# Sheet1.net
KiCad netlist of a schematic drawn in Altium Designer
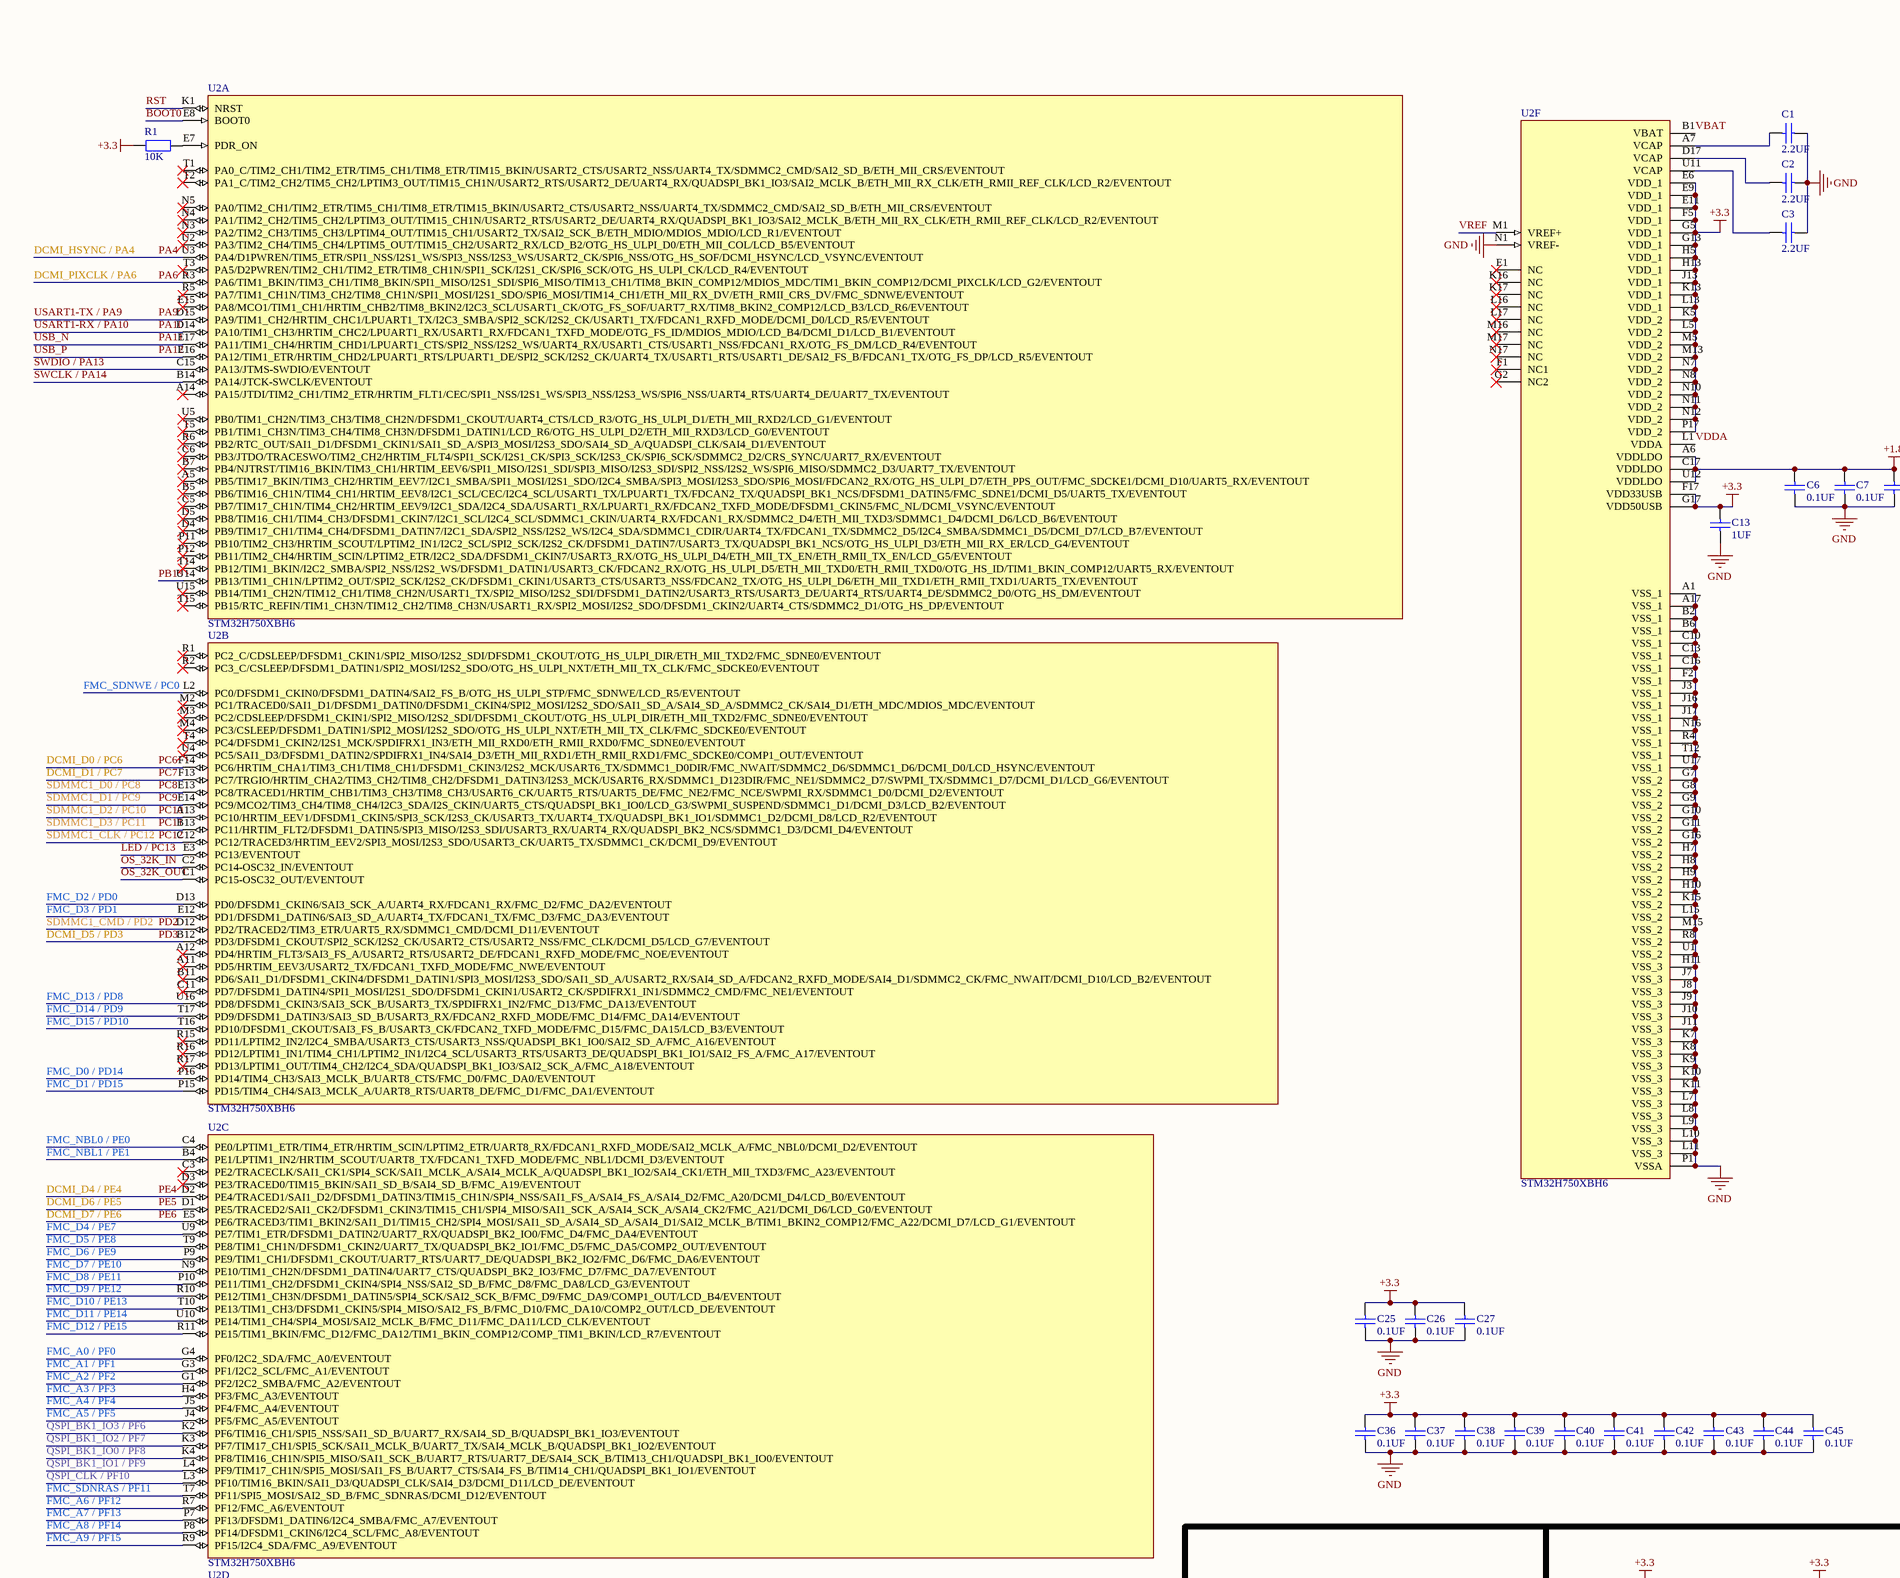
[diagram p0: Sheet1.SchDoc, top left]
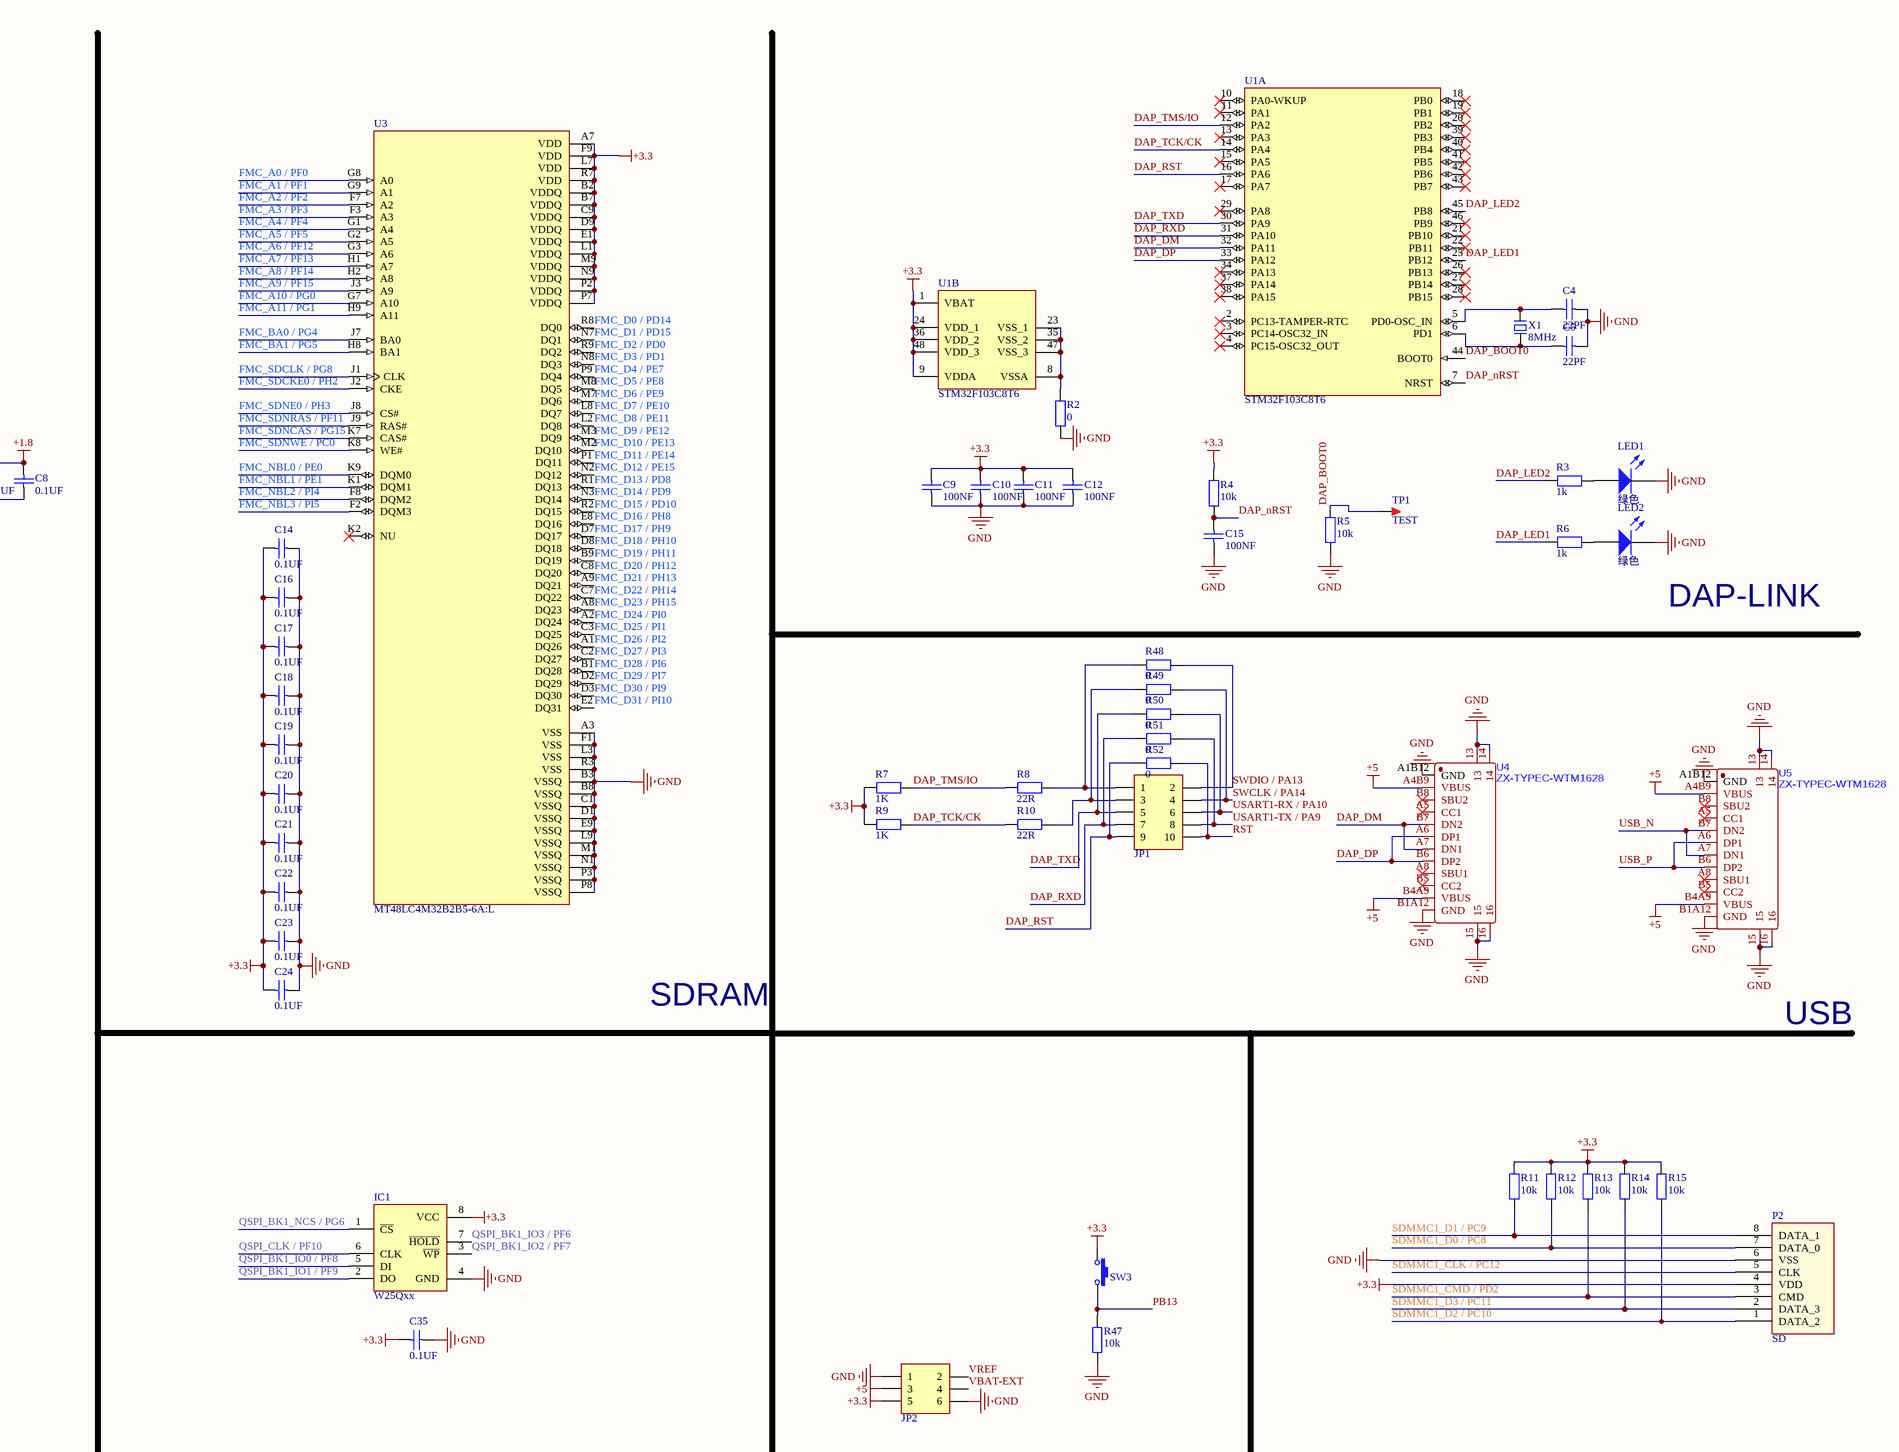
[diagram p1: Sheet1.SchDoc, top right]
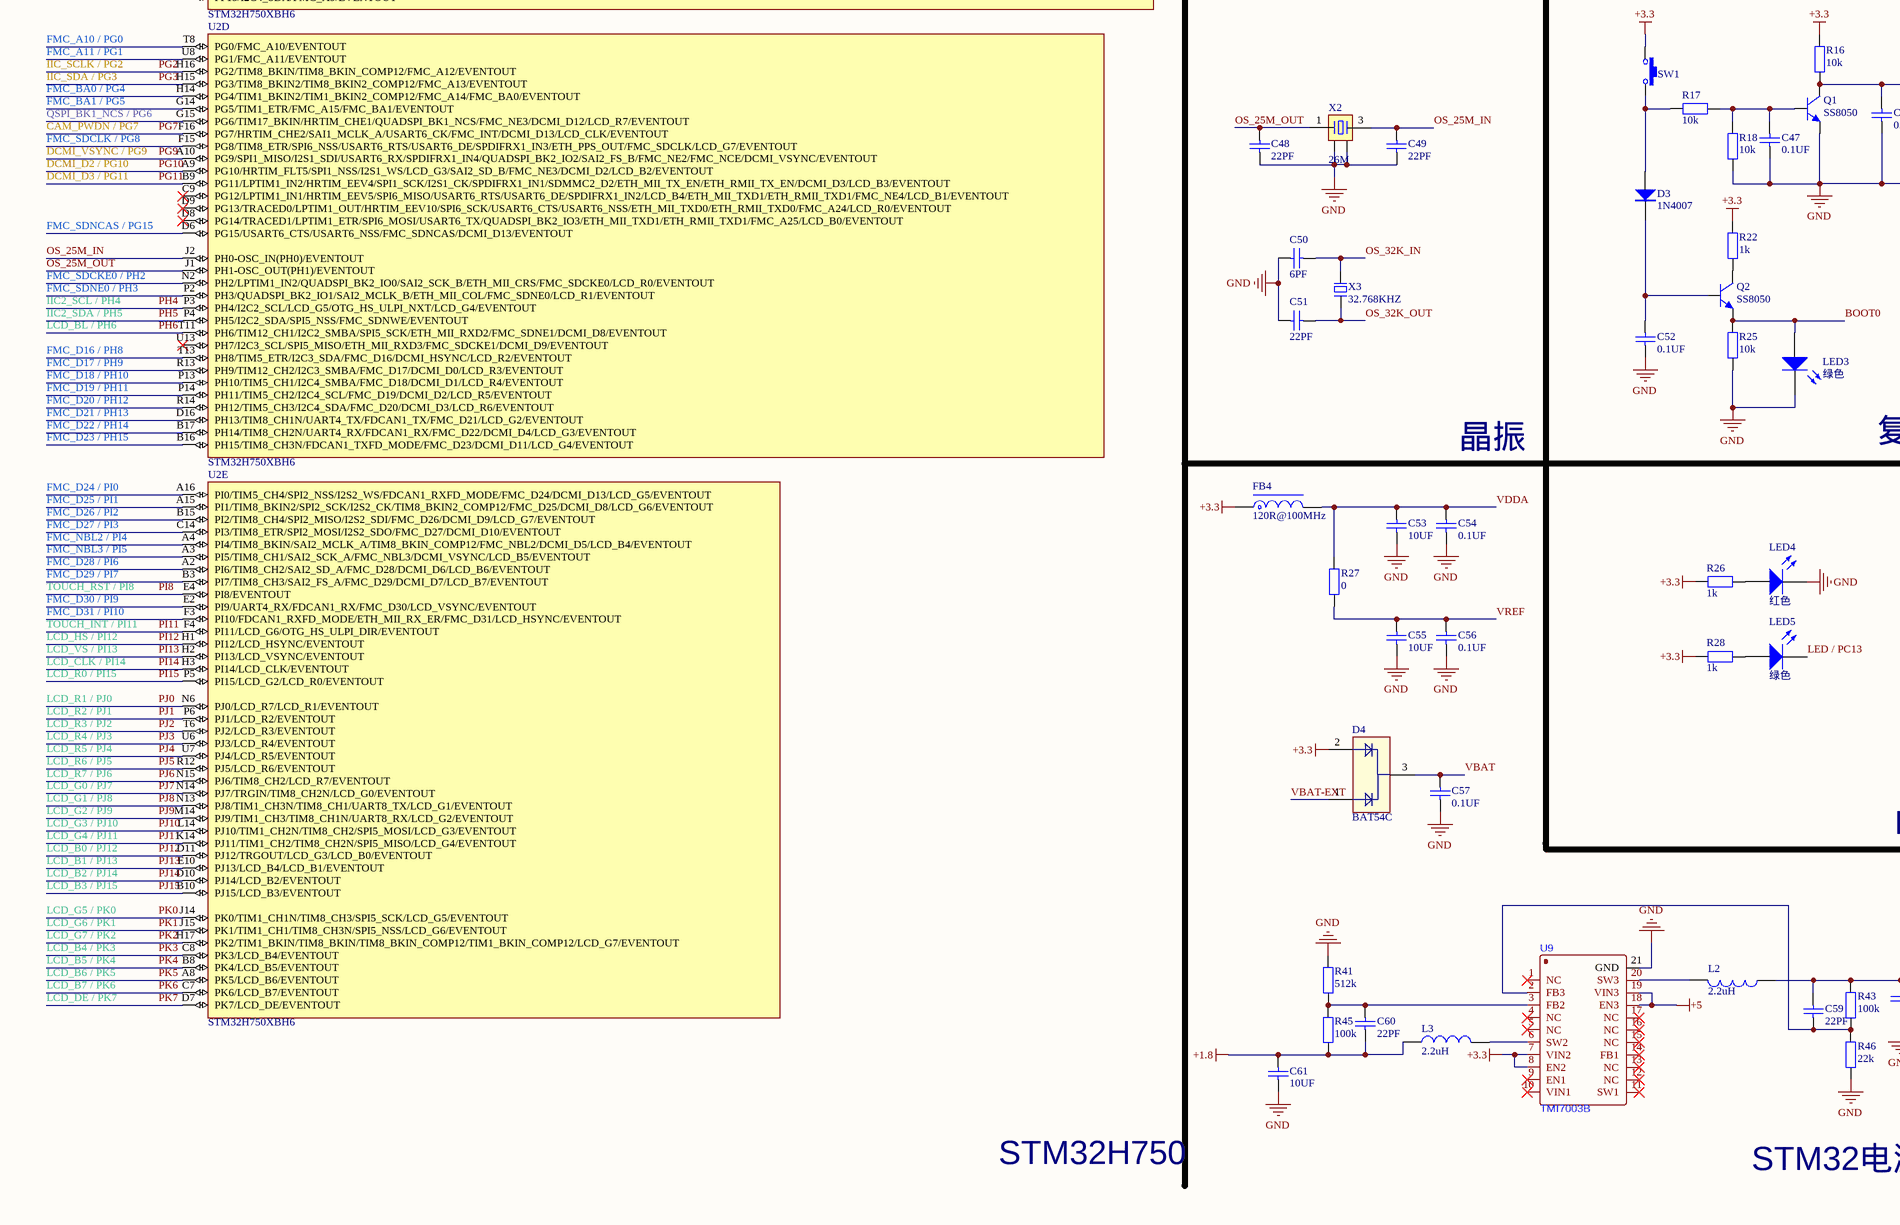
[diagram p2: Sheet1.SchDoc, bottom left]
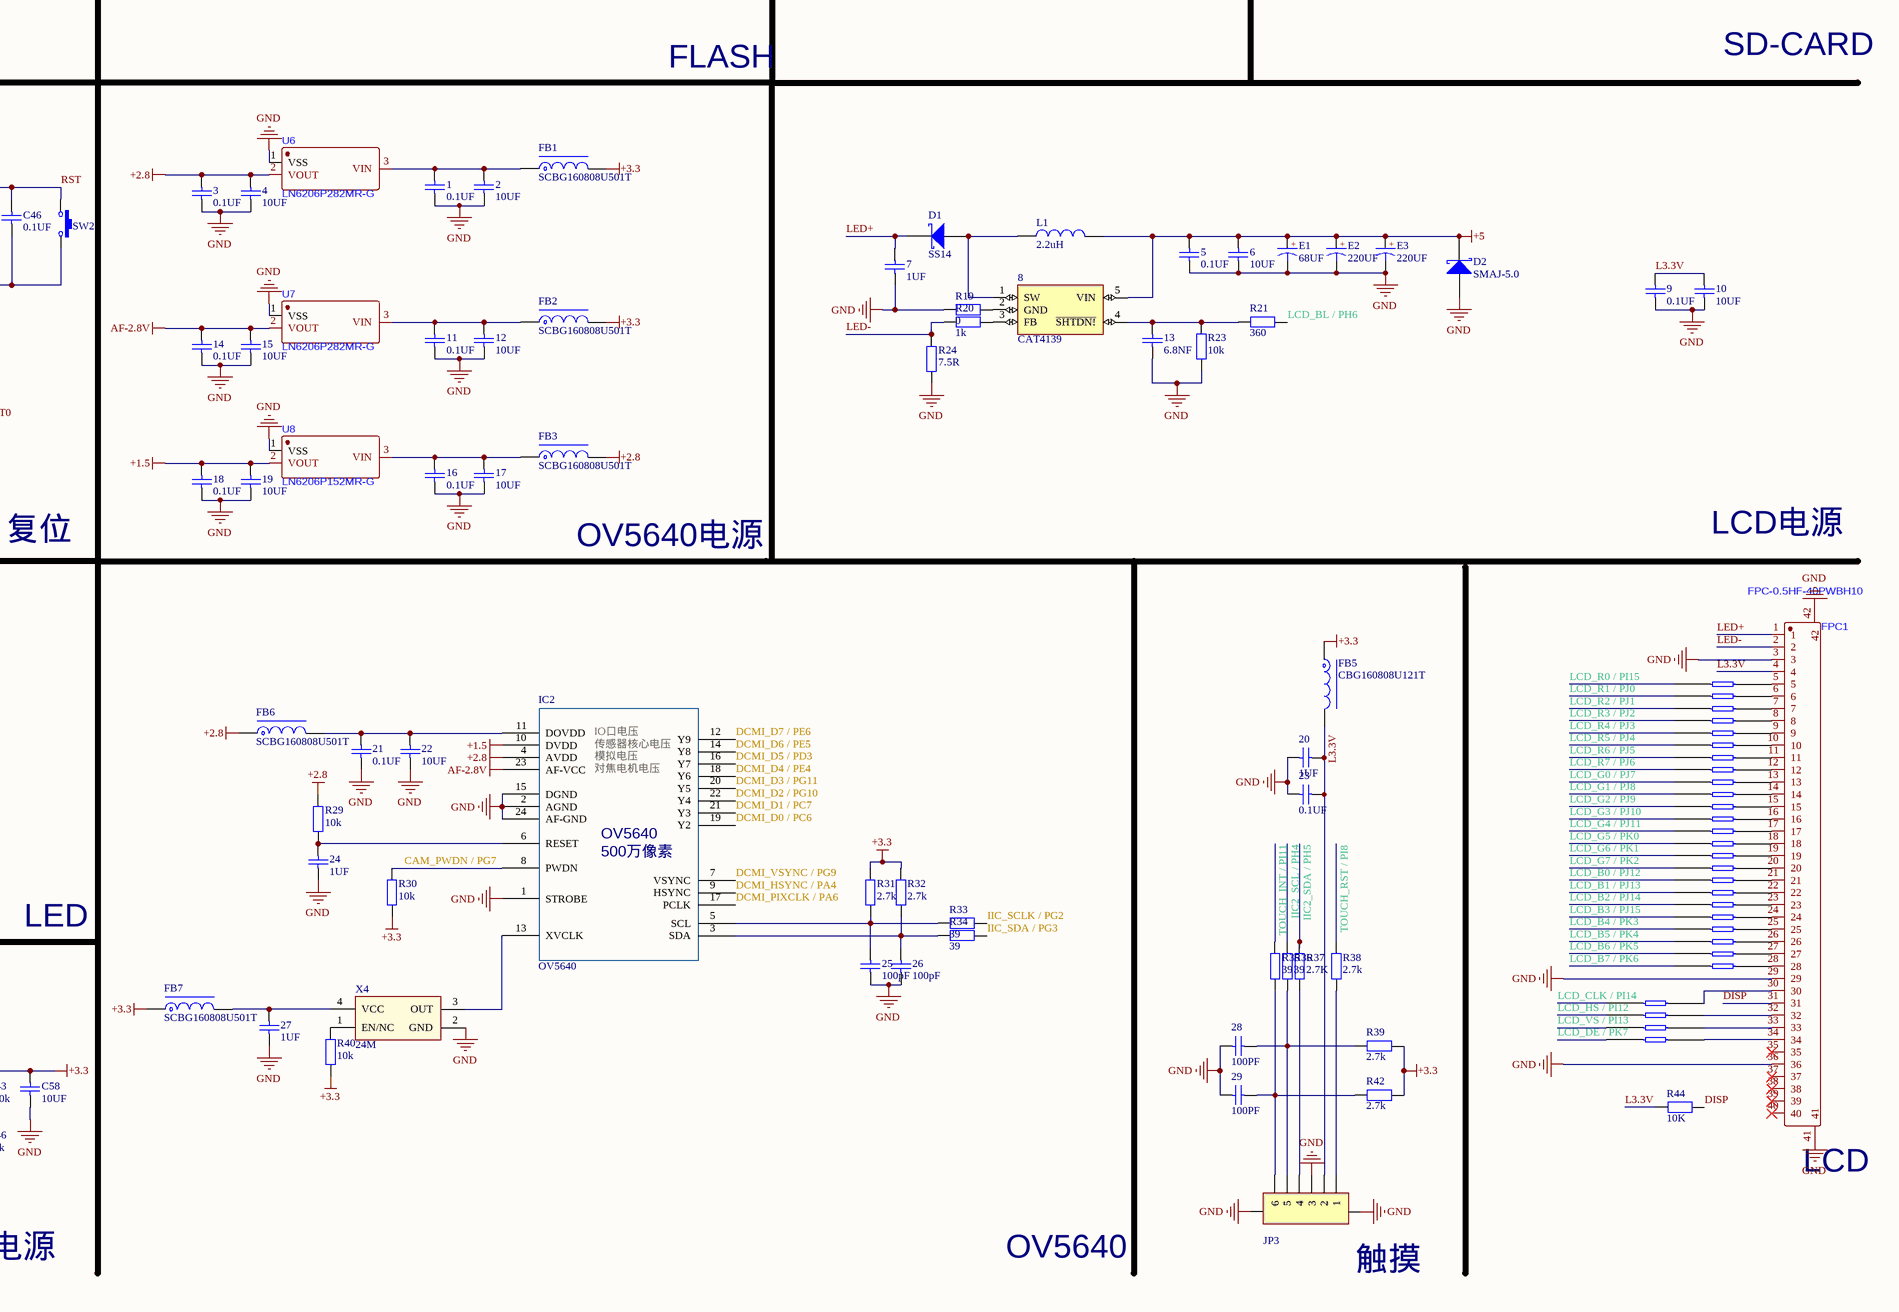
[diagram p3: Sheet1.SchDoc, bottom right]

(export (version "E")
  (design (tool "Eeschema 10.0.6"))
  (components
    (comp (ref "1")
      (value "0.1UF")
      (footprint "PCB1:C0603_L")
      (description "贴片电容/MLCC电容")
      (libsource (lib "屏幕一体板v1") (part "C"))
    )
    (comp (ref "2")
      (value "10UF")
      (footprint "PCB1:C0603_L")
      (description "贴片电容/MLCC电容")
      (libsource (lib "屏幕一体板v1") (part "C"))
    )
    (comp (ref "3")
      (value "0.1UF")
      (footprint "PCB1:C0603_L")
      (description "贴片电容/MLCC电容")
      (libsource (lib "屏幕一体板v1") (part "C"))
    )
    (comp (ref "4")
      (value "10UF")
      (footprint "PCB1:C0603_L")
      (description "贴片电容/MLCC电容")
      (libsource (lib "屏幕一体板v1") (part "C"))
    )
    (comp (ref "5")
      (value "0.1UF")
      (footprint "PCB1:C0603_L")
      (description "贴片电容/MLCC电容")
      (libsource (lib "屏幕一体板v1") (part "C"))
    )
    (comp (ref "6")
      (value "10UF")
      (footprint "PCB1:C0603_L")
      (description "贴片电容/MLCC电容")
      (libsource (lib "屏幕一体板v1") (part "C"))
    )
    (comp (ref "7")
      (value "1UF")
      (footprint "PCB1:C0603_L")
      (description "贴片电容/MLCC电容")
      (libsource (lib "屏幕一体板v1") (part "C"))
    )
    (comp (ref "8")
      (value "CAT4139")
      (footprint "PCB1:SOT-23(OT)5_LEAD")
      (libsource (lib "屏幕一体板v1") (part "CAT4139"))
    )
    (comp (ref "9")
      (value "0.1UF")
      (footprint "PCB1:C0603_L")
      (description "贴片电容/MLCC电容")
      (libsource (lib "屏幕一体板v1") (part "C"))
    )
    (comp (ref "10")
      (value "10UF")
      (footprint "PCB1:C0603_L")
      (description "贴片电容/MLCC电容")
      (libsource (lib "屏幕一体板v1") (part "C"))
    )
    (comp (ref "11")
      (value "0.1UF")
      (footprint "PCB1:C0603_L")
      (description "贴片电容/MLCC电容")
      (libsource (lib "屏幕一体板v1") (part "C"))
    )
    (comp (ref "12")
      (value "10UF")
      (footprint "PCB1:C0603_L")
      (description "贴片电容/MLCC电容")
      (libsource (lib "屏幕一体板v1") (part "C"))
    )
    (comp (ref "13")
      (value "6.8NF")
      (footprint "PCB1:C0603_L")
      (description "贴片电容/MLCC电容")
      (libsource (lib "屏幕一体板v1") (part "C"))
    )
    (comp (ref "14")
      (value "0.1UF")
      (footprint "PCB1:C0603_L")
      (description "贴片电容/MLCC电容")
      (libsource (lib "屏幕一体板v1") (part "C"))
    )
    (comp (ref "15")
      (value "10UF")
      (footprint "PCB1:C0603_L")
      (description "贴片电容/MLCC电容")
      (libsource (lib "屏幕一体板v1") (part "C"))
    )
    (comp (ref "16")
      (value "0.1UF")
      (footprint "PCB1:C0603_L")
      (description "贴片电容/MLCC电容")
      (libsource (lib "屏幕一体板v1") (part "C"))
    )
    (comp (ref "17")
      (value "10UF")
      (footprint "PCB1:C0603_L")
      (description "贴片电容/MLCC电容")
      (libsource (lib "屏幕一体板v1") (part "C"))
    )
    (comp (ref "18")
      (value "0.1UF")
      (footprint "PCB1:C0603_L")
      (description "贴片电容/MLCC电容")
      (libsource (lib "屏幕一体板v1") (part "C"))
    )
    (comp (ref "19")
      (value "10UF")
      (footprint "PCB1:C0603_L")
      (description "贴片电容/MLCC电容")
      (libsource (lib "屏幕一体板v1") (part "C"))
    )
    (comp (ref "20")
      (value "1UF")
      (footprint "PCB1:C0603_L")
      (description "贴片电容/MLCC电容")
      (libsource (lib "屏幕一体板v1") (part "C"))
    )
    (comp (ref "21")
      (value "0.1UF")
      (footprint "PCB1:C0603_L")
      (description "贴片电容/MLCC电容")
      (libsource (lib "屏幕一体板v1") (part "C"))
    )
    (comp (ref "22")
      (value "10UF")
      (footprint "PCB1:C0603_L")
      (description "贴片电容/MLCC电容")
      (libsource (lib "屏幕一体板v1") (part "C"))
    )
    (comp (ref "23")
      (value "0.1UF")
      (footprint "PCB1:C0603_L")
      (description "贴片电容/MLCC电容")
      (libsource (lib "屏幕一体板v1") (part "C"))
    )
    (comp (ref "24")
      (value "1UF")
      (footprint "PCB1:C0603_L")
      (description "贴片电容/MLCC电容")
      (libsource (lib "屏幕一体板v1") (part "C"))
    )
    (comp (ref "25")
      (value "100pF")
      (footprint "PCB1:C0603_L")
      (description "贴片电容/MLCC电容")
      (libsource (lib "屏幕一体板v1") (part "C"))
    )
    (comp (ref "26")
      (value "100pF")
      (footprint "PCB1:C0603_L")
      (description "贴片电容/MLCC电容")
      (libsource (lib "屏幕一体板v1") (part "C"))
    )
    (comp (ref "27")
      (value "1UF")
      (footprint "PCB1:C0603_L")
      (description "贴片电容/MLCC电容")
      (libsource (lib "屏幕一体板v1") (part "C"))
    )
    (comp (ref "28")
      (value "100PF")
      (footprint "PCB1:C0603_L")
      (description "贴片电容/MLCC电容")
      (libsource (lib "屏幕一体板v1") (part "C"))
    )
    (comp (ref "29")
      (value "100PF")
      (footprint "PCB1:C0603_L")
      (description "贴片电容/MLCC电容")
      (libsource (lib "屏幕一体板v1") (part "C"))
    )
    (comp (ref "C1")
      (value "2.2UF")
      (footprint "PCB1:C0603_L")
      (description "贴片电容/MLCC电容")
      (libsource (lib "屏幕一体板v1") (part "C"))
    )
    (comp (ref "C2")
      (value "2.2UF")
      (footprint "PCB1:C0603_L")
      (description "贴片电容/MLCC电容")
      (libsource (lib "屏幕一体板v1") (part "C"))
    )
    (comp (ref "C3")
      (value "2.2UF")
      (footprint "PCB1:C0603_L")
      (description "贴片电容/MLCC电容")
      (libsource (lib "屏幕一体板v1") (part "C"))
    )
    (comp (ref "C4")
      (value "22PF")
      (footprint "PCB1:C0603_L")
      (description "贴片电容/MLCC电容")
      (libsource (lib "屏幕一体板v1") (part "C"))
    )
    (comp (ref "C5")
      (value "22PF")
      (footprint "PCB1:C0603_L")
      (description "贴片电容/MLCC电容")
      (libsource (lib "屏幕一体板v1") (part "C"))
    )
    (comp (ref "C6")
      (value "0.1UF")
      (footprint "PCB1:C0603_L")
      (description "贴片电容/MLCC电容")
      (libsource (lib "屏幕一体板v1") (part "C"))
    )
    (comp (ref "C7")
      (value "0.1UF")
      (footprint "PCB1:C0603_L")
      (description "贴片电容/MLCC电容")
      (libsource (lib "屏幕一体板v1") (part "C"))
    )
    (comp (ref "C8")
      (value "0.1UF")
      (footprint "PCB1:C0603_L")
      (description "贴片电容/MLCC电容")
      (libsource (lib "屏幕一体板v1") (part "C"))
    )
    (comp (ref "C9")
      (value "100NF")
      (footprint "PCB1:C0603_L")
      (description "贴片电容/MLCC电容")
      (libsource (lib "屏幕一体板v1") (part "C"))
    )
    (comp (ref "C10")
      (value "100NF")
      (footprint "PCB1:C0603_L")
      (description "贴片电容/MLCC电容")
      (libsource (lib "屏幕一体板v1") (part "C"))
    )
    (comp (ref "C11")
      (value "100NF")
      (footprint "PCB1:C0603_L")
      (description "贴片电容/MLCC电容")
      (libsource (lib "屏幕一体板v1") (part "C"))
    )
    (comp (ref "C12")
      (value "100NF")
      (footprint "PCB1:C0603_L")
      (description "贴片电容/MLCC电容")
      (libsource (lib "屏幕一体板v1") (part "C"))
    )
    (comp (ref "C13")
      (value "1UF")
      (footprint "PCB1:C0603_L")
      (description "贴片电容/MLCC电容")
      (libsource (lib "屏幕一体板v1") (part "C"))
    )
    (comp (ref "C14")
      (value "0.1UF")
      (footprint "PCB1:C0201_M")
      (description "贴片电容/MLCC电容")
      (libsource (lib "屏幕一体板v1") (part "C"))
    )
    (comp (ref "C15")
      (value "100NF")
      (footprint "PCB1:C0603_L")
      (description "贴片电容/MLCC电容")
      (libsource (lib "屏幕一体板v1") (part "C"))
    )
    (comp (ref "C16")
      (value "0.1UF")
      (footprint "PCB1:C0201_M")
      (description "贴片电容/MLCC电容")
      (libsource (lib "屏幕一体板v1") (part "C"))
    )
    (comp (ref "C17")
      (value "0.1UF")
      (footprint "PCB1:C0201_M")
      (description "贴片电容/MLCC电容")
      (libsource (lib "屏幕一体板v1") (part "C"))
    )
    (comp (ref "C18")
      (value "0.1UF")
      (footprint "PCB1:C0201_M")
      (description "贴片电容/MLCC电容")
      (libsource (lib "屏幕一体板v1") (part "C"))
    )
    (comp (ref "C19")
      (value "0.1UF")
      (footprint "PCB1:C0201_M")
      (description "贴片电容/MLCC电容")
      (libsource (lib "屏幕一体板v1") (part "C"))
    )
    (comp (ref "C20")
      (value "0.1UF")
      (footprint "PCB1:C0201_M")
      (description "贴片电容/MLCC电容")
      (libsource (lib "屏幕一体板v1") (part "C"))
    )
    (comp (ref "C21")
      (value "0.1UF")
      (footprint "PCB1:C0201_M")
      (description "贴片电容/MLCC电容")
      (libsource (lib "屏幕一体板v1") (part "C"))
    )
    (comp (ref "C22")
      (value "0.1UF")
      (footprint "PCB1:C0201_M")
      (description "贴片电容/MLCC电容")
      (libsource (lib "屏幕一体板v1") (part "C"))
    )
    (comp (ref "C23")
      (value "0.1UF")
      (footprint "PCB1:C0201_M")
      (description "贴片电容/MLCC电容")
      (libsource (lib "屏幕一体板v1") (part "C"))
    )
    (comp (ref "C24")
      (value "0.1UF")
      (footprint "PCB1:C0201_M")
      (description "贴片电容/MLCC电容")
      (libsource (lib "屏幕一体板v1") (part "C"))
    )
    (comp (ref "C25")
      (value "0.1UF")
      (footprint "PCB1:C0201_M")
      (description "贴片电容/MLCC电容")
      (libsource (lib "屏幕一体板v1") (part "C"))
    )
    (comp (ref "C26")
      (value "0.1UF")
      (footprint "PCB1:C0201_M")
      (description "贴片电容/MLCC电容")
      (libsource (lib "屏幕一体板v1") (part "C"))
    )
    (comp (ref "C27")
      (value "0.1UF")
      (footprint "PCB1:C0201_M")
      (description "贴片电容/MLCC电容")
      (libsource (lib "屏幕一体板v1") (part "C"))
    )
    (comp (ref "C35")
      (value "0.1UF")
      (footprint "PCB1:C0603_L")
      (description "贴片电容/MLCC电容")
      (libsource (lib "屏幕一体板v1") (part "C"))
    )
    (comp (ref "C36")
      (value "0.1UF")
      (footprint "PCB1:C0201_M")
      (description "贴片电容/MLCC电容")
      (libsource (lib "屏幕一体板v1") (part "C"))
    )
    (comp (ref "C37")
      (value "0.1UF")
      (footprint "PCB1:C0201_M")
      (description "贴片电容/MLCC电容")
      (libsource (lib "屏幕一体板v1") (part "C"))
    )
    (comp (ref "C38")
      (value "0.1UF")
      (footprint "PCB1:C0201_M")
      (description "贴片电容/MLCC电容")
      (libsource (lib "屏幕一体板v1") (part "C"))
    )
    (comp (ref "C39")
      (value "0.1UF")
      (footprint "PCB1:C0201_M")
      (description "贴片电容/MLCC电容")
      (libsource (lib "屏幕一体板v1") (part "C"))
    )
    (comp (ref "C40")
      (value "0.1UF")
      (footprint "PCB1:C0201_M")
      (description "贴片电容/MLCC电容")
      (libsource (lib "屏幕一体板v1") (part "C"))
    )
    (comp (ref "C41")
      (value "0.1UF")
      (footprint "PCB1:C0201_M")
      (description "贴片电容/MLCC电容")
      (libsource (lib "屏幕一体板v1") (part "C"))
    )
    (comp (ref "C42")
      (value "0.1UF")
      (footprint "PCB1:C0201_M")
      (description "贴片电容/MLCC电容")
      (libsource (lib "屏幕一体板v1") (part "C"))
    )
    (comp (ref "C43")
      (value "0.1UF")
      (footprint "PCB1:C0201_M")
      (description "贴片电容/MLCC电容")
      (libsource (lib "屏幕一体板v1") (part "C"))
    )
    (comp (ref "C44")
      (value "0.1UF")
      (footprint "PCB1:C0201_M")
      (description "贴片电容/MLCC电容")
      (libsource (lib "屏幕一体板v1") (part "C"))
    )
    (comp (ref "C45")
      (value "0.1UF")
      (footprint "PCB1:C0201_M")
      (description "贴片电容/MLCC电容")
      (libsource (lib "屏幕一体板v1") (part "C"))
    )
    (comp (ref "C46")
      (value "0.1UF")
      (footprint "PCB1:C0603_L")
      (description "贴片电容/MLCC电容")
      (libsource (lib "屏幕一体板v1") (part "C"))
    )
    (comp (ref "C47")
      (value "0.1UF")
      (footprint "PCB1:C0603_L")
      (description "贴片电容/MLCC电容")
      (libsource (lib "屏幕一体板v1") (part "C"))
    )
    (comp (ref "C48")
      (value "22PF")
      (footprint "PCB1:C0603_L")
      (description "贴片电容/MLCC电容")
      (libsource (lib "屏幕一体板v1") (part "C"))
    )
    (comp (ref "C49")
      (value "22PF")
      (footprint "PCB1:C0603_L")
      (description "贴片电容/MLCC电容")
      (libsource (lib "屏幕一体板v1") (part "C"))
    )
    (comp (ref "C50")
      (value "6PF")
      (footprint "PCB1:C0603_L")
      (description "贴片电容/MLCC电容")
      (libsource (lib "屏幕一体板v1") (part "C"))
    )
    (comp (ref "C51")
      (value "22PF")
      (footprint "PCB1:C0603_L")
      (description "贴片电容/MLCC电容")
      (libsource (lib "屏幕一体板v1") (part "C"))
    )
    (comp (ref "C52")
      (value "0.1UF")
      (footprint "PCB1:C0603_L")
      (description "贴片电容/MLCC电容")
      (libsource (lib "屏幕一体板v1") (part "C"))
    )
    (comp (ref "C53")
      (value "10UF")
      (footprint "PCB1:C0603_L")
      (description "贴片电容/MLCC电容")
      (libsource (lib "屏幕一体板v1") (part "C"))
    )
    (comp (ref "C54")
      (value "0.1UF")
      (footprint "PCB1:C0603_L")
      (description "贴片电容/MLCC电容")
      (libsource (lib "屏幕一体板v1") (part "C"))
    )
    (comp (ref "C55")
      (value "10UF")
      (footprint "PCB1:C0603_L")
      (description "贴片电容/MLCC电容")
      (libsource (lib "屏幕一体板v1") (part "C"))
    )
    (comp (ref "C56")
      (value "0.1UF")
      (footprint "PCB1:C0603_L")
      (description "贴片电容/MLCC电容")
      (libsource (lib "屏幕一体板v1") (part "C"))
    )
    (comp (ref "C57")
      (value "0.1UF")
      (footprint "PCB1:C0603_L")
      (description "贴片电容/MLCC电容")
      (libsource (lib "屏幕一体板v1") (part "C"))
    )
    (comp (ref "C58")
      (value "10UF")
      (footprint "PCB1:C0603_L")
      (description "贴片电容/MLCC电容")
      (libsource (lib "屏幕一体板v1") (part "C"))
    )
    (comp (ref "C59")
      (value "22PF")
      (footprint "PCB1:C0603_L")
      (description "贴片电容/MLCC电容")
      (libsource (lib "屏幕一体板v1") (part "C"))
    )
    (comp (ref "C60")
      (value "22PF")
      (footprint "PCB1:C0603_L")
      (description "贴片电容/MLCC电容")
      (libsource (lib "屏幕一体板v1") (part "C"))
    )
    (comp (ref "C61")
      (value "10UF")
      (footprint "PCB1:C0603_L")
      (description "贴片电容/MLCC电容")
      (libsource (lib "屏幕一体板v1") (part "C"))
    )
    (comp (ref "D1")
      (value "SS14")
      (footprint "PCB1:SMA")
      (description "肖特基二极管")
      (libsource (lib "屏幕一体板v1") (part "SS14"))
    )
    (comp (ref "D2")
      (value "SMAJ-5.0")
      (footprint "PCB1:SMB")
      (description "肖特基二极管")
      (libsource (lib "屏幕一体板v1") (part "SS24"))
    )
    (comp (ref "D3")
      (value "1N4007")
      (footprint "PCB1:SMA")
      (description "整流二极管")
      (libsource (lib "屏幕一体板v1") (part "1N4007"))
    )
    (comp (ref "D4")
      (value "BAT54C")
      (footprint "PCB1:SOT23-3N")
      (description "两路肖特基二极管")
      (libsource (lib "屏幕一体板v1") (part "BAT54C"))
    )
    (comp (ref "E1")
      (value "68UF")
      (footprint "PCB1:CE A(3*5.4)")
      (description "贴片电解电容")
      (libsource (lib "屏幕一体板v1") (part "CE_SMD"))
    )
    (comp (ref "E2")
      (value "220UF")
      (footprint "PCB1:CE A(3*5.4)")
      (description "贴片电解电容")
      (libsource (lib "屏幕一体板v1") (part "CE_SMD"))
    )
    (comp (ref "E3")
      (value "220UF")
      (footprint "PCB1:CE A(3*5.4)")
      (description "贴片电解电容")
      (libsource (lib "屏幕一体板v1") (part "CE_SMD"))
    )
    (comp (ref "FB1")
      (value "SCBG160808U501T")
      (footprint "PCB1:FB0201")
      (description "贴片磁珠")
      (libsource (lib "屏幕一体板v1") (part "FB"))
    )
    (comp (ref "FB2")
      (value "SCBG160808U501T")
      (footprint "PCB1:FB0201")
      (description "贴片磁珠")
      (libsource (lib "屏幕一体板v1") (part "FB"))
    )
    (comp (ref "FB3")
      (value "SCBG160808U501T")
      (footprint "PCB1:FB0201")
      (description "贴片磁珠")
      (libsource (lib "屏幕一体板v1") (part "FB"))
    )
    (comp (ref "FB4")
      (value "120R@100MHz")
      (footprint "PCB1:FB0201")
      (description "贴片磁珠")
      (libsource (lib "屏幕一体板v1") (part "FB"))
    )
    (comp (ref "FB5")
      (value "CBG160808U121T")
      (footprint "PCB1:FB0805")
      (description "贴片磁珠")
      (libsource (lib "") (part "FB_1"))
    )
    (comp (ref "FB6")
      (value "SCBG160808U501T")
      (footprint "PCB1:FB0201")
      (description "贴片磁珠")
      (libsource (lib "屏幕一体板v1") (part "FB"))
    )
    (comp (ref "FB7")
      (value "SCBG160808U501T")
      (footprint "PCB1:FB0201")
      (description "贴片磁珠")
      (libsource (lib "屏幕一体板v1") (part "FB"))
    )
    (comp (ref "FPC1")
      (value "FPC-0.5HF-40PWBH10")
      (footprint "PCB1:FPC-SMD_40P-P0.50_FPC-0.5HF-40PWBH10")
      (libsource (lib "屏幕一体板v1") (part "FPC-0.5HF-40PWBH10"))
    )
    (comp (ref "IC1")
      (value "W25Qxx")
      (footprint "PCB1:SOP8W_N")
      (description "SPI Flash")
      (libsource (lib "屏幕一体板v1") (part "W25Q"))
    )
    (comp (ref "IC2") (value "OV5640") (footprint "PCB1:OV2640") (libsource (lib "屏幕一体板v1") (part "OV5640")))
    (comp (ref "JP1")
      (value "Header 5X2")
      (footprint "PCB1:HDR2.54-M-LS-2x5P")
      (description "5*2P接插件")
      (libsource (lib "屏幕一体板v1") (part "Header 5X2"))
    )
    (comp (ref "JP2")
      (value "Header3X2")
      (footprint "PCB1:HDR2.54-M-LS-2x3P")
      (description "3*2P接插件")
      (libsource (lib "屏幕一体板v1") (part "Header 3X2"))
    )
    (comp (ref "JP3")
      (value "CON-6P")
      (footprint "PCB1:FPC0.5-WT-6P")
      (description "6P连接器")
      (libsource (lib "屏幕一体板v1") (part "Header 6"))
    )
    (comp (ref "L1")
      (value "2.2uH")
      (footprint "PCB1:L0805")
      (description "贴片小功率电感")
      (libsource (lib "屏幕一体板v1") (part "L"))
    )
    (comp (ref "L2")
      (value "2.2uH")
      (footprint "PCB1:L0805")
      (description "贴片小功率电感")
      (libsource (lib "屏幕一体板v1") (part "L"))
    )
    (comp (ref "L3")
      (value "2.2uH")
      (footprint "PCB1:L0805")
      (description "贴片小功率电感")
      (libsource (lib "屏幕一体板v1") (part "L"))
    )
    (comp (ref "LED1")
      (value "绿色")
      (footprint "PCB1:LED0805_G")
      (description "贴片LED")
      (libsource (lib "屏幕一体板v1") (part "LED"))
    )
    (comp (ref "LED2")
      (value "绿色")
      (footprint "PCB1:LED0805_G")
      (description "贴片LED")
      (libsource (lib "屏幕一体板v1") (part "LED"))
    )
    (comp (ref "LED3")
      (value "绿色")
      (footprint "PCB1:LED0805_G")
      (description "贴片LED")
      (libsource (lib "屏幕一体板v1") (part "LED"))
    )
    (comp (ref "LED4")
      (value "红色")
      (footprint "PCB1:LED0603_R")
      (description "贴片LED")
      (libsource (lib "屏幕一体板v1") (part "LED"))
    )
    (comp (ref "LED5")
      (value "绿色")
      (footprint "PCB1:LED0805_G")
      (description "贴片LED")
      (libsource (lib "屏幕一体板v1") (part "LED"))
    )
    (comp (ref "P2")
      (value "SD")
      (footprint "PCB1:MICRO SD")
      (description "自弹式TF卡座")
      (libsource (lib "屏幕一体板v1") (part "Micro SD_SD"))
    )
    (comp (ref "Q1")
      (value "SS8050")
      (footprint "PCB1:SOT23-3N")
      (description "高频放大-NPN型")
      (libsource (lib "屏幕一体板v1") (part "8050-SMD"))
    )
    (comp (ref "Q2")
      (value "SS8050")
      (footprint "PCB1:SOT23-3N")
      (description "高频放大-NPN型")
      (libsource (lib "屏幕一体板v1") (part "8050-SMD"))
    )
    (comp (ref "R1")
      (value "10K")
      (footprint "PCB1:R0603_L")
      (description "贴片电阻")
      (libsource (lib "屏幕一体板v1") (part "R"))
    )
    (comp (ref "R2")
      (value "0")
      (footprint "PCB1:R0603_L")
      (description "贴片电阻")
      (libsource (lib "屏幕一体板v1") (part "R"))
    )
    (comp (ref "R3")
      (value "1k")
      (footprint "PCB1:R0603_L")
      (description "贴片电阻")
      (libsource (lib "屏幕一体板v1") (part "R"))
    )
    (comp (ref "R4")
      (value "10k")
      (footprint "PCB1:R0603_L")
      (description "贴片电阻")
      (libsource (lib "屏幕一体板v1") (part "R"))
    )
    (comp (ref "R5")
      (value "10k")
      (footprint "PCB1:R0603_L")
      (description "贴片电阻")
      (libsource (lib "屏幕一体板v1") (part "R"))
    )
    (comp (ref "R6")
      (value "1k")
      (footprint "PCB1:R0603_L")
      (description "贴片电阻")
      (libsource (lib "屏幕一体板v1") (part "R"))
    )
    (comp (ref "R7")
      (value "1K")
      (footprint "PCB1:R0805_L")
      (description "贴片电阻")
      (libsource (lib "屏幕一体板v1") (part "R"))
    )
    (comp (ref "R8")
      (value "22R")
      (footprint "PCB1:R0805_L")
      (description "贴片电阻")
      (libsource (lib "屏幕一体板v1") (part "R"))
    )
    (comp (ref "R9")
      (value "1K")
      (footprint "PCB1:R0805_L")
      (description "贴片电阻")
      (libsource (lib "屏幕一体板v1") (part "R"))
    )
    (comp (ref "R10")
      (value "22R")
      (footprint "PCB1:R0805_L")
      (description "贴片电阻")
      (libsource (lib "屏幕一体板v1") (part "R"))
    )
    (comp (ref "R11")
      (value "10k")
      (footprint "PCB1:R0603_L")
      (description "贴片电阻")
      (libsource (lib "屏幕一体板v1") (part "R"))
    )
    (comp (ref "R12")
      (value "10k")
      (footprint "PCB1:R0603_L")
      (description "贴片电阻")
      (libsource (lib "屏幕一体板v1") (part "R"))
    )
    (comp (ref "R13")
      (value "10k")
      (footprint "PCB1:R0603_L")
      (description "贴片电阻")
      (libsource (lib "屏幕一体板v1") (part "R"))
    )
    (comp (ref "R14")
      (value "10k")
      (footprint "PCB1:R0603_L")
      (description "贴片电阻")
      (libsource (lib "屏幕一体板v1") (part "R"))
    )
    (comp (ref "R15")
      (value "10k")
      (footprint "PCB1:R0603_L")
      (description "贴片电阻")
      (libsource (lib "屏幕一体板v1") (part "R"))
    )
    (comp (ref "R16")
      (value "10k")
      (footprint "PCB1:R0603_L")
      (description "贴片电阻")
      (libsource (lib "屏幕一体板v1") (part "R"))
    )
    (comp (ref "R17")
      (value "10k")
      (footprint "PCB1:R0603_L")
      (description "贴片电阻")
      (libsource (lib "屏幕一体板v1") (part "R"))
    )
    (comp (ref "R18")
      (value "10k")
      (footprint "PCB1:R0603_L")
      (description "贴片电阻")
      (libsource (lib "屏幕一体板v1") (part "R"))
    )
    (comp (ref "R19")
      (value "0")
      (footprint "PCB1:R0603_L")
      (description "贴片电阻")
      (libsource (lib "屏幕一体板v1") (part "R"))
    )
    (comp (ref "R20")
      (value "1k")
      (footprint "PCB1:R0603_L")
      (description "贴片电阻")
      (libsource (lib "屏幕一体板v1") (part "R"))
    )
    (comp (ref "R21")
      (value "360")
      (footprint "PCB1:R0603_L")
      (description "贴片电阻")
      (libsource (lib "屏幕一体板v1") (part "R"))
    )
    (comp (ref "R22")
      (value "1k")
      (footprint "PCB1:R0603_L")
      (description "贴片电阻")
      (libsource (lib "屏幕一体板v1") (part "R"))
    )
    (comp (ref "R23")
      (value "10k")
      (footprint "PCB1:R0603_L")
      (description "贴片电阻")
      (libsource (lib "屏幕一体板v1") (part "R"))
    )
    (comp (ref "R24")
      (value "7.5R")
      (footprint "PCB1:R0603_L")
      (description "贴片电阻")
      (libsource (lib "屏幕一体板v1") (part "R"))
    )
    (comp (ref "R25")
      (value "10k")
      (footprint "PCB1:R0603_L")
      (description "贴片电阻")
      (libsource (lib "屏幕一体板v1") (part "R"))
    )
    (comp (ref "R26")
      (value "1k")
      (footprint "PCB1:R0603_L")
      (description "贴片电阻")
      (libsource (lib "屏幕一体板v1") (part "R"))
    )
    (comp (ref "R27")
      (value "0")
      (footprint "PCB1:R0603_L")
      (description "贴片电阻")
      (libsource (lib "屏幕一体板v1") (part "R"))
    )
    (comp (ref "R28")
      (value "1k")
      (footprint "PCB1:R0603_L")
      (description "贴片电阻")
      (libsource (lib "屏幕一体板v1") (part "R"))
    )
    (comp (ref "R29")
      (value "10k")
      (footprint "PCB1:R0603_L")
      (description "贴片电阻")
      (libsource (lib "屏幕一体板v1") (part "R"))
    )
    (comp (ref "R30")
      (value "10k")
      (footprint "PCB1:R0603_L")
      (description "贴片电阻")
      (libsource (lib "屏幕一体板v1") (part "R"))
    )
    (comp (ref "R31")
      (value "2.7k")
      (footprint "PCB1:R0603_L")
      (description "贴片电阻")
      (libsource (lib "屏幕一体板v1") (part "R"))
    )
    (comp (ref "R32")
      (value "2.7k")
      (footprint "PCB1:R0603_L")
      (description "贴片电阻")
      (libsource (lib "屏幕一体板v1") (part "R"))
    )
    (comp (ref "R33")
      (value "39")
      (footprint "PCB1:R0603_L")
      (description "贴片电阻")
      (libsource (lib "屏幕一体板v1") (part "R"))
    )
    (comp (ref "R34")
      (value "39")
      (footprint "PCB1:R0603_L")
      (description "贴片电阻")
      (libsource (lib "屏幕一体板v1") (part "R"))
    )
    (comp (ref "R35")
      (value "39")
      (footprint "PCB1:R0603_L")
      (description "贴片电阻")
      (libsource (lib "屏幕一体板v1") (part "R"))
    )
    (comp (ref "R36")
      (value "39")
      (footprint "PCB1:R0603_L")
      (description "贴片电阻")
      (libsource (lib "屏幕一体板v1") (part "R"))
    )
    (comp (ref "R37")
      (value "2.7K")
      (footprint "PCB1:R0603_L")
      (description "贴片电阻")
      (libsource (lib "屏幕一体板v1") (part "R"))
    )
    (comp (ref "R38")
      (value "2.7k")
      (footprint "PCB1:R0603_L")
      (description "贴片电阻")
      (libsource (lib "屏幕一体板v1") (part "R"))
    )
    (comp (ref "R39")
      (value "2.7k")
      (footprint "PCB1:R0603_L")
      (description "贴片电阻")
      (libsource (lib "屏幕一体板v1") (part "R"))
    )
    (comp (ref "R40")
      (value "10k")
      (footprint "PCB1:R0603_L")
      (description "贴片电阻")
      (libsource (lib "屏幕一体板v1") (part "R"))
    )
    (comp (ref "R41")
      (value "512k")
      (footprint "PCB1:R0603_L")
      (description "贴片电阻")
      (libsource (lib "屏幕一体板v1") (part "R"))
    )
    (comp (ref "R42")
      (value "2.7k")
      (footprint "PCB1:R0603_L")
      (description "贴片电阻")
      (libsource (lib "屏幕一体板v1") (part "R"))
    )
    (comp (ref "R43")
      (value "100k")
      (footprint "PCB1:R0603_L")
      (description "贴片电阻")
      (libsource (lib "屏幕一体板v1") (part "R"))
    )
    (comp (ref "R44")
      (value "10K")
      (footprint "PCB1:R0603_L")
      (description "贴片电阻")
      (libsource (lib "屏幕一体板v1") (part "R"))
    )
    (comp (ref "R45")
      (value "100k")
      (footprint "PCB1:R0603_L")
      (description "贴片电阻")
      (libsource (lib "屏幕一体板v1") (part "R"))
    )
    (comp (ref "R46")
      (value "22k")
      (footprint "PCB1:R0603_L")
      (description "贴片电阻")
      (libsource (lib "屏幕一体板v1") (part "R"))
    )
    (comp (ref "R47")
      (value "10k")
      (footprint "PCB1:R0603_L")
      (description "贴片电阻")
      (libsource (lib "屏幕一体板v1") (part "R"))
    )
    (comp (ref "R48")
      (value "0")
      (footprint "PCB1:R0603_L")
      (description "贴片电阻")
      (libsource (lib "屏幕一体板v1") (part "R"))
    )
    (comp (ref "R49")
      (value "0")
      (footprint "PCB1:R0603_L")
      (description "贴片电阻")
      (libsource (lib "屏幕一体板v1") (part "R"))
    )
    (comp (ref "R50")
      (value "0")
      (footprint "PCB1:R0603_L")
      (description "贴片电阻")
      (libsource (lib "屏幕一体板v1") (part "R"))
    )
    (comp (ref "R51")
      (value "0")
      (footprint "PCB1:R0603_L")
      (description "贴片电阻")
      (libsource (lib "屏幕一体板v1") (part "R"))
    )
    (comp (ref "R52")
      (value "0")
      (footprint "PCB1:R0603_L")
      (description "贴片电阻")
      (libsource (lib "屏幕一体板v1") (part "R"))
    )
    (comp (ref "RP1") (value "120R排阻") (footprint "PCB1:0603_4P") (libsource (lib "屏幕一体板v1") (part "RES_4P")))
    (comp (ref "RP2") (value "120R排阻") (footprint "PCB1:0603_4P") (libsource (lib "屏幕一体板v1") (part "RES_4P")))
    (comp (ref "RP3") (value "120R排阻") (footprint "PCB1:0603_4P") (libsource (lib "屏幕一体板v1") (part "RES_4P")))
    (comp (ref "RP4") (value "120R排阻") (footprint "PCB1:0603_4P") (libsource (lib "屏幕一体板v1") (part "RES_4P")))
    (comp (ref "RP5") (value "120R排阻") (footprint "PCB1:0603_4P") (libsource (lib "屏幕一体板v1") (part "RES_4P")))
    (comp (ref "RP6") (value "120R排阻") (footprint "PCB1:0603_4P") (libsource (lib "屏幕一体板v1") (part "RES_4P")))
    (comp (ref "RP7") (value "120R排阻") (footprint "PCB1:0603_4P") (libsource (lib "屏幕一体板v1") (part "RES_4P")))
    (comp (ref "SW1")
      (value "3x6x5")
      (footprint "PCB1:SW SMD-3*6*2.5")
      (description "3x6轻触开关")
      (libsource (lib "屏幕一体板v1") (part "SW 3x6"))
    )
    (comp (ref "SW2")
      (value "3x6x5")
      (footprint "PCB1:SW SMD-3*6*2.5")
      (description "3x6轻触开关")
      (libsource (lib "屏幕一体板v1") (part "SW 3x6"))
    )
    (comp (ref "SW3")
      (value "3x6x5")
      (footprint "PCB1:SW SMD-3*6*2.5")
      (description "3x6轻触开关")
      (libsource (lib "屏幕一体板v1") (part "SW 3x6"))
    )
    (comp (ref "TP1")
      (value "TEST")
      (footprint "PCB1:TEST 1.6")
      (description "测试点")
      (libsource (lib "屏幕一体板v1") (part "TEST"))
    )
    (comp (ref "U1")
      (value "STM32F103C8T6")
      (footprint "PCB1:LQFP48_N")
      (libsource (lib "屏幕一体板v1") (part "STM32F103C8T6"))
    )
    (comp (ref "U2")
      (value "STM32H750XBH6")
      (footprint "PCB1:IC_STM32H750XBH6")
      (libsource (lib "屏幕一体板v1") (part "STM32H750XBH6"))
    )
    (comp (ref "U3")
      (value "MT48LC4M32B2B5-6A:L")
      (footprint "PCB1:BGA90C80P9X15_800X1300X100N")
      (description "SDRAM Memory IC 128Mb _4M x 32_ Parallel 167MHz 5.4ns 90-VFBGA _8x13_")
      (libsource (lib "屏幕一体板v1") (part "MT48LC4M32B2B5-6A{colon}L"))
    )
    (comp (ref "U4")
      (value "ZX-TYPEC-WTM1628")
      (footprint "PCB1:USB-C-SMD_ZX-TYPEC-WTM1628")
      (libsource (lib "屏幕一体板v1") (part "ZX-TYPEC-WTM1628"))
    )
    (comp (ref "U5")
      (value "ZX-TYPEC-WTM1628")
      (footprint "PCB1:USB-C-SMD_ZX-TYPEC-WTM1628")
      (libsource (lib "屏幕一体板v1") (part "ZX-TYPEC-WTM1628"))
    )
    (comp (ref "U6")
      (value "LN6206P282MR-G")
      (footprint "PCB1:SOT-23-3_L2.9-W1.3-P1.90-LS2.4-BR")
      (libsource (lib "屏幕一体板v1") (part "LN6206P282MR-G"))
    )
    (comp (ref "U7")
      (value "LN6206P282MR-G")
      (footprint "PCB1:SOT-23-3_L2.9-W1.3-P1.90-LS2.4-BR")
      (libsource (lib "屏幕一体板v1") (part "LN6206P282MR-G"))
    )
    (comp (ref "U8")
      (value "LN6206P152MR-G")
      (footprint "PCB1:SOT-23-3_L2.9-W1.3-P1.90-LS2.4-BR")
      (libsource (lib "屏幕一体板v1") (part "LN6206P282MR-G"))
    )
    (comp (ref "U9")
      (value "TMI7003B")
      (footprint "PCB1:QFN-20_L3.0-W3.0-P0.40-BL-EP1.7")
      (libsource (lib "屏幕一体板v1") (part "TMI7003B"))
    )
    (comp (ref "X1")
      (value "8MHz")
      (footprint "PCB1:XTAL-3215-2P")
      (description "2脚无源晶振(谐振器）")
      (libsource (lib "屏幕一体板v1") (part "XTAL-2P"))
    )
    (comp (ref "X2")
      (value "26M")
      (footprint "PCB1:XTAL-3225-4P")
      (description "4脚无源晶振(谐振器）")
      (libsource (lib "屏幕一体板v1") (part "XTAL-4P"))
    )
    (comp (ref "X3")
      (value "32.768KHZ")
      (footprint "PCB1:XTAL-3215-2P")
      (description "2脚无源晶振(谐振器）")
      (libsource (lib "屏幕一体板v1") (part "XTAL-2P"))
    )
    (comp (ref "X4")
      (value "24M")
      (footprint "PCB1:OSC-3225-4P")
      (description "4脚有源晶振(振荡器)")
      (libsource (lib "屏幕一体板v1") (part "XTAL-ACT-4P"))
    )
  )
  (nets
    (net (code "1") (name "+1.5") (class "Default")
      (node (ref "18") (pin "2") (pinfunction "2_2") (pintype "passive"))
      (node (ref "19") (pin "2") (pinfunction "2_2") (pintype "passive"))
      (node (ref "IC2") (pin "10") (pinfunction "DVDD_10") (pintype "passive"))
      (node (ref "U8") (pin "2") (pinfunction "VOUT_2") (pintype "passive"))
    )
    (net (code "2") (name "+1.8") (class "Default")
      (node (ref "C6") (pin "1") (pinfunction "1_1") (pintype "passive"))
      (node (ref "C60") (pin "2") (pinfunction "2_2") (pintype "passive"))
      (node (ref "C61") (pin "1") (pinfunction "1_1") (pintype "passive"))
      (node (ref "C7") (pin "1") (pinfunction "1_1") (pintype "passive"))
      (node (ref "C8") (pin "1") (pinfunction "1_1") (pintype "passive"))
      (node (ref "L3") (pin "1") (pinfunction "1_1") (pintype "passive"))
      (node (ref "R45") (pin "1") (pinfunction "1_1") (pintype "passive"))
      (node (ref "U2") (pin "A6") (pinfunction "VDDLDO_A6") (pintype "power_in"))
      (node (ref "U2") (pin "C17") (pinfunction "VDDLDO_C17") (pintype "power_in"))
      (node (ref "U2") (pin "U12") (pinfunction "VDDLDO_U12") (pintype "power_in"))
    )
    (net (code "3") (name "+2.8") (class "Default")
      (node (ref "3") (pin "2") (pinfunction "2_2") (pintype "passive"))
      (node (ref "4") (pin "2") (pinfunction "2_2") (pintype "passive"))
      (node (ref "FB3") (pin "2") (pinfunction "2_2") (pintype "passive"))
      (node (ref "FB6") (pin "1") (pinfunction "1_1") (pintype "passive"))
      (node (ref "IC2") (pin "4") (pinfunction "AVDD_4") (pintype "passive"))
      (node (ref "R29") (pin "1") (pinfunction "1_1") (pintype "passive"))
      (node (ref "U6") (pin "2") (pinfunction "VOUT_2") (pintype "passive"))
    )
    (net (code "4") (name "+3.3") (class "Default")
      (node (ref "C10") (pin "2") (pinfunction "2_2") (pintype "passive"))
      (node (ref "C11") (pin "2") (pinfunction "2_2") (pintype "passive"))
      (node (ref "C12") (pin "2") (pinfunction "2_2") (pintype "passive"))
      (node (ref "C13") (pin "2") (pinfunction "2_2") (pintype "passive"))
      (node (ref "C14") (pin "2") (pinfunction "2_2") (pintype "passive"))
      (node (ref "C16") (pin "2") (pinfunction "2_2") (pintype "passive"))
      (node (ref "C17") (pin "2") (pinfunction "2_2") (pintype "passive"))
      (node (ref "C18") (pin "2") (pinfunction "2_2") (pintype "passive"))
      (node (ref "C19") (pin "2") (pinfunction "2_2") (pintype "passive"))
      (node (ref "C20") (pin "2") (pinfunction "2_2") (pintype "passive"))
      (node (ref "C21") (pin "2") (pinfunction "2_2") (pintype "passive"))
      (node (ref "C22") (pin "2") (pinfunction "2_2") (pintype "passive"))
      (node (ref "C23") (pin "2") (pinfunction "2_2") (pintype "passive"))
      (node (ref "C24") (pin "2") (pinfunction "2_2") (pintype "passive"))
      (node (ref "C25") (pin "2") (pinfunction "2_2") (pintype "passive"))
      (node (ref "C26") (pin "2") (pinfunction "2_2") (pintype "passive"))
      (node (ref "C27") (pin "2") (pinfunction "2_2") (pintype "passive"))
      (node (ref "C35") (pin "2") (pinfunction "2_2") (pintype "passive"))
      (node (ref "C36") (pin "2") (pinfunction "2_2") (pintype "passive"))
      (node (ref "C37") (pin "2") (pinfunction "2_2") (pintype "passive"))
      (node (ref "C38") (pin "2") (pinfunction "2_2") (pintype "passive"))
      (node (ref "C39") (pin "2") (pinfunction "2_2") (pintype "passive"))
      (node (ref "C40") (pin "2") (pinfunction "2_2") (pintype "passive"))
      (node (ref "C41") (pin "2") (pinfunction "2_2") (pintype "passive"))
      (node (ref "C42") (pin "2") (pinfunction "2_2") (pintype "passive"))
      (node (ref "C43") (pin "2") (pinfunction "2_2") (pintype "passive"))
      (node (ref "C44") (pin "2") (pinfunction "2_2") (pintype "passive"))
      (node (ref "C45") (pin "2") (pinfunction "2_2") (pintype "passive"))
      (node (ref "C58") (pin "2") (pinfunction "2_2") (pintype "passive"))
      (node (ref "C59") (pin "2") (pinfunction "2_2") (pintype "passive"))
      (node (ref "C9") (pin "2") (pinfunction "2_2") (pintype "passive"))
      (node (ref "D4") (pin "2") (pinfunction "2_2") (pintype "passive"))
      (node (ref "FB1") (pin "2") (pinfunction "2_2") (pintype "passive"))
      (node (ref "FB2") (pin "2") (pinfunction "2_2") (pintype "passive"))
      (node (ref "FB4") (pin "1") (pinfunction "1_1") (pintype "passive"))
      (node (ref "FB5") (pin "1") (pinfunction "1_1") (pintype "passive"))
      (node (ref "FB7") (pin "1") (pinfunction "1_1") (pintype "passive"))
      (node (ref "IC1") (pin "8") (pinfunction "VCC_8") (pintype "passive"))
      (node (ref "JP2") (pin "5") (pinfunction "5_5") (pintype "passive"))
      (node (ref "L2") (pin "1") (pinfunction "1_1") (pintype "passive"))
      (node (ref "P2") (pin "4") (pinfunction "VDD_4") (pintype "passive"))
      (node (ref "R1") (pin "1") (pinfunction "1_1") (pintype "passive"))
      (node (ref "R11") (pin "1") (pinfunction "1_1") (pintype "passive"))
      (node (ref "R12") (pin "1") (pinfunction "1_1") (pintype "passive"))
      (node (ref "R13") (pin "1") (pinfunction "1_1") (pintype "passive"))
      (node (ref "R14") (pin "1") (pinfunction "1_1") (pintype "passive"))
      (node (ref "R15") (pin "1") (pinfunction "1_1") (pintype "passive"))
      (node (ref "R16") (pin "2") (pinfunction "2_2") (pintype "passive"))
      (node (ref "R22") (pin "2") (pinfunction "2_2") (pintype "passive"))
      (node (ref "R26") (pin "1") (pinfunction "1_1") (pintype "passive"))
      (node (ref "R28") (pin "1") (pinfunction "1_1") (pintype "passive"))
      (node (ref "R30") (pin "2") (pinfunction "2_2") (pintype "passive"))
      (node (ref "R31") (pin "2") (pinfunction "2_2") (pintype "passive"))
      (node (ref "R32") (pin "2") (pinfunction "2_2") (pintype "passive"))
      (node (ref "R39") (pin "2") (pinfunction "2_2") (pintype "passive"))
      (node (ref "R4") (pin "2") (pinfunction "2_2") (pintype "passive"))
      (node (ref "R40") (pin "2") (pinfunction "2_2") (pintype "passive"))
      (node (ref "R42") (pin "2") (pinfunction "2_2") (pintype "passive"))
      (node (ref "R43") (pin "1") (pinfunction "1_1") (pintype "passive"))
      (node (ref "R7") (pin "1") (pinfunction "1_1") (pintype "passive"))
      (node (ref "R9") (pin "1") (pinfunction "1_1") (pintype "passive"))
      (node (ref "SW1") (pin "1") (pinfunction "1_1") (pintype "passive"))
      (node (ref "SW3") (pin "1") (pinfunction "1_1") (pintype "passive"))
      (node (ref "U1") (pin "1") (pinfunction "VBAT_1") (pintype "power_in"))
      (node (ref "U1") (pin "24") (pinfunction "VDD_1_24") (pintype "power_in"))
      (node (ref "U1") (pin "36") (pinfunction "VDD_2_36") (pintype "power_in"))
      (node (ref "U1") (pin "48") (pinfunction "VDD_3_48") (pintype "power_in"))
      (node (ref "U1") (pin "9") (pinfunction "VDDA_9") (pintype "power_in"))
      (node (ref "U2") (pin "E11") (pinfunction "VDD_1_E11") (pintype "power_in"))
      (node (ref "U2") (pin "E6") (pinfunction "VDD_1_E6") (pintype "power_in"))
      (node (ref "U2") (pin "E9") (pinfunction "VDD_1_E9") (pintype "power_in"))
      (node (ref "U2") (pin "F17") (pinfunction "VDD33USB_F17") (pintype "power_in"))
      (node (ref "U2") (pin "F5") (pinfunction "VDD_1_F5") (pintype "power_in"))
      (node (ref "U2") (pin "G13") (pinfunction "VDD_1_G13") (pintype "power_in"))
      (node (ref "U2") (pin "G17") (pinfunction "VDD50USB_G17") (pintype "power_in"))
      (node (ref "U2") (pin "G5") (pinfunction "VDD_1_G5") (pintype "power_in"))
      (node (ref "U2") (pin "H13") (pinfunction "VDD_1_H13") (pintype "power_in"))
      (node (ref "U2") (pin "H5") (pinfunction "VDD_1_H5") (pintype "power_in"))
      (node (ref "U2") (pin "J13") (pinfunction "VDD_1_J13") (pintype "power_in"))
      (node (ref "U2") (pin "K13") (pinfunction "VDD_1_K13") (pintype "power_in"))
      (node (ref "U2") (pin "K5") (pinfunction "VDD_2_K5") (pintype "power_in"))
      (node (ref "U2") (pin "L13") (pinfunction "VDD_1_L13") (pintype "power_in"))
      (node (ref "U2") (pin "L5") (pinfunction "VDD_2_L5") (pintype "power_in"))
      (node (ref "U2") (pin "M13") (pinfunction "VDD_2_M13") (pintype "power_in"))
      (node (ref "U2") (pin "M5") (pinfunction "VDD_2_M5") (pintype "power_in"))
      (node (ref "U2") (pin "N10") (pinfunction "VDD_2_N10") (pintype "power_in"))
      (node (ref "U2") (pin "N11") (pinfunction "VDD_2_N11") (pintype "power_in"))
      (node (ref "U2") (pin "N12") (pinfunction "VDD_2_N12") (pintype "power_in"))
      (node (ref "U2") (pin "N7") (pinfunction "VDD_2_N7") (pintype "power_in"))
      (node (ref "U2") (pin "N8") (pinfunction "VDD_2_N8") (pintype "power_in"))
      (node (ref "U2") (pin "P17") (pinfunction "VDD_2_P17") (pintype "power_in"))
      (node (ref "U3") (pin "A7") (pinfunction "VDD_A7") (pintype "power_in"))
      (node (ref "U3") (pin "B2") (pinfunction "VDDQ_B2") (pintype "power_in"))
      (node (ref "U3") (pin "B7") (pinfunction "VDDQ_B7") (pintype "power_in"))
      (node (ref "U3") (pin "C9") (pinfunction "VDDQ_C9") (pintype "power_in"))
      (node (ref "U3") (pin "D9") (pinfunction "VDDQ_D9") (pintype "power_in"))
      (node (ref "U3") (pin "E1") (pinfunction "VDDQ_E1") (pintype "power_in"))
      (node (ref "U3") (pin "F9") (pinfunction "VDD_F9") (pintype "power_in"))
      (node (ref "U3") (pin "L1") (pinfunction "VDDQ_L1") (pintype "power_in"))
      (node (ref "U3") (pin "L7") (pinfunction "VDD_L7") (pintype "power_in"))
      (node (ref "U3") (pin "M9") (pinfunction "VDDQ_M9") (pintype "power_in"))
      (node (ref "U3") (pin "N9") (pinfunction "VDDQ_N9") (pintype "power_in"))
      (node (ref "U3") (pin "P2") (pinfunction "VDDQ_P2") (pintype "power_in"))
      (node (ref "U3") (pin "P7") (pinfunction "VDDQ_P7") (pintype "power_in"))
      (node (ref "U3") (pin "R7") (pinfunction "VDD_R7") (pintype "power_in"))
      (node (ref "U9") (pin "7") (pinfunction "VIN2_7") (pintype "passive"))
      (node (ref "U9") (pin "8") (pinfunction "EN2_8") (pintype "passive"))
    )
    (net (code "5") (name "+5") (class "Default")
      (node (ref "5") (pin "2") (pinfunction "2_2") (pintype "passive"))
      (node (ref "6") (pin "2") (pinfunction "2_2") (pintype "passive"))
      (node (ref "8") (pin "5") (pinfunction "VIN_5") (pintype "bidirectional"))
      (node (ref "D2") (pin "2") (pinfunction "K_2") (pintype "passive"))
      (node (ref "E1") (pin "1") (pinfunction "1_1") (pintype "passive"))
      (node (ref "E2") (pin "1") (pinfunction "1_1") (pintype "passive"))
      (node (ref "E3") (pin "1") (pinfunction "1_1") (pintype "passive"))
      (node (ref "JP2") (pin "3") (pinfunction "3_3") (pintype "passive"))
      (node (ref "L1") (pin "2") (pinfunction "2_2") (pintype "passive"))
      (node (ref "U4") (pin "A4B9") (pinfunction "VBUS_A4B9") (pintype "passive"))
      (node (ref "U4") (pin "B4A9") (pinfunction "VBUS_B4A9") (pintype "passive"))
      (node (ref "U5") (pin "A4B9") (pinfunction "VBUS_A4B9") (pintype "passive"))
      (node (ref "U5") (pin "B4A9") (pinfunction "VBUS_B4A9") (pintype "passive"))
      (node (ref "U9") (pin "18") (pinfunction "EN3_18") (pintype "passive"))
      (node (ref "U9") (pin "19") (pinfunction "VIN3_19") (pintype "passive"))
    )
    (net (code "6") (name "/BOOT0") (class "Default")
      (node (ref "LED3") (pin "1") (pinfunction "A_1") (pintype "passive"))
      (node (ref "Q2") (pin "2") (pinfunction "E_2") (pintype "passive"))
      (node (ref "R25") (pin "2") (pinfunction "2_2") (pintype "passive"))
      (node (ref "U2") (pin "E8") (pinfunction "BOOT0_E8") (pintype "input"))
    )
    (net (code "7") (name "/CAM_PWDN {slash} PG7") (class "Default")
      (node (ref "IC2") (pin "8") (pinfunction "PWDN_8") (pintype "passive"))
      (node (ref "R30") (pin "1") (pinfunction "1_1") (pintype "passive"))
      (node (ref "U2") (pin "F16") (pinfunction "PG7/HRTIM_CHE2/SAI1_MCLK_A/USART6_CK/FMC_INT/DCMI_D13/LCD_CLK/EVENTOUT_F16") (pintype "bidirectional"))
    )
    (net (code "8") (name "/DAP_BOOT0") (class "Default")
      (node (ref "R5") (pin "2") (pinfunction "2_2") (pintype "passive"))
      (node (ref "TP1") (pin "1") (pinfunction "1_1") (pintype "passive"))
      (node (ref "U1") (pin "44") (pinfunction "BOOT0_44") (pintype "input"))
    )
    (net (code "9") (name "/DAP_DM") (class "Default")
      (node (ref "U1") (pin "32") (pinfunction "PA11_32") (pintype "bidirectional"))
      (node (ref "U4") (pin "A7") (pinfunction "DN1_A7") (pintype "passive"))
      (node (ref "U4") (pin "B7") (pinfunction "DN2_B7") (pintype "passive"))
    )
    (net (code "10") (name "/DAP_DP") (class "Default")
      (node (ref "U1") (pin "33") (pinfunction "PA12_33") (pintype "bidirectional"))
      (node (ref "U4") (pin "A6") (pinfunction "DP1_A6") (pintype "passive"))
      (node (ref "U4") (pin "B6") (pinfunction "DP2_B6") (pintype "passive"))
    )
    (net (code "11") (name "/DAP_LED1") (class "Default")
      (node (ref "R6") (pin "1") (pinfunction "1_1") (pintype "passive"))
      (node (ref "U1") (pin "25") (pinfunction "PB12_25") (pintype "bidirectional"))
    )
    (net (code "12") (name "/DAP_LED2") (class "Default")
      (node (ref "R3") (pin "1") (pinfunction "1_1") (pintype "passive"))
      (node (ref "U1") (pin "45") (pinfunction "PB8_45") (pintype "bidirectional"))
    )
    (net (code "13") (name "/DAP_RST") (class "Default")
      (node (ref "JP1") (pin "9") (pinfunction "9_9") (pintype "passive"))
      (node (ref "R52") (pin "1") (pinfunction "1_1") (pintype "passive"))
      (node (ref "U1") (pin "16") (pinfunction "PA6_16") (pintype "bidirectional"))
    )
    (net (code "14") (name "/DAP_RXD") (class "Default")
      (node (ref "JP1") (pin "7") (pinfunction "7_7") (pintype "passive"))
      (node (ref "R51") (pin "1") (pinfunction "1_1") (pintype "passive"))
      (node (ref "U1") (pin "31") (pinfunction "PA10_31") (pintype "bidirectional"))
    )
    (net (code "15") (name "/DAP_TCK{slash}CK") (class "Default")
      (node (ref "R10") (pin "1") (pinfunction "1_1") (pintype "passive"))
      (node (ref "R9") (pin "2") (pinfunction "2_2") (pintype "passive"))
      (node (ref "U1") (pin "14") (pinfunction "PA4_14") (pintype "bidirectional"))
    )
    (net (code "16") (name "/DAP_TMS{slash}IO") (class "Default")
      (node (ref "R7") (pin "2") (pinfunction "2_2") (pintype "passive"))
      (node (ref "R8") (pin "1") (pinfunction "1_1") (pintype "passive"))
      (node (ref "U1") (pin "12") (pinfunction "PA2_12") (pintype "bidirectional"))
    )
    (net (code "17") (name "/DAP_TXD") (class "Default")
      (node (ref "JP1") (pin "5") (pinfunction "5_5") (pintype "passive"))
      (node (ref "R50") (pin "1") (pinfunction "1_1") (pintype "passive"))
      (node (ref "U1") (pin "30") (pinfunction "PA9_30") (pintype "bidirectional"))
    )
    (net (code "18") (name "/DAP_nRST") (class "Default")
      (node (ref "C15") (pin "2") (pinfunction "2_2") (pintype "passive"))
      (node (ref "R4") (pin "1") (pinfunction "1_1") (pintype "passive"))
      (node (ref "U1") (pin "7") (pinfunction "NRST_7") (pintype "bidirectional"))
    )
    (net (code "19") (name "/DCMI_D0 {slash} PC6") (class "Default")
      (node (ref "IC2") (pin "19") (pinfunction "Y2_19") (pintype "passive"))
      (node (ref "U2") (pin "F14") (pinfunction "PC6/HRTIM_CHA1/TIM3_CH1/TIM8_CH1/DFSDM1_CKIN3/I2S2_MCK/USART6_TX/SDMMC1_D0DIR/FMC_NWAIT/SDMMC2_D6/SDMMC1_D6/DCMI_D0/LCD_HSYNC/EVENTOUT_F14") (pintype "bidirectional"))
    )
    (net (code "20") (name "/DCMI_D1 {slash} PC7") (class "Default")
      (node (ref "IC2") (pin "21") (pinfunction "Y3_21") (pintype "passive"))
      (node (ref "U2") (pin "F13") (pinfunction "PC7/TRGIO/HRTIM_CHA2/TIM3_CH2/TIM8_CH2/DFSDM1_DATIN3/I2S3_MCK/USART6_RX/SDMMC1_D123DIR/FMC_NE1/SDMMC2_D7/SWPMI_TX/SDMMC1_D7/DCMI_D1/LCD_G6/EVENTOUT_F13") (pintype "bidirectional"))
    )
    (net (code "21") (name "/DCMI_D2 {slash} PG10") (class "Default")
      (node (ref "IC2") (pin "22") (pinfunction "Y4_22") (pintype "passive"))
      (node (ref "U2") (pin "A9") (pinfunction "PG10/HRTIM_FLT5/SPI1_NSS/I2S1_WS/LCD_G3/SAI2_SD_B/FMC_NE3/DCMI_D2/LCD_B2/EVENTOUT_A9") (pintype "bidirectional"))
    )
    (net (code "22") (name "/DCMI_D3 {slash} PG11") (class "Default")
      (node (ref "IC2") (pin "20") (pinfunction "Y5_20") (pintype "passive"))
      (node (ref "U2") (pin "B9") (pinfunction "PG11/LPTIM1_IN2/HRTIM_EEV4/SPI1_SCK/I2S1_CK/SPDIFRX1_IN1/SDMMC2_D2/ETH_MII_TX_EN/ETH_RMII_TX_EN/DCMI_D3/LCD_B3/EVENTOUT_B9") (pintype "bidirectional"))
    )
    (net (code "23") (name "/DCMI_D4 {slash} PE4") (class "Default")
      (node (ref "IC2") (pin "18") (pinfunction "Y6_18") (pintype "passive"))
      (node (ref "U2") (pin "D2") (pinfunction "PE4/TRACED1/SAI1_D2/DFSDM1_DATIN3/TIM15_CH1N/SPI4_NSS/SAI1_FS_A/SAI4_FS_A/SAI4_D2/FMC_A20/DCMI_D4/LCD_B0/EVENTOUT_D2") (pintype "bidirectional"))
    )
    (net (code "24") (name "/DCMI_D5 {slash} PD3") (class "Default")
      (node (ref "IC2") (pin "16") (pinfunction "Y7_16") (pintype "passive"))
      (node (ref "U2") (pin "B12") (pinfunction "PD3/DFSDM1_CKOUT/SPI2_SCK/I2S2_CK/USART2_CTS/USART2_NSS/FMC_CLK/DCMI_D5/LCD_G7/EVENTOUT_B12") (pintype "bidirectional"))
    )
    (net (code "25") (name "/DCMI_D6 {slash} PE5") (class "Default")
      (node (ref "IC2") (pin "14") (pinfunction "Y8_14") (pintype "passive"))
      (node (ref "U2") (pin "D1") (pinfunction "PE5/TRACED2/SAI1_CK2/DFSDM1_CKIN3/TIM15_CH1/SPI4_MISO/SAI1_SCK_A/SAI4_SCK_A/SAI4_CK2/FMC_A21/DCMI_D6/LCD_G0/EVENTOUT_D1") (pintype "bidirectional"))
    )
    (net (code "26") (name "/DCMI_D7 {slash} PE6") (class "Default")
      (node (ref "IC2") (pin "12") (pinfunction "Y9_12") (pintype "passive"))
      (node (ref "U2") (pin "E5") (pinfunction "PE6/TRACED3/TIM1_BKIN2/SAI1_D1/TIM15_CH2/SPI4_MOSI/SAI1_SD_A/SAI4_SD_A/SAI4_D1/SAI2_MCLK_B/TIM1_BKIN2_COMP12/FMC_A22/DCMI_D7/LCD_G1/EVENTOUT_E5") (pintype "bidirectional"))
    )
    (net (code "27") (name "/DCMI_HSYNC {slash} PA4") (class "Default")
      (node (ref "IC2") (pin "9") (pinfunction "HSYNC_9") (pintype "passive"))
      (node (ref "U2") (pin "U3") (pinfunction "PA4/D1PWREN/TIM5_ETR/SPI1_NSS/I2S1_WS/SPI3_NSS/I2S3_WS/USART2_CK/SPI6_NSS/OTG_HS_SOF/DCMI_HSYNC/LCD_VSYNC/EVENTOUT_U3") (pintype "bidirectional"))
    )
    (net (code "28") (name "/DCMI_PIXCLK {slash} PA6") (class "Default")
      (node (ref "IC2") (pin "17") (pinfunction "PCLK_17") (pintype "passive"))
      (node (ref "U2") (pin "R3") (pinfunction "PA6/TIM1_BKIN/TIM3_CH1/TIM8_BKIN/SPI1_MISO/I2S1_SDI/SPI6_MISO/TIM13_CH1/TIM8_BKIN_COMP12/MDIOS_MDC/TIM1_BKIN_COMP12/DCMI_PIXCLK/LCD_G2/EVENTOUT_R3") (pintype "bidirectional"))
    )
    (net (code "29") (name "/DCMI_VSYNC {slash} PG9") (class "Default")
      (node (ref "IC2") (pin "7") (pinfunction "VSYNC_7") (pintype "passive"))
      (node (ref "U2") (pin "A10") (pinfunction "PG9/SPI1_MISO/I2S1_SDI/USART6_RX/SPDIFRX1_IN4/QUADSPI_BK2_IO2/SAI2_FS_B/FMC_NE2/FMC_NCE/DCMI_VSYNC/EVENTOUT_A10") (pintype "bidirectional"))
    )
    (net (code "30") (name "/DISP") (class "Default")
      (node (ref "FPC1") (pin "31") (pinfunction "31_31") (pintype "passive"))
      (node (ref "R44") (pin "2") (pinfunction "2_2") (pintype "passive"))
    )
    (net (code "31") (name "/FMC_A0 {slash} PF0") (class "Default")
      (node (ref "U2") (pin "G4") (pinfunction "PF0/I2C2_SDA/FMC_A0/EVENTOUT_G4") (pintype "bidirectional"))
      (node (ref "U3") (pin "G8") (pinfunction "A0_G8") (pintype "input"))
    )
    (net (code "32") (name "/FMC_A1 {slash} PF1") (class "Default")
      (node (ref "U2") (pin "G3") (pinfunction "PF1/I2C2_SCL/FMC_A1/EVENTOUT_G3") (pintype "bidirectional"))
      (node (ref "U3") (pin "G9") (pinfunction "A1_G9") (pintype "input"))
    )
    (net (code "33") (name "/FMC_A2 {slash} PF2") (class "Default")
      (node (ref "U2") (pin "G1") (pinfunction "PF2/I2C2_SMBA/FMC_A2/EVENTOUT_G1") (pintype "bidirectional"))
      (node (ref "U3") (pin "F7") (pinfunction "A2_F7") (pintype "input"))
    )
    (net (code "34") (name "/FMC_A3 {slash} PF3") (class "Default")
      (node (ref "U2") (pin "H4") (pinfunction "PF3/FMC_A3/EVENTOUT_H4") (pintype "bidirectional"))
      (node (ref "U3") (pin "F3") (pinfunction "A3_F3") (pintype "input"))
    )
    (net (code "35") (name "/FMC_A4 {slash} PF4") (class "Default")
      (node (ref "U2") (pin "J5") (pinfunction "PF4/FMC_A4/EVENTOUT_J5") (pintype "bidirectional"))
      (node (ref "U3") (pin "G1") (pinfunction "A4_G1") (pintype "input"))
    )
    (net (code "36") (name "/FMC_A5 {slash} PF5") (class "Default")
      (node (ref "U2") (pin "J4") (pinfunction "PF5/FMC_A5/EVENTOUT_J4") (pintype "bidirectional"))
      (node (ref "U3") (pin "G2") (pinfunction "A5_G2") (pintype "input"))
    )
    (net (code "37") (name "/FMC_A6 {slash} PF12") (class "Default")
      (node (ref "U2") (pin "R7") (pinfunction "PF12/FMC_A6/EVENTOUT_R7") (pintype "bidirectional"))
      (node (ref "U3") (pin "G3") (pinfunction "A6_G3") (pintype "input"))
    )
    (net (code "38") (name "/FMC_A7 {slash} PF13") (class "Default")
      (node (ref "U2") (pin "P7") (pinfunction "PF13/DFSDM1_DATIN6/I2C4_SMBA/FMC_A7/EVENTOUT_P7") (pintype "bidirectional"))
      (node (ref "U3") (pin "H1") (pinfunction "A7_H1") (pintype "input"))
    )
    (net (code "39") (name "/FMC_A8 {slash} PF14") (class "Default")
      (node (ref "U2") (pin "P8") (pinfunction "PF14/DFSDM1_CKIN6/I2C4_SCL/FMC_A8/EVENTOUT_P8") (pintype "bidirectional"))
      (node (ref "U3") (pin "H2") (pinfunction "A8_H2") (pintype "input"))
    )
    (net (code "40") (name "/FMC_A9 {slash} PF15") (class "Default")
      (node (ref "U2") (pin "R9") (pinfunction "PF15/I2C4_SDA/FMC_A9/EVENTOUT_R9") (pintype "bidirectional"))
      (node (ref "U3") (pin "J3") (pinfunction "A9_J3") (pintype "input"))
    )
    (net (code "41") (name "/FMC_A10 {slash} PG0") (class "Default")
      (node (ref "U2") (pin "T8") (pinfunction "PG0/FMC_A10/EVENTOUT_T8") (pintype "bidirectional"))
      (node (ref "U3") (pin "G7") (pinfunction "A10_G7") (pintype "input"))
    )
    (net (code "42") (name "/FMC_A11 {slash} PG1") (class "Default")
      (node (ref "U2") (pin "U8") (pinfunction "PG1/FMC_A11/EVENTOUT_U8") (pintype "bidirectional"))
      (node (ref "U3") (pin "H9") (pinfunction "A11_H9") (pintype "input"))
    )
    (net (code "43") (name "/FMC_BA0 {slash} PG4") (class "Default")
      (node (ref "U2") (pin "H14") (pinfunction "PG4/TIM1_BKIN2/TIM1_BKIN2_COMP12/FMC_A14/FMC_BA0/EVENTOUT_H14") (pintype "bidirectional"))
      (node (ref "U3") (pin "J7") (pinfunction "BA0_J7") (pintype "input"))
    )
    (net (code "44") (name "/FMC_BA1 {slash} PG5") (class "Default")
      (node (ref "U2") (pin "G14") (pinfunction "PG5/TIM1_ETR/FMC_A15/FMC_BA1/EVENTOUT_G14") (pintype "bidirectional"))
      (node (ref "U3") (pin "H8") (pinfunction "BA1_H8") (pintype "input"))
    )
    (net (code "45") (name "/FMC_D0 {slash} PD14") (class "Default")
      (node (ref "U2") (pin "P16") (pinfunction "PD14/TIM4_CH3/SAI3_MCLK_B/UART8_CTS/FMC_D0/FMC_DA0/EVENTOUT_P16") (pintype "bidirectional"))
      (node (ref "U3") (pin "R8") (pinfunction "DQ0_R8") (pintype "bidirectional"))
    )
    (net (code "46") (name "/FMC_D1 {slash} PD15") (class "Default")
      (node (ref "U2") (pin "P15") (pinfunction "PD15/TIM4_CH4/SAI3_MCLK_A/UART8_RTS/UART8_DE/FMC_D1/FMC_DA1/EVENTOUT_P15") (pintype "bidirectional"))
      (node (ref "U3") (pin "N7") (pinfunction "DQ1_N7") (pintype "bidirectional"))
    )
    (net (code "47") (name "/FMC_D2 {slash} PD0") (class "Default")
      (node (ref "U2") (pin "D13") (pinfunction "PD0/DFSDM1_CKIN6/SAI3_SCK_A/UART4_RX/FDCAN1_RX/FMC_D2/FMC_DA2/EVENTOUT_D13") (pintype "bidirectional"))
      (node (ref "U3") (pin "R9") (pinfunction "DQ2_R9") (pintype "bidirectional"))
    )
    (net (code "48") (name "/FMC_D3 {slash} PD1") (class "Default")
      (node (ref "U2") (pin "E12") (pinfunction "PD1/DFSDM1_DATIN6/SAI3_SD_A/UART4_TX/FDCAN1_TX/FMC_D3/FMC_DA3/EVENTOUT_E12") (pintype "bidirectional"))
      (node (ref "U3") (pin "N8") (pinfunction "DQ3_N8") (pintype "bidirectional"))
    )
    (net (code "49") (name "/FMC_D4 {slash} PE7") (class "Default")
      (node (ref "U2") (pin "U9") (pinfunction "PE7/TIM1_ETR/DFSDM1_DATIN2/UART7_RX/QUADSPI_BK2_IO0/FMC_D4/FMC_DA4/EVENTOUT_U9") (pintype "bidirectional"))
      (node (ref "U3") (pin "P9") (pinfunction "DQ4_P9") (pintype "bidirectional"))
    )
    (net (code "50") (name "/FMC_D5 {slash} PE8") (class "Default")
      (node (ref "U2") (pin "T9") (pinfunction "PE8/TIM1_CH1N/DFSDM1_CKIN2/UART7_TX/QUADSPI_BK2_IO1/FMC_D5/FMC_DA5/COMP2_OUT/EVENTOUT_T9") (pintype "bidirectional"))
      (node (ref "U3") (pin "M8") (pinfunction "DQ5_M8") (pintype "bidirectional"))
    )
    (net (code "51") (name "/FMC_D6 {slash} PE9") (class "Default")
      (node (ref "U2") (pin "P9") (pinfunction "PE9/TIM1_CH1/DFSDM1_CKOUT/UART7_RTS/UART7_DE/QUADSPI_BK2_IO2/FMC_D6/FMC_DA6/EVENTOUT_P9") (pintype "bidirectional"))
      (node (ref "U3") (pin "M7") (pinfunction "DQ6_M7") (pintype "bidirectional"))
    )
    (net (code "52") (name "/FMC_D7 {slash} PE10") (class "Default")
      (node (ref "U2") (pin "N9") (pinfunction "PE10/TIM1_CH2N/DFSDM1_DATIN4/UART7_CTS/QUADSPI_BK2_IO3/FMC_D7/FMC_DA7/EVENTOUT_N9") (pintype "bidirectional"))
      (node (ref "U3") (pin "L8") (pinfunction "DQ7_L8") (pintype "bidirectional"))
    )
    (net (code "53") (name "/FMC_D8 {slash} PE11") (class "Default")
      (node (ref "U2") (pin "P10") (pinfunction "PE11/TIM1_CH2/DFSDM1_CKIN4/SPI4_NSS/SAI2_SD_B/FMC_D8/FMC_DA8/LCD_G3/EVENTOUT_P10") (pintype "bidirectional"))
      (node (ref "U3") (pin "L2") (pinfunction "DQ8_L2") (pintype "bidirectional"))
    )
    (net (code "54") (name "/FMC_D9 {slash} PE12") (class "Default")
      (node (ref "U2") (pin "R10") (pinfunction "PE12/TIM1_CH3N/DFSDM1_DATIN5/SPI4_SCK/SAI2_SCK_B/FMC_D9/FMC_DA9/COMP1_OUT/LCD_B4/EVENTOUT_R10") (pintype "bidirectional"))
      (node (ref "U3") (pin "M3") (pinfunction "DQ9_M3") (pintype "bidirectional"))
    )
    (net (code "55") (name "/FMC_D10 {slash} PE13") (class "Default")
      (node (ref "U2") (pin "T10") (pinfunction "PE13/TIM1_CH3/DFSDM1_CKIN5/SPI4_MISO/SAI2_FS_B/FMC_D10/FMC_DA10/COMP2_OUT/LCD_DE/EVENTOUT_T10") (pintype "bidirectional"))
      (node (ref "U3") (pin "M2") (pinfunction "DQ10_M2") (pintype "bidirectional"))
    )
    (net (code "56") (name "/FMC_D11 {slash} PE14") (class "Default")
      (node (ref "U2") (pin "U10") (pinfunction "PE14/TIM1_CH4/SPI4_MOSI/SAI2_MCLK_B/FMC_D11/FMC_DA11/LCD_CLK/EVENTOUT_U10") (pintype "bidirectional"))
      (node (ref "U3") (pin "P1") (pinfunction "DQ11_P1") (pintype "bidirectional"))
    )
    (net (code "57") (name "/FMC_D12 {slash} PE15") (class "Default")
      (node (ref "U2") (pin "R11") (pinfunction "PE15/TIM1_BKIN/FMC_D12/FMC_DA12/TIM1_BKIN_COMP12/COMP_TIM1_BKIN/LCD_R7/EVENTOUT_R11") (pintype "bidirectional"))
      (node (ref "U3") (pin "N2") (pinfunction "DQ12_N2") (pintype "bidirectional"))
    )
    (net (code "58") (name "/FMC_D13 {slash} PD8") (class "Default")
      (node (ref "U2") (pin "U16") (pinfunction "PD8/DFSDM1_CKIN3/SAI3_SCK_B/USART3_TX/SPDIFRX1_IN2/FMC_D13/FMC_DA13/EVENTOUT_U16") (pintype "bidirectional"))
      (node (ref "U3") (pin "R1") (pinfunction "DQ13_R1") (pintype "bidirectional"))
    )
    (net (code "59") (name "/FMC_D14 {slash} PD9") (class "Default")
      (node (ref "U2") (pin "T17") (pinfunction "PD9/DFSDM1_DATIN3/SAI3_SD_B/USART3_RX/FDCAN2_RXFD_MODE/FMC_D14/FMC_DA14/EVENTOUT_T17") (pintype "bidirectional"))
      (node (ref "U3") (pin "N3") (pinfunction "DQ14_N3") (pintype "bidirectional"))
    )
    (net (code "60") (name "/FMC_D15 {slash} PD10") (class "Default")
      (node (ref "U2") (pin "T16") (pinfunction "PD10/DFSDM1_CKOUT/SAI3_FS_B/USART3_CK/FDCAN2_TXFD_MODE/FMC_D15/FMC_DA15/LCD_B3/EVENTOUT_T16") (pintype "bidirectional"))
      (node (ref "U3") (pin "R2") (pinfunction "DQ15_R2") (pintype "bidirectional"))
    )
    (net (code "61") (name "/FMC_D16 {slash} PH8") (class "Default")
      (node (ref "U2") (pin "T13") (pinfunction "PH8/TIM5_ETR/I2C3_SDA/FMC_D16/DCMI_HSYNC/LCD_R2/EVENTOUT_T13") (pintype "bidirectional"))
      (node (ref "U3") (pin "E8") (pinfunction "DQ16_E8") (pintype "bidirectional"))
    )
    (net (code "62") (name "/FMC_D17 {slash} PH9") (class "Default")
      (node (ref "U2") (pin "R13") (pinfunction "PH9/TIM12_CH2/I2C3_SMBA/FMC_D17/DCMI_D0/LCD_R3/EVENTOUT_R13") (pintype "bidirectional"))
      (node (ref "U3") (pin "D7") (pinfunction "DQ17_D7") (pintype "bidirectional"))
    )
    (net (code "63") (name "/FMC_D18 {slash} PH10") (class "Default")
      (node (ref "U2") (pin "P13") (pinfunction "PH10/TIM5_CH1/I2C4_SMBA/FMC_D18/DCMI_D1/LCD_R4/EVENTOUT_P13") (pintype "bidirectional"))
      (node (ref "U3") (pin "D8") (pinfunction "DQ18_D8") (pintype "bidirectional"))
    )
    (net (code "64") (name "/FMC_D19 {slash} PH11") (class "Default")
      (node (ref "U2") (pin "P14") (pinfunction "PH11/TIM5_CH2/I2C4_SCL/FMC_D19/DCMI_D2/LCD_R5/EVENTOUT_P14") (pintype "bidirectional"))
      (node (ref "U3") (pin "B9") (pinfunction "DQ19_B9") (pintype "bidirectional"))
    )
    (net (code "65") (name "/FMC_D20 {slash} PH12") (class "Default")
      (node (ref "U2") (pin "R14") (pinfunction "PH12/TIM5_CH3/I2C4_SDA/FMC_D20/DCMI_D3/LCD_R6/EVENTOUT_R14") (pintype "bidirectional"))
      (node (ref "U3") (pin "C8") (pinfunction "DQ20_C8") (pintype "bidirectional"))
    )
    (net (code "66") (name "/FMC_D21 {slash} PH13") (class "Default")
      (node (ref "U2") (pin "D16") (pinfunction "PH13/TIM8_CH1N/UART4_TX/FDCAN1_TX/FMC_D21/LCD_G2/EVENTOUT_D16") (pintype "bidirectional"))
      (node (ref "U3") (pin "A9") (pinfunction "DQ21_A9") (pintype "bidirectional"))
    )
    (net (code "67") (name "/FMC_D22 {slash} PH14") (class "Default")
      (node (ref "U2") (pin "B17") (pinfunction "PH14/TIM8_CH2N/UART4_RX/FDCAN1_RX/FMC_D22/DCMI_D4/LCD_G3/EVENTOUT_B17") (pintype "bidirectional"))
      (node (ref "U3") (pin "C7") (pinfunction "DQ22_C7") (pintype "bidirectional"))
    )
    (net (code "68") (name "/FMC_D23 {slash} PH15") (class "Default")
      (node (ref "U2") (pin "B16") (pinfunction "PH15/TIM8_CH3N/FDCAN1_TXFD_MODE/FMC_D23/DCMI_D11/LCD_G4/EVENTOUT_B16") (pintype "bidirectional"))
      (node (ref "U3") (pin "A8") (pinfunction "DQ23_A8") (pintype "bidirectional"))
    )
    (net (code "69") (name "/FMC_D24 {slash} PI0") (class "Default")
      (node (ref "U2") (pin "A16") (pinfunction "PI0/TIM5_CH4/SPI2_NSS/I2S2_WS/FDCAN1_RXFD_MODE/FMC_D24/DCMI_D13/LCD_G5/EVENTOUT_A16") (pintype "bidirectional"))
      (node (ref "U3") (pin "A2") (pinfunction "DQ24_A2") (pintype "bidirectional"))
    )
    (net (code "70") (name "/FMC_D25 {slash} PI1") (class "Default")
      (node (ref "U2") (pin "A15") (pinfunction "PI1/TIM8_BKIN2/SPI2_SCK/I2S2_CK/TIM8_BKIN2_COMP12/FMC_D25/DCMI_D8/LCD_G6/EVENTOUT_A15") (pintype "bidirectional"))
      (node (ref "U3") (pin "C3") (pinfunction "DQ25_C3") (pintype "bidirectional"))
    )
    (net (code "71") (name "/FMC_D26 {slash} PI2") (class "Default")
      (node (ref "U2") (pin "B15") (pinfunction "PI2/TIM8_CH4/SPI2_MISO/I2S2_SDI/FMC_D26/DCMI_D9/LCD_G7/EVENTOUT_B15") (pintype "bidirectional"))
      (node (ref "U3") (pin "A1") (pinfunction "DQ26_A1") (pintype "bidirectional"))
    )
    (net (code "72") (name "/FMC_D27 {slash} PI3") (class "Default")
      (node (ref "U2") (pin "C14") (pinfunction "PI3/TIM8_ETR/SPI2_MOSI/I2S2_SDO/FMC_D27/DCMI_D10/EVENTOUT_C14") (pintype "bidirectional"))
      (node (ref "U3") (pin "C2") (pinfunction "DQ27_C2") (pintype "bidirectional"))
    )
    (net (code "73") (name "/FMC_D28 {slash} PI6") (class "Default")
      (node (ref "U2") (pin "A2") (pinfunction "PI6/TIM8_CH2/SAI2_SD_A/FMC_D28/DCMI_D6/LCD_B6/EVENTOUT_A2") (pintype "bidirectional"))
      (node (ref "U3") (pin "B1") (pinfunction "DQ28_B1") (pintype "bidirectional"))
    )
    (net (code "74") (name "/FMC_D29 {slash} PI7") (class "Default")
      (node (ref "U2") (pin "B3") (pinfunction "PI7/TIM8_CH3/SAI2_FS_A/FMC_D29/DCMI_D7/LCD_B7/EVENTOUT_B3") (pintype "bidirectional"))
      (node (ref "U3") (pin "D2") (pinfunction "DQ29_D2") (pintype "bidirectional"))
    )
    (net (code "75") (name "/FMC_D30 {slash} PI9") (class "Default")
      (node (ref "U2") (pin "E2") (pinfunction "PI9/UART4_RX/FDCAN1_RX/FMC_D30/LCD_VSYNC/EVENTOUT_E2") (pintype "bidirectional"))
      (node (ref "U3") (pin "D3") (pinfunction "DQ30_D3") (pintype "bidirectional"))
    )
    (net (code "76") (name "/FMC_D31 {slash} PI10") (class "Default")
      (node (ref "U2") (pin "F3") (pinfunction "PI10/FDCAN1_RXFD_MODE/ETH_MII_RX_ER/FMC_D31/LCD_HSYNC/EVENTOUT_F3") (pintype "bidirectional"))
      (node (ref "U3") (pin "E2") (pinfunction "DQ31_E2") (pintype "bidirectional"))
    )
    (net (code "77") (name "/FMC_NBL0 {slash} PE0") (class "Default")
      (node (ref "U2") (pin "C4") (pinfunction "PE0/LPTIM1_ETR/TIM4_ETR/HRTIM_SCIN/LPTIM2_ETR/UART8_RX/FDCAN1_RXFD_MODE/SAI2_MCLK_A/FMC_NBL0/DCMI_D2/EVENTOUT_C4") (pintype "bidirectional"))
      (node (ref "U3") (pin "K9") (pinfunction "DQM0_K9") (pintype "bidirectional"))
    )
    (net (code "78") (name "/FMC_NBL1 {slash} PE1") (class "Default")
      (node (ref "U2") (pin "B4") (pinfunction "PE1/LPTIM1_IN2/HRTIM_SCOUT/UART8_TX/FDCAN1_TXFD_MODE/FMC_NBL1/DCMI_D3/EVENTOUT_B4") (pintype "bidirectional"))
      (node (ref "U3") (pin "K1") (pinfunction "DQM1_K1") (pintype "bidirectional"))
    )
    (net (code "79") (name "/FMC_NBL2 {slash} PI4") (class "Default")
      (node (ref "U2") (pin "A4") (pinfunction "PI4/TIM8_BKIN/SAI2_MCLK_A/TIM8_BKIN_COMP12/FMC_NBL2/DCMI_D5/LCD_B4/EVENTOUT_A4") (pintype "bidirectional"))
      (node (ref "U3") (pin "F8") (pinfunction "DQM2_F8") (pintype "bidirectional"))
    )
    (net (code "80") (name "/FMC_NBL3 {slash} PI5") (class "Default")
      (node (ref "U2") (pin "A3") (pinfunction "PI5/TIM8_CH1/SAI2_SCK_A/FMC_NBL3/DCMI_VSYNC/LCD_B5/EVENTOUT_A3") (pintype "bidirectional"))
      (node (ref "U3") (pin "F2") (pinfunction "DQM3_F2") (pintype "bidirectional"))
    )
    (net (code "81") (name "/FMC_SDCKE0 {slash} PH2") (class "Default")
      (node (ref "U2") (pin "N2") (pinfunction "PH2/LPTIM1_IN2/QUADSPI_BK2_IO0/SAI2_SCK_B/ETH_MII_CRS/FMC_SDCKE0/LCD_R0/EVENTOUT_N2") (pintype "bidirectional"))
      (node (ref "U3") (pin "J2") (pinfunction "CKE_J2") (pintype "input"))
    )
    (net (code "82") (name "/FMC_SDCLK {slash} PG8") (class "Default")
      (node (ref "U2") (pin "F15") (pinfunction "PG8/TIM8_ETR/SPI6_NSS/USART6_RTS/USART6_DE/SPDIFRX1_IN3/ETH_PPS_OUT/FMC_SDCLK/LCD_G7/EVENTOUT_F15") (pintype "bidirectional"))
      (node (ref "U3") (pin "J1") (pinfunction "CLK_J1") (pintype "input"))
    )
    (net (code "83") (name "/FMC_SDNCAS {slash} PG15") (class "Default")
      (node (ref "U2") (pin "D6") (pinfunction "PG15/USART6_CTS/USART6_NSS/FMC_SDNCAS/DCMI_D13/EVENTOUT_D6") (pintype "bidirectional"))
      (node (ref "U3") (pin "K7") (pinfunction "CAS#_K7") (pintype "input"))
    )
    (net (code "84") (name "/FMC_SDNE0 {slash} PH3") (class "Default")
      (node (ref "U2") (pin "P2") (pinfunction "PH3/QUADSPI_BK2_IO1/SAI2_MCLK_B/ETH_MII_COL/FMC_SDNE0/LCD_R1/EVENTOUT_P2") (pintype "bidirectional"))
      (node (ref "U3") (pin "J8") (pinfunction "CS#_J8") (pintype "input"))
    )
    (net (code "85") (name "/FMC_SDNRAS {slash} PF11") (class "Default")
      (node (ref "U2") (pin "T7") (pinfunction "PF11/SPI5_MOSI/SAI2_SD_B/FMC_SDNRAS/DCMI_D12/EVENTOUT_T7") (pintype "bidirectional"))
      (node (ref "U3") (pin "J9") (pinfunction "RAS#_J9") (pintype "input"))
    )
    (net (code "86") (name "/FMC_SDNWE {slash} PC0") (class "Default")
      (node (ref "U2") (pin "L2") (pinfunction "PC0/DFSDM1_CKIN0/DFSDM1_DATIN4/SAI2_FS_B/OTG_HS_ULPI_STP/FMC_SDNWE/LCD_R5/EVENTOUT_L2") (pintype "bidirectional"))
      (node (ref "U3") (pin "K8") (pinfunction "WE#_K8") (pintype "input"))
    )
    (net (code "87") (name "/IIC2_SCL {slash} PH4") (class "Default")
      (node (ref "R36") (pin "1") (pinfunction "1_1") (pintype "passive"))
      (node (ref "U2") (pin "P3") (pinfunction "PH4/I2C2_SCL/LCD_G5/OTG_HS_ULPI_NXT/LCD_G4/EVENTOUT_P3") (pintype "bidirectional"))
    )
    (net (code "88") (name "/IIC2_SDA {slash} PH5") (class "Default")
      (node (ref "R37") (pin "1") (pinfunction "1_1") (pintype "passive"))
      (node (ref "U2") (pin "P4") (pinfunction "PH5/I2C2_SDA/SPI5_NSS/FMC_SDNWE/EVENTOUT_P4") (pintype "bidirectional"))
    )
    (net (code "89") (name "/IIC_SCLK {slash} PG2") (class "Default")
      (node (ref "R33") (pin "2") (pinfunction "2_2") (pintype "passive"))
      (node (ref "U2") (pin "H16") (pinfunction "PG2/TIM8_BKIN/TIM8_BKIN_COMP12/FMC_A12/EVENTOUT_H16") (pintype "bidirectional"))
    )
    (net (code "90") (name "/IIC_SDA {slash} PG3") (class "Default")
      (node (ref "R34") (pin "2") (pinfunction "2_2") (pintype "passive"))
      (node (ref "U2") (pin "H15") (pinfunction "PG3/TIM8_BKIN2/TIM8_BKIN2_COMP12/FMC_A13/EVENTOUT_H15") (pintype "bidirectional"))
    )
    (net (code "91") (name "/L3.3V") (class "Default")
      (node (ref "10") (pin "2") (pinfunction "2_2") (pintype "passive"))
      (node (ref "20") (pin "2") (pinfunction "2_2") (pintype "passive"))
      (node (ref "23") (pin "2") (pinfunction "2_2") (pintype "passive"))
      (node (ref "9") (pin "2") (pinfunction "2_2") (pintype "passive"))
      (node (ref "FB5") (pin "2") (pinfunction "2_2") (pintype "passive"))
      (node (ref "FPC1") (pin "4") (pinfunction "4_4") (pintype "passive"))
      (node (ref "JP3") (pin "2") (pinfunction "2_2") (pintype "passive"))
      (node (ref "R44") (pin "1") (pinfunction "1_1") (pintype "passive"))
    )
    (net (code "92") (name "/LCD_B0 {slash} PJ12") (class "Default")
      (node (ref "RP5") (pin "1") (pintype "passive"))
      (node (ref "U2") (pin "D11") (pinfunction "PJ12/TRGOUT/LCD_G3/LCD_B0/EVENTOUT_D11") (pintype "bidirectional"))
    )
    (net (code "93") (name "/LCD_B1 {slash} PJ13") (class "Default")
      (node (ref "RP5") (pin "2") (pintype "passive"))
      (node (ref "U2") (pin "E10") (pinfunction "PJ13/LCD_B4/LCD_B1/EVENTOUT_E10") (pintype "bidirectional"))
    )
    (net (code "94") (name "/LCD_B2 {slash} PJ14") (class "Default")
      (node (ref "RP5") (pin "3") (pintype "passive"))
      (node (ref "U2") (pin "D10") (pinfunction "PJ14/LCD_B2/EVENTOUT_D10") (pintype "bidirectional"))
    )
    (net (code "95") (name "/LCD_B3 {slash} PJ15") (class "Default")
      (node (ref "RP5") (pin "4") (pintype "passive"))
      (node (ref "U2") (pin "B10") (pinfunction "PJ15/LCD_B3/EVENTOUT_B10") (pintype "bidirectional"))
    )
    (net (code "96") (name "/LCD_B4 {slash} PK3") (class "Default")
      (node (ref "RP6") (pin "1") (pintype "passive"))
      (node (ref "U2") (pin "C8") (pinfunction "PK3/LCD_B4/EVENTOUT_C8") (pintype "bidirectional"))
    )
    (net (code "97") (name "/LCD_B5 {slash} PK4") (class "Default")
      (node (ref "RP6") (pin "2") (pintype "passive"))
      (node (ref "U2") (pin "B8") (pinfunction "PK4/LCD_B5/EVENTOUT_B8") (pintype "bidirectional"))
    )
    (net (code "98") (name "/LCD_B6 {slash} PK5") (class "Default")
      (node (ref "RP6") (pin "3") (pintype "passive"))
      (node (ref "U2") (pin "A8") (pinfunction "PK5/LCD_B6/EVENTOUT_A8") (pintype "bidirectional"))
    )
    (net (code "99") (name "/LCD_B7 {slash} PK6") (class "Default")
      (node (ref "RP6") (pin "4") (pintype "passive"))
      (node (ref "U2") (pin "C7") (pinfunction "PK6/LCD_B7/EVENTOUT_C7") (pintype "bidirectional"))
    )
    (net (code "100") (name "/LCD_BL {slash} PH6") (class "Default")
      (node (ref "R21") (pin "2") (pinfunction "2_2") (pintype "passive"))
      (node (ref "U2") (pin "T11") (pinfunction "PH6/TIM12_CH1/I2C2_SMBA/SPI5_SCK/ETH_MII_RXD2/FMC_SDNE1/DCMI_D8/EVENTOUT_T11") (pintype "bidirectional"))
    )
    (net (code "101") (name "/LCD_CLK {slash} PI14") (class "Default")
      (node (ref "RP7") (pin "1") (pintype "passive"))
      (node (ref "U2") (pin "H3") (pinfunction "PI14/LCD_CLK/EVENTOUT_H3") (pintype "bidirectional"))
    )
    (net (code "102") (name "/LCD_DE {slash} PK7") (class "Default")
      (node (ref "RP7") (pin "4") (pintype "passive"))
      (node (ref "U2") (pin "D7") (pinfunction "PK7/LCD_DE/EVENTOUT_D7") (pintype "bidirectional"))
    )
    (net (code "103") (name "/LCD_G0 {slash} PJ7") (class "Default")
      (node (ref "RP3") (pin "1") (pintype "passive"))
      (node (ref "U2") (pin "N14") (pinfunction "PJ7/TRGIN/TIM8_CH2N/LCD_G0/EVENTOUT_N14") (pintype "bidirectional"))
    )
    (net (code "104") (name "/LCD_G1 {slash} PJ8") (class "Default")
      (node (ref "RP3") (pin "2") (pintype "passive"))
      (node (ref "U2") (pin "N13") (pinfunction "PJ8/TIM1_CH3N/TIM8_CH1/UART8_TX/LCD_G1/EVENTOUT_N13") (pintype "bidirectional"))
    )
    (net (code "105") (name "/LCD_G2 {slash} PJ9") (class "Default")
      (node (ref "RP3") (pin "3") (pintype "passive"))
      (node (ref "U2") (pin "M14") (pinfunction "PJ9/TIM1_CH3/TIM8_CH1N/UART8_RX/LCD_G2/EVENTOUT_M14") (pintype "bidirectional"))
    )
    (net (code "106") (name "/LCD_G3 {slash} PJ10") (class "Default")
      (node (ref "RP3") (pin "4") (pintype "passive"))
      (node (ref "U2") (pin "L14") (pinfunction "PJ10/TIM1_CH2N/TIM8_CH2/SPI5_MOSI/LCD_G3/EVENTOUT_L14") (pintype "bidirectional"))
    )
    (net (code "107") (name "/LCD_G4 {slash} PJ11") (class "Default")
      (node (ref "RP4") (pin "1") (pintype "passive"))
      (node (ref "U2") (pin "K14") (pinfunction "PJ11/TIM1_CH2/TIM8_CH2N/SPI5_MISO/LCD_G4/EVENTOUT_K14") (pintype "bidirectional"))
    )
    (net (code "108") (name "/LCD_G5 {slash} PK0") (class "Default")
      (node (ref "RP4") (pin "2") (pintype "passive"))
      (node (ref "U2") (pin "J14") (pinfunction "PK0/TIM1_CH1N/TIM8_CH3/SPI5_SCK/LCD_G5/EVENTOUT_J14") (pintype "bidirectional"))
    )
    (net (code "109") (name "/LCD_G6 {slash} PK1") (class "Default")
      (node (ref "RP4") (pin "3") (pintype "passive"))
      (node (ref "U2") (pin "J15") (pinfunction "PK1/TIM1_CH1/TIM8_CH3N/SPI5_NSS/LCD_G6/EVENTOUT_J15") (pintype "bidirectional"))
    )
    (net (code "110") (name "/LCD_G7 {slash} PK2") (class "Default")
      (node (ref "RP4") (pin "4") (pintype "passive"))
      (node (ref "U2") (pin "H17") (pinfunction "PK2/TIM1_BKIN/TIM8_BKIN/TIM8_BKIN_COMP12/TIM1_BKIN_COMP12/LCD_G7/EVENTOUT_H17") (pintype "bidirectional"))
    )
    (net (code "111") (name "/LCD_HS {slash} PI12") (class "Default")
      (node (ref "RP7") (pin "2") (pintype "passive"))
      (node (ref "U2") (pin "H1") (pinfunction "PI12/LCD_HSYNC/EVENTOUT_H1") (pintype "bidirectional"))
    )
    (net (code "112") (name "/LCD_R0 {slash} PI15") (class "Default")
      (node (ref "RP1") (pin "1") (pintype "passive"))
      (node (ref "U2") (pin "P5") (pinfunction "PI15/LCD_G2/LCD_R0/EVENTOUT_P5") (pintype "bidirectional"))
    )
    (net (code "113") (name "/LCD_R1 {slash} PJ0") (class "Default")
      (node (ref "RP1") (pin "2") (pintype "passive"))
      (node (ref "U2") (pin "N6") (pinfunction "PJ0/LCD_R7/LCD_R1/EVENTOUT_N6") (pintype "bidirectional"))
    )
    (net (code "114") (name "/LCD_R2 {slash} PJ1") (class "Default")
      (node (ref "RP1") (pin "3") (pintype "passive"))
      (node (ref "U2") (pin "P6") (pinfunction "PJ1/LCD_R2/EVENTOUT_P6") (pintype "bidirectional"))
    )
    (net (code "115") (name "/LCD_R3 {slash} PJ2") (class "Default")
      (node (ref "RP1") (pin "4") (pintype "passive"))
      (node (ref "U2") (pin "T6") (pinfunction "PJ2/LCD_R3/EVENTOUT_T6") (pintype "bidirectional"))
    )
    (net (code "116") (name "/LCD_R4 {slash} PJ3") (class "Default")
      (node (ref "RP2") (pin "1") (pintype "passive"))
      (node (ref "U2") (pin "U6") (pinfunction "PJ3/LCD_R4/EVENTOUT_U6") (pintype "bidirectional"))
    )
    (net (code "117") (name "/LCD_R5 {slash} PJ4") (class "Default")
      (node (ref "RP2") (pin "2") (pintype "passive"))
      (node (ref "U2") (pin "U7") (pinfunction "PJ4/LCD_R5/EVENTOUT_U7") (pintype "bidirectional"))
    )
    (net (code "118") (name "/LCD_R6 {slash} PJ5") (class "Default")
      (node (ref "RP2") (pin "3") (pintype "passive"))
      (node (ref "U2") (pin "R12") (pinfunction "PJ5/LCD_R6/EVENTOUT_R12") (pintype "bidirectional"))
    )
    (net (code "119") (name "/LCD_R7 {slash} PJ6") (class "Default")
      (node (ref "RP2") (pin "4") (pintype "passive"))
      (node (ref "U2") (pin "N15") (pinfunction "PJ6/TIM8_CH2/LCD_R7/EVENTOUT_N15") (pintype "bidirectional"))
    )
    (net (code "120") (name "/LCD_VS {slash} PI13") (class "Default")
      (node (ref "RP7") (pin "3") (pintype "passive"))
      (node (ref "U2") (pin "H2") (pinfunction "PI13/LCD_VSYNC/EVENTOUT_H2") (pintype "bidirectional"))
    )
    (net (code "121") (name "/LED {slash} PC13") (class "Default")
      (node (ref "LED5") (pin "2") (pinfunction "K_2") (pintype "passive"))
      (node (ref "U2") (pin "E3") (pinfunction "PC13/EVENTOUT_E3") (pintype "bidirectional"))
    )
    (net (code "122") (name "/LED+") (class "Default")
      (node (ref "7") (pin "2") (pinfunction "2_2") (pintype "passive"))
      (node (ref "D1") (pin "2") (pinfunction "K_2") (pintype "passive"))
      (node (ref "FPC1") (pin "1") (pinfunction "1_1") (pintype "passive"))
    )
    (net (code "123") (name "/LED-") (class "Default")
      (node (ref "FPC1") (pin "2") (pinfunction "2_2") (pintype "passive"))
      (node (ref "R20") (pin "1") (pinfunction "1_1") (pintype "passive"))
      (node (ref "R24") (pin "1") (pinfunction "1_1") (pintype "passive"))
    )
    (net (code "124") (name "/OS_25M_IN") (class "Default")
      (node (ref "C49") (pin "2") (pinfunction "2_2") (pintype "passive"))
      (node (ref "U2") (pin "J2") (pinfunction "PH0-OSC_IN(PH0)/EVENTOUT_J2") (pintype "bidirectional"))
      (node (ref "X2") (pin "3") (pinfunction "3_3") (pintype "passive"))
    )
    (net (code "125") (name "/OS_25M_OUT") (class "Default")
      (node (ref "C48") (pin "2") (pinfunction "2_2") (pintype "passive"))
      (node (ref "U2") (pin "J1") (pinfunction "PH1-OSC_OUT(PH1)/EVENTOUT_J1") (pintype "bidirectional"))
      (node (ref "X2") (pin "1") (pinfunction "1_1") (pintype "passive"))
    )
    (net (code "126") (name "/OS_32K_IN") (class "Default")
      (node (ref "C50") (pin "1") (pinfunction "1_1") (pintype "passive"))
      (node (ref "U2") (pin "C2") (pinfunction "PC14-OSC32_IN/EVENTOUT_C2") (pintype "bidirectional"))
      (node (ref "X3") (pin "2") (pinfunction "2_2") (pintype "passive"))
    )
    (net (code "127") (name "/OS_32K_OUT") (class "Default")
      (node (ref "C51") (pin "1") (pinfunction "1_1") (pintype "passive"))
      (node (ref "U2") (pin "C1") (pinfunction "PC15-OSC32_OUT/EVENTOUT_C1") (pintype "bidirectional"))
      (node (ref "X3") (pin "1") (pinfunction "1_1") (pintype "passive"))
    )
    (net (code "128") (name "/PA9") (class "Default")
      (node (ref "JP1") (pin "8") (pinfunction "8_8") (pintype "passive"))
      (node (ref "R51") (pin "2") (pinfunction "2_2") (pintype "passive"))
      (node (ref "U2") (pin "D15") (pinfunction "PA9/TIM1_CH2/HRTIM_CHC1/LPUART1_TX/I2C3_SMBA/SPI2_SCK/I2S2_CK/USART1_TX/FDCAN1_RXFD_MODE/DCMI_D0/LCD_R5/EVENTOUT_D15") (pintype "bidirectional"))
    )
    (net (code "129") (name "/PA10") (class "Default")
      (node (ref "JP1") (pin "6") (pinfunction "6_6") (pintype "passive"))
      (node (ref "R50") (pin "2") (pinfunction "2_2") (pintype "passive"))
      (node (ref "U2") (pin "D14") (pinfunction "PA10/TIM1_CH3/HRTIM_CHC2/LPUART1_RX/USART1_RX/FDCAN1_TXFD_MODE/OTG_FS_ID/MDIOS_MDIO/LCD_B4/DCMI_D1/LCD_B1/EVENTOUT_D14") (pintype "bidirectional"))
    )
    (net (code "130") (name "/PA11") (class "Default")
      (node (ref "U2") (pin "E17") (pinfunction "PA11/TIM1_CH4/HRTIM_CHD1/LPUART1_CTS/SPI2_NSS/I2S2_WS/UART4_RX/USART1_CTS/USART1_NSS/FDCAN1_RX/OTG_FS_DM/LCD_R4/EVENTOUT_E17") (pintype "bidirectional"))
      (node (ref "U5") (pin "A7") (pinfunction "DN1_A7") (pintype "passive"))
      (node (ref "U5") (pin "B7") (pinfunction "DN2_B7") (pintype "passive"))
    )
    (net (code "131") (name "/PA12") (class "Default")
      (node (ref "U2") (pin "E16") (pinfunction "PA12/TIM1_ETR/HRTIM_CHD2/LPUART1_RTS/LPUART1_DE/SPI2_SCK/I2S2_CK/UART4_TX/USART1_RTS/USART1_DE/SAI2_FS_B/FDCAN1_TX/OTG_FS_DP/LCD_R5/EVENTOUT_E16") (pintype "bidirectional"))
      (node (ref "U5") (pin "A6") (pinfunction "DP1_A6") (pintype "passive"))
      (node (ref "U5") (pin "B6") (pinfunction "DP2_B6") (pintype "passive"))
    )
    (net (code "132") (name "/PB13") (class "Default")
      (node (ref "R47") (pin "2") (pinfunction "2_2") (pintype "passive"))
      (node (ref "SW3") (pin "2") (pinfunction "2_2") (pintype "passive"))
      (node (ref "U2") (pin "U14") (pinfunction "PB13/TIM1_CH1N/LPTIM2_OUT/SPI2_SCK/I2S2_CK/DFSDM1_CKIN1/USART3_CTS/USART3_NSS/FDCAN2_TX/OTG_HS_ULPI_D6/ETH_MII_TXD1/ETH_RMII_TXD1/UART5_TX/EVENTOUT_U14") (pintype "bidirectional"))
    )
    (net (code "133") (name "/PC8") (class "Default")
      (node (ref "P2") (pin "7") (pinfunction "DATA_0_7") (pintype "passive"))
      (node (ref "R12") (pin "2") (pinfunction "2_2") (pintype "passive"))
      (node (ref "U2") (pin "E13") (pinfunction "PC8/TRACED1/HRTIM_CHB1/TIM3_CH3/TIM8_CH3/USART6_CK/UART5_RTS/UART5_DE/FMC_NE2/FMC_NCE/SWPMI_RX/SDMMC1_D0/DCMI_D2/EVENTOUT_E13") (pintype "bidirectional"))
    )
    (net (code "134") (name "/PC9") (class "Default")
      (node (ref "P2") (pin "8") (pinfunction "DATA_1_8") (pintype "passive"))
      (node (ref "R11") (pin "2") (pinfunction "2_2") (pintype "passive"))
      (node (ref "U2") (pin "E14") (pinfunction "PC9/MCO2/TIM3_CH4/TIM8_CH4/I2C3_SDA/I2S_CKIN/UART5_CTS/QUADSPI_BK1_IO0/LCD_G3/SWPMI_SUSPEND/SDMMC1_D1/DCMI_D3/LCD_B2/EVENTOUT_E14") (pintype "bidirectional"))
    )
    (net (code "135") (name "/PC10") (class "Default")
      (node (ref "P2") (pin "1") (pinfunction "DATA_2_1") (pintype "passive"))
      (node (ref "R15") (pin "2") (pinfunction "2_2") (pintype "passive"))
      (node (ref "U2") (pin "A13") (pinfunction "PC10/HRTIM_EEV1/DFSDM1_CKIN5/SPI3_SCK/I2S3_CK/USART3_TX/UART4_TX/QUADSPI_BK1_IO1/SDMMC1_D2/DCMI_D8/LCD_R2/EVENTOUT_A13") (pintype "bidirectional"))
    )
    (net (code "136") (name "/PC11") (class "Default")
      (node (ref "P2") (pin "2") (pinfunction "DATA_3_2") (pintype "passive"))
      (node (ref "R14") (pin "2") (pinfunction "2_2") (pintype "passive"))
      (node (ref "U2") (pin "B13") (pinfunction "PC11/HRTIM_FLT2/DFSDM1_DATIN5/SPI3_MISO/I2S3_SDI/USART3_RX/UART4_RX/QUADSPI_BK2_NCS/SDMMC1_D3/DCMI_D4/EVENTOUT_B13") (pintype "bidirectional"))
    )
    (net (code "137") (name "/PC12") (class "Default")
      (node (ref "P2") (pin "5") (pinfunction "CLK_5") (pintype "passive"))
      (node (ref "U2") (pin "C12") (pinfunction "PC12/TRACED3/HRTIM_EEV2/SPI3_MOSI/I2S3_SDO/USART3_CK/UART5_TX/SDMMC1_CK/DCMI_D9/EVENTOUT_C12") (pintype "bidirectional"))
    )
    (net (code "138") (name "/PD2") (class "Default")
      (node (ref "P2") (pin "3") (pinfunction "CMD_3") (pintype "passive"))
      (node (ref "R13") (pin "2") (pinfunction "2_2") (pintype "passive"))
      (node (ref "U2") (pin "D12") (pinfunction "PD2/TRACED2/TIM3_ETR/UART5_RX/SDMMC1_CMD/DCMI_D11/EVENTOUT_D12") (pintype "bidirectional"))
    )
    (net (code "139") (name "/PI8") (class "Default")
      (node (ref "R38") (pin "1") (pinfunction "1_1") (pintype "passive"))
      (node (ref "U2") (pin "E4") (pinfunction "PI8/EVENTOUT_E4") (pintype "bidirectional"))
    )
    (net (code "140") (name "/PI11") (class "Default")
      (node (ref "R35") (pin "1") (pinfunction "1_1") (pintype "passive"))
      (node (ref "U2") (pin "F4") (pinfunction "PI11/LCD_G6/OTG_HS_ULPI_DIR/EVENTOUT_F4") (pintype "bidirectional"))
    )
    (net (code "141") (name "/QSPI_BK1_IO0 {slash} PF8") (class "Default")
      (node (ref "IC1") (pin "5") (pinfunction "DI_5") (pintype "passive"))
      (node (ref "U2") (pin "K4") (pinfunction "PF8/TIM16_CH1N/SPI5_MISO/SAI1_SCK_B/UART7_RTS/UART7_DE/SAI4_SCK_B/TIM13_CH1/QUADSPI_BK1_IO0/EVENTOUT_K4") (pintype "bidirectional"))
    )
    (net (code "142") (name "/QSPI_BK1_IO1 {slash} PF9") (class "Default")
      (node (ref "IC1") (pin "2") (pinfunction "DO_2") (pintype "passive"))
      (node (ref "U2") (pin "L4") (pinfunction "PF9/TIM17_CH1N/SPI5_MOSI/SAI1_FS_B/UART7_CTS/SAI4_FS_B/TIM14_CH1/QUADSPI_BK1_IO1/EVENTOUT_L4") (pintype "bidirectional"))
    )
    (net (code "143") (name "/QSPI_BK1_IO2 {slash} PF7") (class "Default")
      (node (ref "IC1") (pin "3") (pinfunction "~{WP}_3") (pintype "passive"))
      (node (ref "U2") (pin "K3") (pinfunction "PF7/TIM17_CH1/SPI5_SCK/SAI1_MCLK_B/UART7_TX/SAI4_MCLK_B/QUADSPI_BK1_IO2/EVENTOUT_K3") (pintype "bidirectional"))
    )
    (net (code "144") (name "/QSPI_BK1_IO3 {slash} PF6") (class "Default")
      (node (ref "IC1") (pin "7") (pinfunction "~{HOLD}_7") (pintype "passive"))
      (node (ref "U2") (pin "K2") (pinfunction "PF6/TIM16_CH1/SPI5_NSS/SAI1_SD_B/UART7_RX/SAI4_SD_B/QUADSPI_BK1_IO3/EVENTOUT_K2") (pintype "bidirectional"))
    )
    (net (code "145") (name "/QSPI_BK1_NCS {slash} PG6") (class "Default")
      (node (ref "IC1") (pin "1") (pinfunction "~{CS}_1") (pintype "passive"))
      (node (ref "U2") (pin "G15") (pinfunction "PG6/TIM17_BKIN/HRTIM_CHE1/QUADSPI_BK1_NCS/FMC_NE3/DCMI_D12/LCD_R7/EVENTOUT_G15") (pintype "bidirectional"))
    )
    (net (code "146") (name "/QSPI_CLK {slash} PF10") (class "Default")
      (node (ref "IC1") (pin "6") (pinfunction "CLK_6") (pintype "passive"))
      (node (ref "U2") (pin "L3") (pinfunction "PF10/TIM16_BKIN/SAI1_D3/QUADSPI_CLK/SAI4_D3/DCMI_D11/LCD_DE/EVENTOUT_L3") (pintype "bidirectional"))
    )
    (net (code "147") (name "/RST") (class "Default")
      (node (ref "C46") (pin "1") (pinfunction "1_1") (pintype "passive"))
      (node (ref "JP1") (pin "10") (pinfunction "10_10") (pintype "passive"))
      (node (ref "Q1") (pin "3") (pinfunction "C_3") (pintype "passive"))
      (node (ref "R16") (pin "1") (pinfunction "1_1") (pintype "passive"))
      (node (ref "R52") (pin "2") (pinfunction "2_2") (pintype "passive"))
      (node (ref "SW2") (pin "1") (pinfunction "1_1") (pintype "passive"))
      (node (ref "U2") (pin "K1") (pinfunction "NRST_K1") (pintype "bidirectional"))
    )
    (net (code "148") (name "/SWCLK {slash} PA14") (class "Default")
      (node (ref "JP1") (pin "4") (pinfunction "4_4") (pintype "passive"))
      (node (ref "R49") (pin "2") (pinfunction "2_2") (pintype "passive"))
      (node (ref "U2") (pin "B14") (pinfunction "PA14/JTCK-SWCLK/EVENTOUT_B14") (pintype "bidirectional"))
    )
    (net (code "149") (name "/SWDIO {slash} PA13") (class "Default")
      (node (ref "JP1") (pin "2") (pinfunction "2_2") (pintype "passive"))
      (node (ref "R48") (pin "2") (pinfunction "2_2") (pintype "passive"))
      (node (ref "U2") (pin "C15") (pinfunction "PA13/JTMS-SWDIO/EVENTOUT_C15") (pintype "bidirectional"))
    )
    (net (code "150") (name "/VBAT") (class "Default")
      (node (ref "C57") (pin "1") (pinfunction "1_1") (pintype "passive"))
      (node (ref "D4") (pin "3") (pinfunction "3_3") (pintype "passive"))
      (node (ref "U2") (pin "B1") (pinfunction "VBAT_B1") (pintype "power_in"))
    )
    (net (code "151") (name "/VBAT-EXT") (class "Default")
      (node (ref "D4") (pin "1") (pinfunction "1_1") (pintype "passive"))
      (node (ref "JP2") (pin "4") (pinfunction "4_4") (pintype "passive"))
    )
    (net (code "152") (name "/VDDA") (class "Default")
      (node (ref "C53") (pin "2") (pinfunction "2_2") (pintype "passive"))
      (node (ref "C54") (pin "2") (pinfunction "2_2") (pintype "passive"))
      (node (ref "FB4") (pin "2") (pinfunction "2_2") (pintype "passive"))
      (node (ref "R27") (pin "1") (pinfunction "1_1") (pintype "passive"))
      (node (ref "U2") (pin "L1") (pinfunction "VDDA_L1") (pintype "power_in"))
    )
    (net (code "153") (name "/VREF") (class "Default")
      (node (ref "C55") (pin "2") (pinfunction "2_2") (pintype "passive"))
      (node (ref "C56") (pin "2") (pinfunction "2_2") (pintype "passive"))
      (node (ref "JP2") (pin "2") (pinfunction "2_2") (pintype "passive"))
      (node (ref "R27") (pin "2") (pinfunction "2_2") (pintype "passive"))
      (node (ref "U2") (pin "M1") (pinfunction "VREF+_M1") (pintype "input"))
    )
    (net (code "154") (name "AF-2.8V") (class "Default")
      (node (ref "14") (pin "2") (pinfunction "2_2") (pintype "passive"))
      (node (ref "15") (pin "2") (pinfunction "2_2") (pintype "passive"))
      (node (ref "IC2") (pin "23") (pinfunction "AF-VCC_23") (pintype "passive"))
      (node (ref "U7") (pin "2") (pinfunction "VOUT_2") (pintype "passive"))
    )
    (net (code "155") (name "GND") (class "Default")
      (node (ref "1") (pin "1") (pinfunction "1_1") (pintype "passive"))
      (node (ref "10") (pin "1") (pinfunction "1_1") (pintype "passive"))
      (node (ref "11") (pin "1") (pinfunction "1_1") (pintype "passive"))
      (node (ref "12") (pin "1") (pinfunction "1_1") (pintype "passive"))
      (node (ref "13") (pin "1") (pinfunction "1_1") (pintype "passive"))
      (node (ref "14") (pin "1") (pinfunction "1_1") (pintype "passive"))
      (node (ref "15") (pin "1") (pinfunction "1_1") (pintype "passive"))
      (node (ref "16") (pin "1") (pinfunction "1_1") (pintype "passive"))
      (node (ref "17") (pin "1") (pinfunction "1_1") (pintype "passive"))
      (node (ref "18") (pin "1") (pinfunction "1_1") (pintype "passive"))
      (node (ref "19") (pin "1") (pinfunction "1_1") (pintype "passive"))
      (node (ref "2") (pin "1") (pinfunction "1_1") (pintype "passive"))
      (node (ref "20") (pin "1") (pinfunction "1_1") (pintype "passive"))
      (node (ref "21") (pin "1") (pinfunction "1_1") (pintype "passive"))
      (node (ref "22") (pin "1") (pinfunction "1_1") (pintype "passive"))
      (node (ref "23") (pin "1") (pinfunction "1_1") (pintype "passive"))
      (node (ref "24") (pin "1") (pinfunction "1_1") (pintype "passive"))
      (node (ref "25") (pin "1") (pinfunction "1_1") (pintype "passive"))
      (node (ref "26") (pin "1") (pinfunction "1_1") (pintype "passive"))
      (node (ref "27") (pin "1") (pinfunction "1_1") (pintype "passive"))
      (node (ref "28") (pin "1") (pinfunction "1_1") (pintype "passive"))
      (node (ref "29") (pin "1") (pinfunction "1_1") (pintype "passive"))
      (node (ref "3") (pin "1") (pinfunction "1_1") (pintype "passive"))
      (node (ref "4") (pin "1") (pinfunction "1_1") (pintype "passive"))
      (node (ref "5") (pin "1") (pinfunction "1_1") (pintype "passive"))
      (node (ref "6") (pin "1") (pinfunction "1_1") (pintype "passive"))
      (node (ref "7") (pin "1") (pinfunction "1_1") (pintype "passive"))
      (node (ref "9") (pin "1") (pinfunction "1_1") (pintype "passive"))
      (node (ref "C1") (pin "1") (pinfunction "1_1") (pintype "passive"))
      (node (ref "C10") (pin "1") (pinfunction "1_1") (pintype "passive"))
      (node (ref "C11") (pin "1") (pinfunction "1_1") (pintype "passive"))
      (node (ref "C12") (pin "1") (pinfunction "1_1") (pintype "passive"))
      (node (ref "C13") (pin "1") (pinfunction "1_1") (pintype "passive"))
      (node (ref "C14") (pin "1") (pinfunction "1_1") (pintype "passive"))
      (node (ref "C15") (pin "1") (pinfunction "1_1") (pintype "passive"))
      (node (ref "C16") (pin "1") (pinfunction "1_1") (pintype "passive"))
      (node (ref "C17") (pin "1") (pinfunction "1_1") (pintype "passive"))
      (node (ref "C18") (pin "1") (pinfunction "1_1") (pintype "passive"))
      (node (ref "C19") (pin "1") (pinfunction "1_1") (pintype "passive"))
      (node (ref "C2") (pin "1") (pinfunction "1_1") (pintype "passive"))
      (node (ref "C20") (pin "1") (pinfunction "1_1") (pintype "passive"))
      (node (ref "C21") (pin "1") (pinfunction "1_1") (pintype "passive"))
      (node (ref "C22") (pin "1") (pinfunction "1_1") (pintype "passive"))
      (node (ref "C23") (pin "1") (pinfunction "1_1") (pintype "passive"))
      (node (ref "C24") (pin "1") (pinfunction "1_1") (pintype "passive"))
      (node (ref "C25") (pin "1") (pinfunction "1_1") (pintype "passive"))
      (node (ref "C26") (pin "1") (pinfunction "1_1") (pintype "passive"))
      (node (ref "C27") (pin "1") (pinfunction "1_1") (pintype "passive"))
      (node (ref "C3") (pin "1") (pinfunction "1_1") (pintype "passive"))
      (node (ref "C35") (pin "1") (pinfunction "1_1") (pintype "passive"))
      (node (ref "C36") (pin "1") (pinfunction "1_1") (pintype "passive"))
      (node (ref "C37") (pin "1") (pinfunction "1_1") (pintype "passive"))
      (node (ref "C38") (pin "1") (pinfunction "1_1") (pintype "passive"))
      (node (ref "C39") (pin "1") (pinfunction "1_1") (pintype "passive"))
      (node (ref "C4") (pin "2") (pinfunction "2_2") (pintype "passive"))
      (node (ref "C40") (pin "1") (pinfunction "1_1") (pintype "passive"))
      (node (ref "C41") (pin "1") (pinfunction "1_1") (pintype "passive"))
      (node (ref "C42") (pin "1") (pinfunction "1_1") (pintype "passive"))
      (node (ref "C43") (pin "1") (pinfunction "1_1") (pintype "passive"))
      (node (ref "C44") (pin "1") (pinfunction "1_1") (pintype "passive"))
      (node (ref "C45") (pin "1") (pinfunction "1_1") (pintype "passive"))
      (node (ref "C46") (pin "2") (pinfunction "2_2") (pintype "passive"))
      (node (ref "C47") (pin "2") (pinfunction "2_2") (pintype "passive"))
      (node (ref "C48") (pin "1") (pinfunction "1_1") (pintype "passive"))
      (node (ref "C49") (pin "1") (pinfunction "1_1") (pintype "passive"))
      (node (ref "C5") (pin "2") (pinfunction "2_2") (pintype "passive"))
      (node (ref "C50") (pin "2") (pinfunction "2_2") (pintype "passive"))
      (node (ref "C51") (pin "2") (pinfunction "2_2") (pintype "passive"))
      (node (ref "C52") (pin "2") (pinfunction "2_2") (pintype "passive"))
      (node (ref "C53") (pin "1") (pinfunction "1_1") (pintype "passive"))
      (node (ref "C54") (pin "1") (pinfunction "1_1") (pintype "passive"))
      (node (ref "C55") (pin "1") (pinfunction "1_1") (pintype "passive"))
      (node (ref "C56") (pin "1") (pinfunction "1_1") (pintype "passive"))
      (node (ref "C57") (pin "2") (pinfunction "2_2") (pintype "passive"))
      (node (ref "C58") (pin "1") (pinfunction "1_1") (pintype "passive"))
      (node (ref "C6") (pin "2") (pinfunction "2_2") (pintype "passive"))
      (node (ref "C61") (pin "2") (pinfunction "2_2") (pintype "passive"))
      (node (ref "C7") (pin "2") (pinfunction "2_2") (pintype "passive"))
      (node (ref "C8") (pin "2") (pinfunction "2_2") (pintype "passive"))
      (node (ref "C9") (pin "1") (pinfunction "1_1") (pintype "passive"))
      (node (ref "D2") (pin "1") (pinfunction "A_1") (pintype "passive"))
      (node (ref "E1") (pin "2") (pinfunction "2_2") (pintype "passive"))
      (node (ref "E2") (pin "2") (pinfunction "2_2") (pintype "passive"))
      (node (ref "E3") (pin "2") (pinfunction "2_2") (pintype "passive"))
      (node (ref "FPC1") (pin "29") (pinfunction "29_29") (pintype "passive"))
      (node (ref "FPC1") (pin "3") (pinfunction "3_3") (pintype "passive"))
      (node (ref "FPC1") (pin "36") (pinfunction "36_36") (pintype "passive"))
      (node (ref "FPC1") (pin "41") (pinfunction "41_41") (pintype "passive"))
      (node (ref "FPC1") (pin "42") (pinfunction "42_42") (pintype "passive"))
      (node (ref "IC1") (pin "4") (pinfunction "GND_4") (pintype "passive"))
      (node (ref "IC2") (pin "1") (pinfunction "STROBE_1") (pintype "passive"))
      (node (ref "IC2") (pin "15") (pinfunction "DGND_15") (pintype "passive"))
      (node (ref "IC2") (pin "2") (pinfunction "AGND_2") (pintype "passive"))
      (node (ref "IC2") (pin "24") (pinfunction "AF-GND_24") (pintype "passive"))
      (node (ref "JP2") (pin "1") (pinfunction "1_1") (pintype "passive"))
      (node (ref "JP2") (pin "6") (pinfunction "6_6") (pintype "passive"))
      (node (ref "JP3") (pin "0") (pinfunction "0_0") (pintype "passive"))
      (node (ref "JP3") (pin "3") (pinfunction "3_3") (pintype "passive"))
      (node (ref "LED1") (pin "2") (pinfunction "K_2") (pintype "passive"))
      (node (ref "LED2") (pin "2") (pinfunction "K_2") (pintype "passive"))
      (node (ref "LED3") (pin "2") (pinfunction "K_2") (pintype "passive"))
      (node (ref "LED4") (pin "2") (pinfunction "K_2") (pintype "passive"))
      (node (ref "P2") (pin "6") (pinfunction "VSS_6") (pintype "passive"))
      (node (ref "Q1") (pin "2") (pinfunction "E_2") (pintype "passive"))
      (node (ref "R18") (pin "1") (pinfunction "1_1") (pintype "passive"))
      (node (ref "R19") (pin "1") (pinfunction "1_1") (pintype "passive"))
      (node (ref "R2") (pin "1") (pinfunction "1_1") (pintype "passive"))
      (node (ref "R23") (pin "2") (pinfunction "2_2") (pintype "passive"))
      (node (ref "R24") (pin "2") (pinfunction "2_2") (pintype "passive"))
      (node (ref "R25") (pin "1") (pinfunction "1_1") (pintype "passive"))
      (node (ref "R41") (pin "2") (pinfunction "2_2") (pintype "passive"))
      (node (ref "R46") (pin "2") (pinfunction "2_2") (pintype "passive"))
      (node (ref "R47") (pin "1") (pinfunction "1_1") (pintype "passive"))
      (node (ref "R5") (pin "1") (pinfunction "1_1") (pintype "passive"))
      (node (ref "SW2") (pin "2") (pinfunction "2_2") (pintype "passive"))
      (node (ref "U2") (pin "A1") (pinfunction "VSS_1_A1") (pintype "power_in"))
      (node (ref "U2") (pin "A17") (pinfunction "VSS_1_A17") (pintype "power_in"))
      (node (ref "U2") (pin "B2") (pinfunction "VSS_1_B2") (pintype "power_in"))
      (node (ref "U2") (pin "B6") (pinfunction "VSS_1_B6") (pintype "power_in"))
      (node (ref "U2") (pin "C10") (pinfunction "VSS_1_C10") (pintype "power_in"))
      (node (ref "U2") (pin "C13") (pinfunction "VSS_1_C13") (pintype "power_in"))
      (node (ref "U2") (pin "C16") (pinfunction "VSS_1_C16") (pintype "power_in"))
      (node (ref "U2") (pin "F2") (pinfunction "VSS_1_F2") (pintype "power_in"))
      (node (ref "U2") (pin "G10") (pinfunction "VSS_2_G10") (pintype "power_in"))
      (node (ref "U2") (pin "G11") (pinfunction "VSS_2_G11") (pintype "power_in"))
      (node (ref "U2") (pin "G16") (pinfunction "VSS_2_G16") (pintype "power_in"))
      (node (ref "U2") (pin "G7") (pinfunction "VSS_2_G7") (pintype "power_in"))
      (node (ref "U2") (pin "G8") (pinfunction "VSS_2_G8") (pintype "power_in"))
      (node (ref "U2") (pin "G9") (pinfunction "VSS_2_G9") (pintype "power_in"))
      (node (ref "U2") (pin "H10") (pinfunction "VSS_2_H10") (pintype "power_in"))
      (node (ref "U2") (pin "H11") (pinfunction "VSS_3_H11") (pintype "power_in"))
      (node (ref "U2") (pin "H7") (pinfunction "VSS_2_H7") (pintype "power_in"))
      (node (ref "U2") (pin "H8") (pinfunction "VSS_2_H8") (pintype "power_in"))
      (node (ref "U2") (pin "H9") (pinfunction "VSS_2_H9") (pintype "power_in"))
      (node (ref "U2") (pin "J10") (pinfunction "VSS_3_J10") (pintype "power_in"))
      (node (ref "U2") (pin "J11") (pinfunction "VSS_3_J11") (pintype "power_in"))
      (node (ref "U2") (pin "J16") (pinfunction "VSS_1_J16") (pintype "power_in"))
      (node (ref "U2") (pin "J17") (pinfunction "VSS_1_J17") (pintype "power_in"))
      (node (ref "U2") (pin "J3") (pinfunction "VSS_1_J3") (pintype "power_in"))
      (node (ref "U2") (pin "J7") (pinfunction "VSS_3_J7") (pintype "power_in"))
      (node (ref "U2") (pin "J8") (pinfunction "VSS_3_J8") (pintype "power_in"))
      (node (ref "U2") (pin "J9") (pinfunction "VSS_3_J9") (pintype "power_in"))
      (node (ref "U2") (pin "K10") (pinfunction "VSS_3_K10") (pintype "power_in"))
      (node (ref "U2") (pin "K11") (pinfunction "VSS_3_K11") (pintype "power_in"))
      (node (ref "U2") (pin "K15") (pinfunction "VSS_2_K15") (pintype "power_in"))
      (node (ref "U2") (pin "K7") (pinfunction "VSS_3_K7") (pintype "power_in"))
      (node (ref "U2") (pin "K8") (pinfunction "VSS_3_K8") (pintype "power_in"))
      (node (ref "U2") (pin "K9") (pinfunction "VSS_3_K9") (pintype "power_in"))
      (node (ref "U2") (pin "L10") (pinfunction "VSS_3_L10") (pintype "power_in"))
      (node (ref "U2") (pin "L11") (pinfunction "VSS_3_L11") (pintype "power_in"))
      (node (ref "U2") (pin "L15") (pinfunction "VSS_2_L15") (pintype "power_in"))
      (node (ref "U2") (pin "L7") (pinfunction "VSS_3_L7") (pintype "power_in"))
      (node (ref "U2") (pin "L8") (pinfunction "VSS_3_L8") (pintype "power_in"))
      (node (ref "U2") (pin "L9") (pinfunction "VSS_3_L9") (pintype "power_in"))
      (node (ref "U2") (pin "M15") (pinfunction "VSS_2_M15") (pintype "power_in"))
      (node (ref "U2") (pin "N1") (pinfunction "VREF-_N1") (pintype "input"))
      (node (ref "U2") (pin "N16") (pinfunction "VSS_1_N16") (pintype "power_in"))
      (node (ref "U2") (pin "P1") (pinfunction "VSSA_P1") (pintype "power_in"))
      (node (ref "U2") (pin "R4") (pinfunction "VSS_1_R4") (pintype "power_in"))
      (node (ref "U2") (pin "R8") (pinfunction "VSS_2_R8") (pintype "power_in"))
      (node (ref "U2") (pin "T12") (pinfunction "VSS_1_T12") (pintype "power_in"))
      (node (ref "U2") (pin "U1") (pinfunction "VSS_2_U1") (pintype "power_in"))
      (node (ref "U2") (pin "U17") (pinfunction "VSS_1_U17") (pintype "power_in"))
      (node (ref "U3") (pin "A3") (pinfunction "VSS_A3") (pintype "power_in"))
      (node (ref "U3") (pin "B3") (pinfunction "VSSQ_B3") (pintype "power_in"))
      (node (ref "U3") (pin "B8") (pinfunction "VSSQ_B8") (pintype "power_in"))
      (node (ref "U3") (pin "C1") (pinfunction "VSSQ_C1") (pintype "power_in"))
      (node (ref "U3") (pin "D1") (pinfunction "VSSQ_D1") (pintype "power_in"))
      (node (ref "U3") (pin "E9") (pinfunction "VSSQ_E9") (pintype "power_in"))
      (node (ref "U3") (pin "F1") (pinfunction "VSS_F1") (pintype "power_in"))
      (node (ref "U3") (pin "L3") (pinfunction "VSS_L3") (pintype "power_in"))
      (node (ref "U3") (pin "L9") (pinfunction "VSSQ_L9") (pintype "power_in"))
      (node (ref "U3") (pin "M1") (pinfunction "VSSQ_M1") (pintype "power_in"))
      (node (ref "U3") (pin "N1") (pinfunction "VSSQ_N1") (pintype "power_in"))
      (node (ref "U3") (pin "P3") (pinfunction "VSSQ_P3") (pintype "power_in"))
      (node (ref "U3") (pin "P8") (pinfunction "VSSQ_P8") (pintype "power_in"))
      (node (ref "U3") (pin "R3") (pinfunction "VSS_R3") (pintype "power_in"))
      (node (ref "U4") (pin "13") (pinfunction "13_13") (pintype "passive"))
      (node (ref "U4") (pin "14") (pinfunction "14_14") (pintype "passive"))
      (node (ref "U4") (pin "15") (pinfunction "15_15") (pintype "passive"))
      (node (ref "U4") (pin "16") (pinfunction "16_16") (pintype "passive"))
      (node (ref "U4") (pin "A1B12") (pinfunction "GND_A1B12") (pintype "passive"))
      (node (ref "U4") (pin "B1A12") (pinfunction "GND_B1A12") (pintype "passive"))
      (node (ref "U5") (pin "13") (pinfunction "13_13") (pintype "passive"))
      (node (ref "U5") (pin "14") (pinfunction "14_14") (pintype "passive"))
      (node (ref "U5") (pin "15") (pinfunction "15_15") (pintype "passive"))
      (node (ref "U5") (pin "16") (pinfunction "16_16") (pintype "passive"))
      (node (ref "U5") (pin "A1B12") (pinfunction "GND_A1B12") (pintype "passive"))
      (node (ref "U5") (pin "B1A12") (pinfunction "GND_B1A12") (pintype "passive"))
      (node (ref "U6") (pin "1") (pinfunction "VSS_1") (pintype "passive"))
      (node (ref "U7") (pin "1") (pinfunction "VSS_1") (pintype "passive"))
      (node (ref "U8") (pin "1") (pinfunction "VSS_1") (pintype "passive"))
      (node (ref "U9") (pin "21") (pinfunction "GND_21") (pintype "passive"))
      (node (ref "X2") (pin "2") (pinfunction "2_2") (pintype "passive"))
      (node (ref "X2") (pin "4") (pinfunction "4_4") (pintype "passive"))
      (node (ref "X4") (pin "2") (pinfunction "GND_2") (pintype "passive"))
    )
    (net (code "156") (name "Net-(8-FB)") (class "Default")
      (node (ref "8") (pin "3") (pinfunction "FB_3") (pintype "bidirectional"))
      (node (ref "R20") (pin "2") (pinfunction "2_2") (pintype "passive"))
    )
    (net (code "157") (name "Net-(8-GND)") (class "Default")
      (node (ref "8") (pin "2") (pinfunction "GND_2") (pintype "bidirectional"))
      (node (ref "R19") (pin "2") (pinfunction "2_2") (pintype "passive"))
    )
    (net (code "158") (name "Net-(8-SW)") (class "Default")
      (node (ref "8") (pin "1") (pinfunction "SW_1") (pintype "bidirectional"))
      (node (ref "D1") (pin "1") (pinfunction "A_1") (pintype "passive"))
      (node (ref "L1") (pin "1") (pinfunction "1_1") (pintype "passive"))
    )
    (net (code "159") (name "Net-(8-~{SHTDN!})") (class "Default")
      (node (ref "13") (pin "2") (pinfunction "2_2") (pintype "passive"))
      (node (ref "8") (pin "4") (pinfunction "~{SHTDN!}_4") (pintype "bidirectional"))
      (node (ref "R21") (pin "1") (pinfunction "1_1") (pintype "passive"))
      (node (ref "R23") (pin "1") (pinfunction "1_1") (pintype "passive"))
    )
    (net (code "160") (name "Net-(28-Pad2)") (class "Default")
      (node (ref "28") (pin "2") (pinfunction "2_2") (pintype "passive"))
      (node (ref "JP3") (pin "5") (pinfunction "5_5") (pintype "passive"))
      (node (ref "R36") (pin "2") (pinfunction "2_2") (pintype "passive"))
      (node (ref "R39") (pin "1") (pinfunction "1_1") (pintype "passive"))
    )
    (net (code "161") (name "Net-(29-Pad2)") (class "Default")
      (node (ref "29") (pin "2") (pinfunction "2_2") (pintype "passive"))
      (node (ref "JP3") (pin "6") (pinfunction "6_6") (pintype "passive"))
      (node (ref "R35") (pin "2") (pinfunction "2_2") (pintype "passive"))
      (node (ref "R42") (pin "1") (pinfunction "1_1") (pintype "passive"))
    )
    (net (code "162") (name "Net-(C1-Pad2)") (class "Default")
      (node (ref "C1") (pin "2") (pinfunction "2_2") (pintype "passive"))
      (node (ref "U2") (pin "A7") (pinfunction "VCAP_A7") (pintype "power_in"))
    )
    (net (code "163") (name "Net-(C2-Pad2)") (class "Default")
      (node (ref "C2") (pin "2") (pinfunction "2_2") (pintype "passive"))
      (node (ref "U2") (pin "D17") (pinfunction "VCAP_D17") (pintype "power_in"))
    )
    (net (code "164") (name "Net-(C3-Pad2)") (class "Default")
      (node (ref "C3") (pin "2") (pinfunction "2_2") (pintype "passive"))
      (node (ref "U2") (pin "U11") (pinfunction "VCAP_U11") (pintype "power_in"))
    )
    (net (code "165") (name "Net-(D3-A)") (class "Default")
      (node (ref "D3") (pin "1") (pinfunction "A_1") (pintype "passive"))
      (node (ref "R17") (pin "1") (pinfunction "1_1") (pintype "passive"))
      (node (ref "SW1") (pin "2") (pinfunction "2_2") (pintype "passive"))
    )
    (net (code "166") (name "Net-(D3-K)") (class "Default")
      (node (ref "C52") (pin "1") (pinfunction "1_1") (pintype "passive"))
      (node (ref "D3") (pin "2") (pinfunction "K_2") (pintype "passive"))
      (node (ref "Q2") (pin "1") (pinfunction "B_1") (pintype "passive"))
    )
    (net (code "167") (name "Net-(FPC1-Pad5)") (class "Default")
      (node (ref "FPC1") (pin "5") (pinfunction "5_5") (pintype "passive"))
      (node (ref "RP1") (pin "8") (pintype "passive"))
    )
    (net (code "168") (name "Net-(FPC1-Pad6)") (class "Default")
      (node (ref "FPC1") (pin "6") (pinfunction "6_6") (pintype "passive"))
      (node (ref "RP1") (pin "7") (pintype "passive"))
    )
    (net (code "169") (name "Net-(FPC1-Pad7)") (class "Default")
      (node (ref "FPC1") (pin "7") (pinfunction "7_7") (pintype "passive"))
      (node (ref "RP1") (pin "6") (pintype "passive"))
    )
    (net (code "170") (name "Net-(FPC1-Pad8)") (class "Default")
      (node (ref "FPC1") (pin "8") (pinfunction "8_8") (pintype "passive"))
      (node (ref "RP1") (pin "5") (pintype "passive"))
    )
    (net (code "171") (name "Net-(FPC1-Pad9)") (class "Default")
      (node (ref "FPC1") (pin "9") (pinfunction "9_9") (pintype "passive"))
      (node (ref "RP2") (pin "8") (pintype "passive"))
    )
    (net (code "172") (name "Net-(FPC1-Pad10)") (class "Default")
      (node (ref "FPC1") (pin "10") (pinfunction "10_10") (pintype "passive"))
      (node (ref "RP2") (pin "7") (pintype "passive"))
    )
    (net (code "173") (name "Net-(FPC1-Pad11)") (class "Default")
      (node (ref "FPC1") (pin "11") (pinfunction "11_11") (pintype "passive"))
      (node (ref "RP2") (pin "6") (pintype "passive"))
    )
    (net (code "174") (name "Net-(FPC1-Pad12)") (class "Default")
      (node (ref "FPC1") (pin "12") (pinfunction "12_12") (pintype "passive"))
      (node (ref "RP2") (pin "5") (pintype "passive"))
    )
    (net (code "175") (name "Net-(FPC1-Pad13)") (class "Default")
      (node (ref "FPC1") (pin "13") (pinfunction "13_13") (pintype "passive"))
      (node (ref "RP3") (pin "8") (pintype "passive"))
    )
    (net (code "176") (name "Net-(FPC1-Pad14)") (class "Default")
      (node (ref "FPC1") (pin "14") (pinfunction "14_14") (pintype "passive"))
      (node (ref "RP3") (pin "7") (pintype "passive"))
    )
    (net (code "177") (name "Net-(FPC1-Pad15)") (class "Default")
      (node (ref "FPC1") (pin "15") (pinfunction "15_15") (pintype "passive"))
      (node (ref "RP3") (pin "6") (pintype "passive"))
    )
    (net (code "178") (name "Net-(FPC1-Pad16)") (class "Default")
      (node (ref "FPC1") (pin "16") (pinfunction "16_16") (pintype "passive"))
      (node (ref "RP3") (pin "5") (pintype "passive"))
    )
    (net (code "179") (name "Net-(FPC1-Pad17)") (class "Default")
      (node (ref "FPC1") (pin "17") (pinfunction "17_17") (pintype "passive"))
      (node (ref "RP4") (pin "8") (pintype "passive"))
    )
    (net (code "180") (name "Net-(FPC1-Pad18)") (class "Default")
      (node (ref "FPC1") (pin "18") (pinfunction "18_18") (pintype "passive"))
      (node (ref "RP4") (pin "7") (pintype "passive"))
    )
    (net (code "181") (name "Net-(FPC1-Pad19)") (class "Default")
      (node (ref "FPC1") (pin "19") (pinfunction "19_19") (pintype "passive"))
      (node (ref "RP4") (pin "6") (pintype "passive"))
    )
    (net (code "182") (name "Net-(FPC1-Pad20)") (class "Default")
      (node (ref "FPC1") (pin "20") (pinfunction "20_20") (pintype "passive"))
      (node (ref "RP4") (pin "5") (pintype "passive"))
    )
    (net (code "183") (name "Net-(FPC1-Pad21)") (class "Default")
      (node (ref "FPC1") (pin "21") (pinfunction "21_21") (pintype "passive"))
      (node (ref "RP5") (pin "8") (pintype "passive"))
    )
    (net (code "184") (name "Net-(FPC1-Pad22)") (class "Default")
      (node (ref "FPC1") (pin "22") (pinfunction "22_22") (pintype "passive"))
      (node (ref "RP5") (pin "7") (pintype "passive"))
    )
    (net (code "185") (name "Net-(FPC1-Pad23)") (class "Default")
      (node (ref "FPC1") (pin "23") (pinfunction "23_23") (pintype "passive"))
      (node (ref "RP5") (pin "6") (pintype "passive"))
    )
    (net (code "186") (name "Net-(FPC1-Pad24)") (class "Default")
      (node (ref "FPC1") (pin "24") (pinfunction "24_24") (pintype "passive"))
      (node (ref "RP5") (pin "5") (pintype "passive"))
    )
    (net (code "187") (name "Net-(FPC1-Pad25)") (class "Default")
      (node (ref "FPC1") (pin "25") (pinfunction "25_25") (pintype "passive"))
      (node (ref "RP6") (pin "8") (pintype "passive"))
    )
    (net (code "188") (name "Net-(FPC1-Pad26)") (class "Default")
      (node (ref "FPC1") (pin "26") (pinfunction "26_26") (pintype "passive"))
      (node (ref "RP6") (pin "7") (pintype "passive"))
    )
    (net (code "189") (name "Net-(FPC1-Pad27)") (class "Default")
      (node (ref "FPC1") (pin "27") (pinfunction "27_27") (pintype "passive"))
      (node (ref "RP6") (pin "6") (pintype "passive"))
    )
    (net (code "190") (name "Net-(FPC1-Pad28)") (class "Default")
      (node (ref "FPC1") (pin "28") (pinfunction "28_28") (pintype "passive"))
      (node (ref "RP6") (pin "5") (pintype "passive"))
    )
    (net (code "191") (name "Net-(FPC1-Pad30)") (class "Default")
      (node (ref "FPC1") (pin "30") (pinfunction "30_30") (pintype "passive"))
      (node (ref "RP7") (pin "8") (pintype "passive"))
    )
    (net (code "192") (name "Net-(FPC1-Pad32)") (class "Default")
      (node (ref "FPC1") (pin "32") (pinfunction "32_32") (pintype "passive"))
      (node (ref "RP7") (pin "7") (pintype "passive"))
    )
    (net (code "193") (name "Net-(FPC1-Pad33)") (class "Default")
      (node (ref "FPC1") (pin "33") (pinfunction "33_33") (pintype "passive"))
      (node (ref "RP7") (pin "6") (pintype "passive"))
    )
    (net (code "194") (name "Net-(FPC1-Pad34)") (class "Default")
      (node (ref "FPC1") (pin "34") (pinfunction "34_34") (pintype "passive"))
      (node (ref "RP7") (pin "5") (pintype "passive"))
    )
    (net (code "195") (name "Net-(IC2-DOVDD)") (class "Default")
      (node (ref "21") (pin "2") (pinfunction "2_2") (pintype "passive"))
      (node (ref "22") (pin "2") (pinfunction "2_2") (pintype "passive"))
      (node (ref "FB6") (pin "2") (pinfunction "2_2") (pintype "passive"))
      (node (ref "IC2") (pin "11") (pinfunction "DOVDD_11") (pintype "passive"))
    )
    (net (code "196") (name "Net-(IC2-RESET)") (class "Default")
      (node (ref "24") (pin "2") (pinfunction "2_2") (pintype "passive"))
      (node (ref "IC2") (pin "6") (pinfunction "RESET_6") (pintype "passive"))
      (node (ref "R29") (pin "2") (pinfunction "2_2") (pintype "passive"))
    )
    (net (code "197") (name "Net-(IC2-SCL)") (class "Default")
      (node (ref "25") (pin "2") (pinfunction "2_2") (pintype "passive"))
      (node (ref "IC2") (pin "5") (pinfunction "SCL_5") (pintype "passive"))
      (node (ref "R31") (pin "1") (pinfunction "1_1") (pintype "passive"))
      (node (ref "R33") (pin "1") (pinfunction "1_1") (pintype "passive"))
    )
    (net (code "198") (name "Net-(IC2-SDA)") (class "Default")
      (node (ref "26") (pin "2") (pinfunction "2_2") (pintype "passive"))
      (node (ref "IC2") (pin "3") (pinfunction "SDA_3") (pintype "passive"))
      (node (ref "R32") (pin "1") (pinfunction "1_1") (pintype "passive"))
      (node (ref "R34") (pin "1") (pinfunction "1_1") (pintype "passive"))
    )
    (net (code "199") (name "Net-(IC2-XVCLK)") (class "Default")
      (node (ref "IC2") (pin "13") (pinfunction "XVCLK_13") (pintype "passive"))
      (node (ref "X4") (pin "3") (pinfunction "OUT_3") (pintype "passive"))
    )
    (net (code "200") (name "Net-(JP1-Pad1)") (class "Default")
      (node (ref "JP1") (pin "1") (pinfunction "1_1") (pintype "passive"))
      (node (ref "R48") (pin "1") (pinfunction "1_1") (pintype "passive"))
      (node (ref "R8") (pin "2") (pinfunction "2_2") (pintype "passive"))
    )
    (net (code "201") (name "Net-(JP1-Pad3)") (class "Default")
      (node (ref "JP1") (pin "3") (pinfunction "3_3") (pintype "passive"))
      (node (ref "R10") (pin "2") (pinfunction "2_2") (pintype "passive"))
      (node (ref "R49") (pin "1") (pinfunction "1_1") (pintype "passive"))
    )
    (net (code "202") (name "Net-(JP3-Pad1)") (class "Default")
      (node (ref "JP3") (pin "1") (pinfunction "1_1") (pintype "passive"))
      (node (ref "R38") (pin "2") (pinfunction "2_2") (pintype "passive"))
    )
    (net (code "203") (name "Net-(JP3-Pad4)") (class "Default")
      (node (ref "JP3") (pin "4") (pinfunction "4_4") (pintype "passive"))
      (node (ref "R37") (pin "2") (pinfunction "2_2") (pintype "passive"))
    )
    (net (code "204") (name "Net-(LED1-A)") (class "Default")
      (node (ref "LED1") (pin "1") (pinfunction "A_1") (pintype "passive"))
      (node (ref "R3") (pin "2") (pinfunction "2_2") (pintype "passive"))
    )
    (net (code "205") (name "Net-(LED2-A)") (class "Default")
      (node (ref "LED2") (pin "1") (pinfunction "A_1") (pintype "passive"))
      (node (ref "R6") (pin "2") (pinfunction "2_2") (pintype "passive"))
    )
    (net (code "206") (name "Net-(LED4-A)") (class "Default")
      (node (ref "LED4") (pin "1") (pinfunction "A_1") (pintype "passive"))
      (node (ref "R26") (pin "2") (pinfunction "2_2") (pintype "passive"))
    )
    (net (code "207") (name "Net-(LED5-A)") (class "Default")
      (node (ref "LED5") (pin "1") (pinfunction "A_1") (pintype "passive"))
      (node (ref "R28") (pin "2") (pinfunction "2_2") (pintype "passive"))
    )
    (net (code "208") (name "Net-(Q1-B)") (class "Default")
      (node (ref "C47") (pin "1") (pinfunction "1_1") (pintype "passive"))
      (node (ref "Q1") (pin "1") (pinfunction "B_1") (pintype "passive"))
      (node (ref "R17") (pin "2") (pinfunction "2_2") (pintype "passive"))
      (node (ref "R18") (pin "2") (pinfunction "2_2") (pintype "passive"))
    )
    (net (code "209") (name "Net-(Q2-C)") (class "Default")
      (node (ref "Q2") (pin "3") (pinfunction "C_3") (pintype "passive"))
      (node (ref "R22") (pin "1") (pinfunction "1_1") (pintype "passive"))
    )
    (net (code "210") (name "Net-(U1A-PD0-OSC_IN)") (class "Default")
      (node (ref "C4") (pin "1") (pinfunction "1_1") (pintype "passive"))
      (node (ref "U1") (pin "5") (pinfunction "PD0-OSC_IN_5") (pintype "bidirectional"))
      (node (ref "X1") (pin "1") (pinfunction "1_1") (pintype "passive"))
    )
    (net (code "211") (name "Net-(U1A-PD1)") (class "Default")
      (node (ref "C5") (pin "1") (pinfunction "1_1") (pintype "passive"))
      (node (ref "U1") (pin "6") (pinfunction "PD1_6") (pintype "bidirectional"))
      (node (ref "X1") (pin "2") (pinfunction "2_2") (pintype "passive"))
    )
    (net (code "212") (name "Net-(U1B-VSSA)") (class "Default")
      (node (ref "R2") (pin "2") (pinfunction "2_2") (pintype "passive"))
      (node (ref "U1") (pin "23") (pinfunction "VSS_1_23") (pintype "power_in"))
      (node (ref "U1") (pin "35") (pinfunction "VSS_2_35") (pintype "power_in"))
      (node (ref "U1") (pin "47") (pinfunction "VSS_3_47") (pintype "power_in"))
      (node (ref "U1") (pin "8") (pinfunction "VSSA_8") (pintype "power_in"))
    )
    (net (code "213") (name "Net-(U2A-PDR_ON)") (class "Default")
      (node (ref "R1") (pin "2") (pinfunction "2_2") (pintype "passive"))
      (node (ref "U2") (pin "E7") (pinfunction "PDR_ON_E7") (pintype "input"))
    )
    (net (code "214") (name "Net-(U6-VIN)") (class "Default")
      (node (ref "1") (pin "2") (pinfunction "2_2") (pintype "passive"))
      (node (ref "2") (pin "2") (pinfunction "2_2") (pintype "passive"))
      (node (ref "FB1") (pin "1") (pinfunction "1_1") (pintype "passive"))
      (node (ref "U6") (pin "3") (pinfunction "VIN_3") (pintype "passive"))
    )
    (net (code "215") (name "Net-(U7-VIN)") (class "Default")
      (node (ref "11") (pin "2") (pinfunction "2_2") (pintype "passive"))
      (node (ref "12") (pin "2") (pinfunction "2_2") (pintype "passive"))
      (node (ref "FB2") (pin "1") (pinfunction "1_1") (pintype "passive"))
      (node (ref "U7") (pin "3") (pinfunction "VIN_3") (pintype "passive"))
    )
    (net (code "216") (name "Net-(U8-VIN)") (class "Default")
      (node (ref "16") (pin "2") (pinfunction "2_2") (pintype "passive"))
      (node (ref "17") (pin "2") (pinfunction "2_2") (pintype "passive"))
      (node (ref "FB3") (pin "1") (pinfunction "1_1") (pintype "passive"))
      (node (ref "U8") (pin "3") (pinfunction "VIN_3") (pintype "passive"))
    )
    (net (code "217") (name "Net-(U9-FB2)") (class "Default")
      (node (ref "C60") (pin "1") (pinfunction "1_1") (pintype "passive"))
      (node (ref "R41") (pin "1") (pinfunction "1_1") (pintype "passive"))
      (node (ref "R45") (pin "2") (pinfunction "2_2") (pintype "passive"))
      (node (ref "U9") (pin "3") (pinfunction "FB2_3") (pintype "passive"))
    )
    (net (code "218") (name "Net-(U9-FB3)") (class "Default")
      (node (ref "C59") (pin "1") (pinfunction "1_1") (pintype "passive"))
      (node (ref "R43") (pin "2") (pinfunction "2_2") (pintype "passive"))
      (node (ref "R46") (pin "1") (pinfunction "1_1") (pintype "passive"))
      (node (ref "U9") (pin "2") (pinfunction "FB3_2") (pintype "passive"))
    )
    (net (code "219") (name "Net-(U9-SW2)") (class "Default")
      (node (ref "L3") (pin "2") (pinfunction "2_2") (pintype "passive"))
      (node (ref "U9") (pin "6") (pinfunction "SW2_6") (pintype "passive"))
    )
    (net (code "220") (name "Net-(U9-SW3)") (class "Default")
      (node (ref "L2") (pin "2") (pinfunction "2_2") (pintype "passive"))
      (node (ref "U9") (pin "20") (pinfunction "SW3_20") (pintype "passive"))
    )
    (net (code "221") (name "Net-(X4-EN{slash}NC)") (class "Default")
      (node (ref "R40") (pin "1") (pinfunction "1_1") (pintype "passive"))
      (node (ref "X4") (pin "1") (pinfunction "EN/NC_1") (pintype "passive"))
    )
    (net (code "222") (name "Net-(X4-VCC)") (class "Default")
      (node (ref "27") (pin "2") (pinfunction "2_2") (pintype "passive"))
      (node (ref "FB7") (pin "2") (pinfunction "2_2") (pintype "passive"))
      (node (ref "X4") (pin "4") (pinfunction "VCC_4") (pintype "passive"))
    )
    (net (code "223") (name "unconnected-(FPC1-Pad35)") (class "Default")
      (node (ref "FPC1") (pin "35") (pinfunction "35_35") (pintype "passive+no_connect"))
    )
    (net (code "224") (name "unconnected-(FPC1-Pad37)") (class "Default")
      (node (ref "FPC1") (pin "37") (pinfunction "37_37") (pintype "passive+no_connect"))
    )
    (net (code "225") (name "unconnected-(FPC1-Pad38)") (class "Default")
      (node (ref "FPC1") (pin "38") (pinfunction "38_38") (pintype "passive+no_connect"))
    )
    (net (code "226") (name "unconnected-(FPC1-Pad39)") (class "Default")
      (node (ref "FPC1") (pin "39") (pinfunction "39_39") (pintype "passive+no_connect"))
    )
    (net (code "227") (name "unconnected-(FPC1-Pad40)") (class "Default")
      (node (ref "FPC1") (pin "40") (pinfunction "40_40") (pintype "passive+no_connect"))
    )
    (net (code "228") (name "unconnected-(U1A-PA0-WKUP-Pad10)") (class "Default")
      (node (ref "U1") (pin "10") (pinfunction "PA0-WKUP_10") (pintype "bidirectional+no_connect"))
    )
    (net (code "229") (name "unconnected-(U1A-PA1-Pad11)") (class "Default")
      (node (ref "U1") (pin "11") (pinfunction "PA1_11") (pintype "bidirectional+no_connect"))
    )
    (net (code "230") (name "unconnected-(U1A-PA3-Pad13)") (class "Default")
      (node (ref "U1") (pin "13") (pinfunction "PA3_13") (pintype "bidirectional+no_connect"))
    )
    (net (code "231") (name "unconnected-(U1A-PA5-Pad15)") (class "Default")
      (node (ref "U1") (pin "15") (pinfunction "PA5_15") (pintype "bidirectional+no_connect"))
    )
    (net (code "232") (name "unconnected-(U1A-PA7-Pad17)") (class "Default")
      (node (ref "U1") (pin "17") (pinfunction "PA7_17") (pintype "bidirectional+no_connect"))
    )
    (net (code "233") (name "unconnected-(U1A-PA8-Pad29)") (class "Default")
      (node (ref "U1") (pin "29") (pinfunction "PA8_29") (pintype "bidirectional+no_connect"))
    )
    (net (code "234") (name "unconnected-(U1A-PA13-Pad34)") (class "Default")
      (node (ref "U1") (pin "34") (pinfunction "PA13_34") (pintype "bidirectional+no_connect"))
    )
    (net (code "235") (name "unconnected-(U1A-PA14-Pad37)") (class "Default")
      (node (ref "U1") (pin "37") (pinfunction "PA14_37") (pintype "bidirectional+no_connect"))
    )
    (net (code "236") (name "unconnected-(U1A-PA15-Pad38)") (class "Default")
      (node (ref "U1") (pin "38") (pinfunction "PA15_38") (pintype "bidirectional+no_connect"))
    )
    (net (code "237") (name "unconnected-(U1A-PB0-Pad18)") (class "Default")
      (node (ref "U1") (pin "18") (pinfunction "PB0_18") (pintype "bidirectional+no_connect"))
    )
    (net (code "238") (name "unconnected-(U1A-PB1-Pad19)") (class "Default")
      (node (ref "U1") (pin "19") (pinfunction "PB1_19") (pintype "bidirectional+no_connect"))
    )
    (net (code "239") (name "unconnected-(U1A-PB2-Pad20)") (class "Default")
      (node (ref "U1") (pin "20") (pinfunction "PB2_20") (pintype "bidirectional+no_connect"))
    )
    (net (code "240") (name "unconnected-(U1A-PB3-Pad39)") (class "Default")
      (node (ref "U1") (pin "39") (pinfunction "PB3_39") (pintype "bidirectional+no_connect"))
    )
    (net (code "241") (name "unconnected-(U1A-PB4-Pad40)") (class "Default")
      (node (ref "U1") (pin "40") (pinfunction "PB4_40") (pintype "bidirectional+no_connect"))
    )
    (net (code "242") (name "unconnected-(U1A-PB5-Pad41)") (class "Default")
      (node (ref "U1") (pin "41") (pinfunction "PB5_41") (pintype "bidirectional+no_connect"))
    )
    (net (code "243") (name "unconnected-(U1A-PB6-Pad42)") (class "Default")
      (node (ref "U1") (pin "42") (pinfunction "PB6_42") (pintype "bidirectional+no_connect"))
    )
    (net (code "244") (name "unconnected-(U1A-PB7-Pad43)") (class "Default")
      (node (ref "U1") (pin "43") (pinfunction "PB7_43") (pintype "bidirectional+no_connect"))
    )
    (net (code "245") (name "unconnected-(U1A-PB9-Pad46)") (class "Default")
      (node (ref "U1") (pin "46") (pinfunction "PB9_46") (pintype "bidirectional+no_connect"))
    )
    (net (code "246") (name "unconnected-(U1A-PB10-Pad21)") (class "Default")
      (node (ref "U1") (pin "21") (pinfunction "PB10_21") (pintype "bidirectional+no_connect"))
    )
    (net (code "247") (name "unconnected-(U1A-PB11-Pad22)") (class "Default")
      (node (ref "U1") (pin "22") (pinfunction "PB11_22") (pintype "bidirectional+no_connect"))
    )
    (net (code "248") (name "unconnected-(U1A-PB13-Pad26)") (class "Default")
      (node (ref "U1") (pin "26") (pinfunction "PB13_26") (pintype "bidirectional+no_connect"))
    )
    (net (code "249") (name "unconnected-(U1A-PB14-Pad27)") (class "Default")
      (node (ref "U1") (pin "27") (pinfunction "PB14_27") (pintype "bidirectional+no_connect"))
    )
    (net (code "250") (name "unconnected-(U1A-PB15-Pad28)") (class "Default")
      (node (ref "U1") (pin "28") (pinfunction "PB15_28") (pintype "bidirectional+no_connect"))
    )
    (net (code "251") (name "unconnected-(U1A-PC13-TAMPER-RTC-Pad2)") (class "Default")
      (node (ref "U1") (pin "2") (pinfunction "PC13-TAMPER-RTC_2") (pintype "bidirectional+no_connect"))
    )
    (net (code "252") (name "unconnected-(U1A-PC14-OSC32_IN-Pad3)") (class "Default")
      (node (ref "U1") (pin "3") (pinfunction "PC14-OSC32_IN_3") (pintype "bidirectional+no_connect"))
    )
    (net (code "253") (name "unconnected-(U1A-PC15-OSC32_OUT-Pad4)") (class "Default")
      (node (ref "U1") (pin "4") (pinfunction "PC15-OSC32_OUT_4") (pintype "bidirectional+no_connect"))
    )
    (net (code "254") (name "unconnected-(U2A-PA0_C{slash}TIM2_CH1{slash}TIM2_ETR{slash}TIM5_CH1{slash}TIM8_ETR{slash}TIM15_BKIN{slash}USART2_CTS{slash}USART2_NSS{slash}UART4_TX{slash}SDMMC2_CMD{slash}SAI2_SD_B{slash}ETH_MII_CRS{slash}EVENTOUT-PadT1)") (class "Default")
      (node (ref "U2") (pin "T1") (pinfunction "PA0_C/TIM2_CH1/TIM2_ETR/TIM5_CH1/TIM8_ETR/TIM15_BKIN/USART2_CTS/USART2_NSS/UART4_TX/SDMMC2_CMD/SAI2_SD_B/ETH_MII_CRS/EVENTOUT_T1") (pintype "bidirectional+no_connect"))
    )
    (net (code "255") (name "unconnected-(U2A-PA0{slash}TIM2_CH1{slash}TIM2_ETR{slash}TIM5_CH1{slash}TIM8_ETR{slash}TIM15_BKIN{slash}USART2_CTS{slash}USART2_NSS{slash}UART4_TX{slash}SDMMC2_CMD{slash}SAI2_SD_B{slash}ETH_MII_CRS{slash}EVENTOUT-PadN5)") (class "Default")
      (node (ref "U2") (pin "N5") (pinfunction "PA0/TIM2_CH1/TIM2_ETR/TIM5_CH1/TIM8_ETR/TIM15_BKIN/USART2_CTS/USART2_NSS/UART4_TX/SDMMC2_CMD/SAI2_SD_B/ETH_MII_CRS/EVENTOUT_N5") (pintype "bidirectional+no_connect"))
    )
    (net (code "256") (name "unconnected-(U2A-PA1_C{slash}TIM2_CH2{slash}TIM5_CH2{slash}LPTIM3_OUT{slash}TIM15_CH1N{slash}USART2_RTS{slash}USART2_DE{slash}UART4_RX{slash}QUADSPI_BK1_IO3{slash}SAI2_MCLK_B{slash}ETH_MII_RX_CLK{slash}ETH_RMII_REF_CLK{slash}LCD_R2{slash}EVENTOUT-PadT2)") (class "Default")
      (node (ref "U2") (pin "T2") (pinfunction "PA1_C/TIM2_CH2/TIM5_CH2/LPTIM3_OUT/TIM15_CH1N/USART2_RTS/USART2_DE/UART4_RX/QUADSPI_BK1_IO3/SAI2_MCLK_B/ETH_MII_RX_CLK/ETH_RMII_REF_CLK/LCD_R2/EVENTOUT_T2") (pintype "bidirectional+no_connect"))
    )
    (net (code "257") (name "unconnected-(U2A-PA1{slash}TIM2_CH2{slash}TIM5_CH2{slash}LPTIM3_OUT{slash}TIM15_CH1N{slash}USART2_RTS{slash}USART2_DE{slash}UART4_RX{slash}QUADSPI_BK1_IO3{slash}SAI2_MCLK_B{slash}ETH_MII_RX_CLK{slash}ETH_RMII_REF_CLK{slash}LCD_R2{slash}EVENTOUT-PadN4)") (class "Default")
      (node (ref "U2") (pin "N4") (pinfunction "PA1/TIM2_CH2/TIM5_CH2/LPTIM3_OUT/TIM15_CH1N/USART2_RTS/USART2_DE/UART4_RX/QUADSPI_BK1_IO3/SAI2_MCLK_B/ETH_MII_RX_CLK/ETH_RMII_REF_CLK/LCD_R2/EVENTOUT_N4") (pintype "bidirectional+no_connect"))
    )
    (net (code "258") (name "unconnected-(U2A-PA2{slash}TIM2_CH3{slash}TIM5_CH3{slash}LPTIM4_OUT{slash}TIM15_CH1{slash}USART2_TX{slash}SAI2_SCK_B{slash}ETH_MDIO{slash}MDIOS_MDIO{slash}LCD_R1{slash}EVENTOUT-PadN3)") (class "Default")
      (node (ref "U2") (pin "N3") (pinfunction "PA2/TIM2_CH3/TIM5_CH3/LPTIM4_OUT/TIM15_CH1/USART2_TX/SAI2_SCK_B/ETH_MDIO/MDIOS_MDIO/LCD_R1/EVENTOUT_N3") (pintype "bidirectional+no_connect"))
    )
    (net (code "259") (name "unconnected-(U2A-PA3{slash}TIM2_CH4{slash}TIM5_CH4{slash}LPTIM5_OUT{slash}TIM15_CH2{slash}USART2_RX{slash}LCD_B2{slash}OTG_HS_ULPI_D0{slash}ETH_MII_COL{slash}LCD_B5{slash}EVENTOUT-PadU2)") (class "Default")
      (node (ref "U2") (pin "U2") (pinfunction "PA3/TIM2_CH4/TIM5_CH4/LPTIM5_OUT/TIM15_CH2/USART2_RX/LCD_B2/OTG_HS_ULPI_D0/ETH_MII_COL/LCD_B5/EVENTOUT_U2") (pintype "bidirectional+no_connect"))
    )
    (net (code "260") (name "unconnected-(U2A-PA5{slash}D2PWREN{slash}TIM2_CH1{slash}TIM2_ETR{slash}TIM8_CH1N{slash}SPI1_SCK{slash}I2S1_CK{slash}SPI6_SCK{slash}OTG_HS_ULPI_CK{slash}LCD_R4{slash}EVENTOUT-PadT3)") (class "Default")
      (node (ref "U2") (pin "T3") (pinfunction "PA5/D2PWREN/TIM2_CH1/TIM2_ETR/TIM8_CH1N/SPI1_SCK/I2S1_CK/SPI6_SCK/OTG_HS_ULPI_CK/LCD_R4/EVENTOUT_T3") (pintype "bidirectional+no_connect"))
    )
    (net (code "261") (name "unconnected-(U2A-PA7{slash}TIM1_CH1N{slash}TIM3_CH2{slash}TIM8_CH1N{slash}SPI1_MOSI{slash}I2S1_SDO{slash}SPI6_MOSI{slash}TIM14_CH1{slash}ETH_MII_RX_DV{slash}ETH_RMII_CRS_DV{slash}FMC_SDNWE{slash}EVENTOUT-PadR5)") (class "Default")
      (node (ref "U2") (pin "R5") (pinfunction "PA7/TIM1_CH1N/TIM3_CH2/TIM8_CH1N/SPI1_MOSI/I2S1_SDO/SPI6_MOSI/TIM14_CH1/ETH_MII_RX_DV/ETH_RMII_CRS_DV/FMC_SDNWE/EVENTOUT_R5") (pintype "bidirectional+no_connect"))
    )
    (net (code "262") (name "unconnected-(U2A-PA8{slash}MCO1{slash}TIM1_CH1{slash}HRTIM_CHB2{slash}TIM8_BKIN2{slash}I2C3_SCL{slash}USART1_CK{slash}OTG_FS_SOF{slash}UART7_RX{slash}TIM8_BKIN2_COMP12{slash}LCD_B3{slash}LCD_R6{slash}EVENTOUT-PadE15)") (class "Default")
      (node (ref "U2") (pin "E15") (pinfunction "PA8/MCO1/TIM1_CH1/HRTIM_CHB2/TIM8_BKIN2/I2C3_SCL/USART1_CK/OTG_FS_SOF/UART7_RX/TIM8_BKIN2_COMP12/LCD_B3/LCD_R6/EVENTOUT_E15") (pintype "bidirectional+no_connect"))
    )
    (net (code "263") (name "unconnected-(U2A-PA15{slash}JTDI{slash}TIM2_CH1{slash}TIM2_ETR{slash}HRTIM_FLT1{slash}CEC{slash}SPI1_NSS{slash}I2S1_WS{slash}SPI3_NSS{slash}I2S3_WS{slash}SPI6_NSS{slash}UART4_RTS{slash}UART4_DE{slash}UART7_TX{slash}EVENTOUT-PadA14)") (class "Default")
      (node (ref "U2") (pin "A14") (pinfunction "PA15/JTDI/TIM2_CH1/TIM2_ETR/HRTIM_FLT1/CEC/SPI1_NSS/I2S1_WS/SPI3_NSS/I2S3_WS/SPI6_NSS/UART4_RTS/UART4_DE/UART7_TX/EVENTOUT_A14") (pintype "bidirectional+no_connect"))
    )
    (net (code "264") (name "unconnected-(U2A-PB0{slash}TIM1_CH2N{slash}TIM3_CH3{slash}TIM8_CH2N{slash}DFSDM1_CKOUT{slash}UART4_CTS{slash}LCD_R3{slash}OTG_HS_ULPI_D1{slash}ETH_MII_RXD2{slash}LCD_G1{slash}EVENTOUT-PadU5)") (class "Default")
      (node (ref "U2") (pin "U5") (pinfunction "PB0/TIM1_CH2N/TIM3_CH3/TIM8_CH2N/DFSDM1_CKOUT/UART4_CTS/LCD_R3/OTG_HS_ULPI_D1/ETH_MII_RXD2/LCD_G1/EVENTOUT_U5") (pintype "bidirectional+no_connect"))
    )
    (net (code "265") (name "unconnected-(U2A-PB1{slash}TIM1_CH3N{slash}TIM3_CH4{slash}TIM8_CH3N{slash}DFSDM1_DATIN1{slash}LCD_R6{slash}OTG_HS_ULPI_D2{slash}ETH_MII_RXD3{slash}LCD_G0{slash}EVENTOUT-PadT5)") (class "Default")
      (node (ref "U2") (pin "T5") (pinfunction "PB1/TIM1_CH3N/TIM3_CH4/TIM8_CH3N/DFSDM1_DATIN1/LCD_R6/OTG_HS_ULPI_D2/ETH_MII_RXD3/LCD_G0/EVENTOUT_T5") (pintype "bidirectional+no_connect"))
    )
    (net (code "266") (name "unconnected-(U2A-PB2{slash}RTC_OUT{slash}SAI1_D1{slash}DFSDM1_CKIN1{slash}SAI1_SD_A{slash}SPI3_MOSI{slash}I2S3_SDO{slash}SAI4_SD_A{slash}QUADSPI_CLK{slash}SAI4_D1{slash}EVENTOUT-PadR6)") (class "Default")
      (node (ref "U2") (pin "R6") (pinfunction "PB2/RTC_OUT/SAI1_D1/DFSDM1_CKIN1/SAI1_SD_A/SPI3_MOSI/I2S3_SDO/SAI4_SD_A/QUADSPI_CLK/SAI4_D1/EVENTOUT_R6") (pintype "bidirectional+no_connect"))
    )
    (net (code "267") (name "unconnected-(U2A-PB3{slash}JTDO{slash}TRACESWO{slash}TIM2_CH2{slash}HRTIM_FLT4{slash}SPI1_SCK{slash}I2S1_CK{slash}SPI3_SCK{slash}I2S3_CK{slash}SPI6_SCK{slash}SDMMC2_D2{slash}CRS_SYNC{slash}UART7_RX{slash}EVENTOUT-PadC6)") (class "Default")
      (node (ref "U2") (pin "C6") (pinfunction "PB3/JTDO/TRACESWO/TIM2_CH2/HRTIM_FLT4/SPI1_SCK/I2S1_CK/SPI3_SCK/I2S3_CK/SPI6_SCK/SDMMC2_D2/CRS_SYNC/UART7_RX/EVENTOUT_C6") (pintype "bidirectional+no_connect"))
    )
    (net (code "268") (name "unconnected-(U2A-PB4{slash}NJTRST{slash}TIM16_BKIN{slash}TIM3_CH1{slash}HRTIM_EEV6{slash}SPI1_MISO{slash}I2S1_SDI{slash}SPI3_MISO{slash}I2S3_SDI{slash}SPI2_NSS{slash}I2S2_WS{slash}SPI6_MISO{slash}SDMMC2_D3{slash}UART7_TX{slash}EVENTOUT-PadB7)") (class "Default")
      (node (ref "U2") (pin "B7") (pinfunction "PB4/NJTRST/TIM16_BKIN/TIM3_CH1/HRTIM_EEV6/SPI1_MISO/I2S1_SDI/SPI3_MISO/I2S3_SDI/SPI2_NSS/I2S2_WS/SPI6_MISO/SDMMC2_D3/UART7_TX/EVENTOUT_B7") (pintype "bidirectional+no_connect"))
    )
    (net (code "269") (name "unconnected-(U2A-PB5{slash}TIM17_BKIN{slash}TIM3_CH2{slash}HRTIM_EEV7{slash}I2C1_SMBA{slash}SPI1_MOSI{slash}I2S1_SDO{slash}I2C4_SMBA{slash}SPI3_MOSI{slash}I2S3_SDO{slash}SPI6_MOSI{slash}FDCAN2_RX{slash}OTG_HS_ULPI_D7{slash}ETH_PPS_OUT{slash}FMC_SDCKE1{slash}DCMI_D10{slash}UART5_RX{slash}EVENTOUT-PadA5)") (class "Default")
      (node (ref "U2") (pin "A5") (pinfunction "PB5/TIM17_BKIN/TIM3_CH2/HRTIM_EEV7/I2C1_SMBA/SPI1_MOSI/I2S1_SDO/I2C4_SMBA/SPI3_MOSI/I2S3_SDO/SPI6_MOSI/FDCAN2_RX/OTG_HS_ULPI_D7/ETH_PPS_OUT/FMC_SDCKE1/DCMI_D10/UART5_RX/EVENTOUT_A5") (pintype "bidirectional+no_connect"))
    )
    (net (code "270") (name "unconnected-(U2A-PB6{slash}TIM16_CH1N{slash}TIM4_CH1{slash}HRTIM_EEV8{slash}I2C1_SCL{slash}CEC{slash}I2C4_SCL{slash}USART1_TX{slash}LPUART1_TX{slash}FDCAN2_TX{slash}QUADSPI_BK1_NCS{slash}DFSDM1_DATIN5{slash}FMC_SDNE1{slash}DCMI_D5{slash}UART5_TX{slash}EVENTOUT-PadB5)") (class "Default")
      (node (ref "U2") (pin "B5") (pinfunction "PB6/TIM16_CH1N/TIM4_CH1/HRTIM_EEV8/I2C1_SCL/CEC/I2C4_SCL/USART1_TX/LPUART1_TX/FDCAN2_TX/QUADSPI_BK1_NCS/DFSDM1_DATIN5/FMC_SDNE1/DCMI_D5/UART5_TX/EVENTOUT_B5") (pintype "bidirectional+no_connect"))
    )
    (net (code "271") (name "unconnected-(U2A-PB7{slash}TIM17_CH1N{slash}TIM4_CH2{slash}HRTIM_EEV9{slash}I2C1_SDA{slash}I2C4_SDA{slash}USART1_RX{slash}LPUART1_RX{slash}FDCAN2_TXFD_MODE{slash}DFSDM1_CKIN5{slash}FMC_NL{slash}DCMI_VSYNC{slash}EVENTOUT-PadC5)") (class "Default")
      (node (ref "U2") (pin "C5") (pinfunction "PB7/TIM17_CH1N/TIM4_CH2/HRTIM_EEV9/I2C1_SDA/I2C4_SDA/USART1_RX/LPUART1_RX/FDCAN2_TXFD_MODE/DFSDM1_CKIN5/FMC_NL/DCMI_VSYNC/EVENTOUT_C5") (pintype "bidirectional+no_connect"))
    )
    (net (code "272") (name "unconnected-(U2A-PB8{slash}TIM16_CH1{slash}TIM4_CH3{slash}DFSDM1_CKIN7{slash}I2C1_SCL{slash}I2C4_SCL{slash}SDMMC1_CKIN{slash}UART4_RX{slash}FDCAN1_RX{slash}SDMMC2_D4{slash}ETH_MII_TXD3{slash}SDMMC1_D4{slash}DCMI_D6{slash}LCD_B6{slash}EVENTOUT-PadD5)") (class "Default")
      (node (ref "U2") (pin "D5") (pinfunction "PB8/TIM16_CH1/TIM4_CH3/DFSDM1_CKIN7/I2C1_SCL/I2C4_SCL/SDMMC1_CKIN/UART4_RX/FDCAN1_RX/SDMMC2_D4/ETH_MII_TXD3/SDMMC1_D4/DCMI_D6/LCD_B6/EVENTOUT_D5") (pintype "bidirectional+no_connect"))
    )
    (net (code "273") (name "unconnected-(U2A-PB9{slash}TIM17_CH1{slash}TIM4_CH4{slash}DFSDM1_DATIN7{slash}I2C1_SDA{slash}SPI2_NSS{slash}I2S2_WS{slash}I2C4_SDA{slash}SDMMC1_CDIR{slash}UART4_TX{slash}FDCAN1_TX{slash}SDMMC2_D5{slash}I2C4_SMBA{slash}SDMMC1_D5{slash}DCMI_D7{slash}LCD_B7{slash}EVENTOUT-PadD4)") (class "Default")
      (node (ref "U2") (pin "D4") (pinfunction "PB9/TIM17_CH1/TIM4_CH4/DFSDM1_DATIN7/I2C1_SDA/SPI2_NSS/I2S2_WS/I2C4_SDA/SDMMC1_CDIR/UART4_TX/FDCAN1_TX/SDMMC2_D5/I2C4_SMBA/SDMMC1_D5/DCMI_D7/LCD_B7/EVENTOUT_D4") (pintype "bidirectional+no_connect"))
    )
    (net (code "274") (name "unconnected-(U2A-PB10{slash}TIM2_CH3{slash}HRTIM_SCOUT{slash}LPTIM2_IN1{slash}I2C2_SCL{slash}SPI2_SCK{slash}I2S2_CK{slash}DFSDM1_DATIN7{slash}USART3_TX{slash}QUADSPI_BK1_NCS{slash}OTG_HS_ULPI_D3{slash}ETH_MII_RX_ER{slash}LCD_G4{slash}EVENTOUT-PadP11)") (class "Default")
      (node (ref "U2") (pin "P11") (pinfunction "PB10/TIM2_CH3/HRTIM_SCOUT/LPTIM2_IN1/I2C2_SCL/SPI2_SCK/I2S2_CK/DFSDM1_DATIN7/USART3_TX/QUADSPI_BK1_NCS/OTG_HS_ULPI_D3/ETH_MII_RX_ER/LCD_G4/EVENTOUT_P11") (pintype "bidirectional+no_connect"))
    )
    (net (code "275") (name "unconnected-(U2A-PB11{slash}TIM2_CH4{slash}HRTIM_SCIN{slash}LPTIM2_ETR{slash}I2C2_SDA{slash}DFSDM1_CKIN7{slash}USART3_RX{slash}OTG_HS_ULPI_D4{slash}ETH_MII_TX_EN{slash}ETH_RMII_TX_EN{slash}LCD_G5{slash}EVENTOUT-PadP12)") (class "Default")
      (node (ref "U2") (pin "P12") (pinfunction "PB11/TIM2_CH4/HRTIM_SCIN/LPTIM2_ETR/I2C2_SDA/DFSDM1_CKIN7/USART3_RX/OTG_HS_ULPI_D4/ETH_MII_TX_EN/ETH_RMII_TX_EN/LCD_G5/EVENTOUT_P12") (pintype "bidirectional+no_connect"))
    )
    (net (code "276") (name "unconnected-(U2A-PB12{slash}TIM1_BKIN{slash}I2C2_SMBA{slash}SPI2_NSS{slash}I2S2_WS{slash}DFSDM1_DATIN1{slash}USART3_CK{slash}FDCAN2_RX{slash}OTG_HS_ULPI_D5{slash}ETH_MII_TXD0{slash}ETH_RMII_TXD0{slash}OTG_HS_ID{slash}TIM1_BKIN_COMP12{slash}UART5_RX{slash}EVENTOUT-PadT14)") (class "Default")
      (node (ref "U2") (pin "T14") (pinfunction "PB12/TIM1_BKIN/I2C2_SMBA/SPI2_NSS/I2S2_WS/DFSDM1_DATIN1/USART3_CK/FDCAN2_RX/OTG_HS_ULPI_D5/ETH_MII_TXD0/ETH_RMII_TXD0/OTG_HS_ID/TIM1_BKIN_COMP12/UART5_RX/EVENTOUT_T14") (pintype "bidirectional+no_connect"))
    )
    (net (code "277") (name "unconnected-(U2A-PB14{slash}TIM1_CH2N{slash}TIM12_CH1{slash}TIM8_CH2N{slash}USART1_TX{slash}SPI2_MISO{slash}I2S2_SDI{slash}DFSDM1_DATIN2{slash}USART3_RTS{slash}USART3_DE{slash}UART4_RTS{slash}UART4_DE{slash}SDMMC2_D0{slash}OTG_HS_DM{slash}EVENTOUT-PadU15)") (class "Default")
      (node (ref "U2") (pin "U15") (pinfunction "PB14/TIM1_CH2N/TIM12_CH1/TIM8_CH2N/USART1_TX/SPI2_MISO/I2S2_SDI/DFSDM1_DATIN2/USART3_RTS/USART3_DE/UART4_RTS/UART4_DE/SDMMC2_D0/OTG_HS_DM/EVENTOUT_U15") (pintype "bidirectional+no_connect"))
    )
    (net (code "278") (name "unconnected-(U2A-PB15{slash}RTC_REFIN{slash}TIM1_CH3N{slash}TIM12_CH2{slash}TIM8_CH3N{slash}USART1_RX{slash}SPI2_MOSI{slash}I2S2_SDO{slash}DFSDM1_CKIN2{slash}UART4_CTS{slash}SDMMC2_D1{slash}OTG_HS_DP{slash}EVENTOUT-PadT15)") (class "Default")
      (node (ref "U2") (pin "T15") (pinfunction "PB15/RTC_REFIN/TIM1_CH3N/TIM12_CH2/TIM8_CH3N/USART1_RX/SPI2_MOSI/I2S2_SDO/DFSDM1_CKIN2/UART4_CTS/SDMMC2_D1/OTG_HS_DP/EVENTOUT_T15") (pintype "bidirectional+no_connect"))
    )
    (net (code "279") (name "unconnected-(U2B-PC1{slash}TRACED0{slash}SAI1_D1{slash}DFSDM1_DATIN0{slash}DFSDM1_CKIN4{slash}SPI2_MOSI{slash}I2S2_SDO{slash}SAI1_SD_A{slash}SAI4_SD_A{slash}SDMMC2_CK{slash}SAI4_D1{slash}ETH_MDC{slash}MDIOS_MDC{slash}EVENTOUT-PadM2)") (class "Default")
      (node (ref "U2") (pin "M2") (pinfunction "PC1/TRACED0/SAI1_D1/DFSDM1_DATIN0/DFSDM1_CKIN4/SPI2_MOSI/I2S2_SDO/SAI1_SD_A/SAI4_SD_A/SDMMC2_CK/SAI4_D1/ETH_MDC/MDIOS_MDC/EVENTOUT_M2") (pintype "bidirectional+no_connect"))
    )
    (net (code "280") (name "unconnected-(U2B-PC2_C{slash}CDSLEEP{slash}DFSDM1_CKIN1{slash}SPI2_MISO{slash}I2S2_SDI{slash}DFSDM1_CKOUT{slash}OTG_HS_ULPI_DIR{slash}ETH_MII_TXD2{slash}FMC_SDNE0{slash}EVENTOUT-PadR1)") (class "Default")
      (node (ref "U2") (pin "R1") (pinfunction "PC2_C/CDSLEEP/DFSDM1_CKIN1/SPI2_MISO/I2S2_SDI/DFSDM1_CKOUT/OTG_HS_ULPI_DIR/ETH_MII_TXD2/FMC_SDNE0/EVENTOUT_R1") (pintype "bidirectional+no_connect"))
    )
    (net (code "281") (name "unconnected-(U2B-PC2{slash}CDSLEEP{slash}DFSDM1_CKIN1{slash}SPI2_MISO{slash}I2S2_SDI{slash}DFSDM1_CKOUT{slash}OTG_HS_ULPI_DIR{slash}ETH_MII_TXD2{slash}FMC_SDNE0{slash}EVENTOUT-PadM3)") (class "Default")
      (node (ref "U2") (pin "M3") (pinfunction "PC2/CDSLEEP/DFSDM1_CKIN1/SPI2_MISO/I2S2_SDI/DFSDM1_CKOUT/OTG_HS_ULPI_DIR/ETH_MII_TXD2/FMC_SDNE0/EVENTOUT_M3") (pintype "bidirectional+no_connect"))
    )
    (net (code "282") (name "unconnected-(U2B-PC3_C{slash}CSLEEP{slash}DFSDM1_DATIN1{slash}SPI2_MOSI{slash}I2S2_SDO{slash}OTG_HS_ULPI_NXT{slash}ETH_MII_TX_CLK{slash}FMC_SDCKE0{slash}EVENTOUT-PadR2)") (class "Default")
      (node (ref "U2") (pin "R2") (pinfunction "PC3_C/CSLEEP/DFSDM1_DATIN1/SPI2_MOSI/I2S2_SDO/OTG_HS_ULPI_NXT/ETH_MII_TX_CLK/FMC_SDCKE0/EVENTOUT_R2") (pintype "bidirectional+no_connect"))
    )
    (net (code "283") (name "unconnected-(U2B-PC3{slash}CSLEEP{slash}DFSDM1_DATIN1{slash}SPI2_MOSI{slash}I2S2_SDO{slash}OTG_HS_ULPI_NXT{slash}ETH_MII_TX_CLK{slash}FMC_SDCKE0{slash}EVENTOUT-PadM4)") (class "Default")
      (node (ref "U2") (pin "M4") (pinfunction "PC3/CSLEEP/DFSDM1_DATIN1/SPI2_MOSI/I2S2_SDO/OTG_HS_ULPI_NXT/ETH_MII_TX_CLK/FMC_SDCKE0/EVENTOUT_M4") (pintype "bidirectional+no_connect"))
    )
    (net (code "284") (name "unconnected-(U2B-PC4{slash}DFSDM1_CKIN2{slash}I2S1_MCK{slash}SPDIFRX1_IN3{slash}ETH_MII_RXD0{slash}ETH_RMII_RXD0{slash}FMC_SDNE0{slash}EVENTOUT-PadT4)") (class "Default")
      (node (ref "U2") (pin "T4") (pinfunction "PC4/DFSDM1_CKIN2/I2S1_MCK/SPDIFRX1_IN3/ETH_MII_RXD0/ETH_RMII_RXD0/FMC_SDNE0/EVENTOUT_T4") (pintype "bidirectional+no_connect"))
    )
    (net (code "285") (name "unconnected-(U2B-PC5{slash}SAI1_D3{slash}DFSDM1_DATIN2{slash}SPDIFRX1_IN4{slash}SAI4_D3{slash}ETH_MII_RXD1{slash}ETH_RMII_RXD1{slash}FMC_SDCKE0{slash}COMP1_OUT{slash}EVENTOUT-PadU4)") (class "Default")
      (node (ref "U2") (pin "U4") (pinfunction "PC5/SAI1_D3/DFSDM1_DATIN2/SPDIFRX1_IN4/SAI4_D3/ETH_MII_RXD1/ETH_RMII_RXD1/FMC_SDCKE0/COMP1_OUT/EVENTOUT_U4") (pintype "bidirectional+no_connect"))
    )
    (net (code "286") (name "unconnected-(U2B-PD4{slash}HRTIM_FLT3{slash}SAI3_FS_A{slash}USART2_RTS{slash}USART2_DE{slash}FDCAN1_RXFD_MODE{slash}FMC_NOE{slash}EVENTOUT-PadA12)") (class "Default")
      (node (ref "U2") (pin "A12") (pinfunction "PD4/HRTIM_FLT3/SAI3_FS_A/USART2_RTS/USART2_DE/FDCAN1_RXFD_MODE/FMC_NOE/EVENTOUT_A12") (pintype "bidirectional+no_connect"))
    )
    (net (code "287") (name "unconnected-(U2B-PD5{slash}HRTIM_EEV3{slash}USART2_TX{slash}FDCAN1_TXFD_MODE{slash}FMC_NWE{slash}EVENTOUT-PadA11)") (class "Default")
      (node (ref "U2") (pin "A11") (pinfunction "PD5/HRTIM_EEV3/USART2_TX/FDCAN1_TXFD_MODE/FMC_NWE/EVENTOUT_A11") (pintype "bidirectional+no_connect"))
    )
    (net (code "288") (name "unconnected-(U2B-PD6{slash}SAI1_D1{slash}DFSDM1_CKIN4{slash}DFSDM1_DATIN1{slash}SPI3_MOSI{slash}I2S3_SDO{slash}SAI1_SD_A{slash}USART2_RX{slash}SAI4_SD_A{slash}FDCAN2_RXFD_MODE{slash}SAI4_D1{slash}SDMMC2_CK{slash}FMC_NWAIT{slash}DCMI_D10{slash}LCD_B2{slash}EVENTOUT-PadB11)") (class "Default")
      (node (ref "U2") (pin "B11") (pinfunction "PD6/SAI1_D1/DFSDM1_CKIN4/DFSDM1_DATIN1/SPI3_MOSI/I2S3_SDO/SAI1_SD_A/USART2_RX/SAI4_SD_A/FDCAN2_RXFD_MODE/SAI4_D1/SDMMC2_CK/FMC_NWAIT/DCMI_D10/LCD_B2/EVENTOUT_B11") (pintype "bidirectional+no_connect"))
    )
    (net (code "289") (name "unconnected-(U2B-PD7{slash}DFSDM1_DATIN4{slash}SPI1_MOSI{slash}I2S1_SDO{slash}DFSDM1_CKIN1{slash}USART2_CK{slash}SPDIFRX1_IN1{slash}SDMMC2_CMD{slash}FMC_NE1{slash}EVENTOUT-PadC11)") (class "Default")
      (node (ref "U2") (pin "C11") (pinfunction "PD7/DFSDM1_DATIN4/SPI1_MOSI/I2S1_SDO/DFSDM1_CKIN1/USART2_CK/SPDIFRX1_IN1/SDMMC2_CMD/FMC_NE1/EVENTOUT_C11") (pintype "bidirectional+no_connect"))
    )
    (net (code "290") (name "unconnected-(U2B-PD11{slash}LPTIM2_IN2{slash}I2C4_SMBA{slash}USART3_CTS{slash}USART3_NSS{slash}QUADSPI_BK1_IO0{slash}SAI2_SD_A{slash}FMC_A16{slash}EVENTOUT-PadR15)") (class "Default")
      (node (ref "U2") (pin "R15") (pinfunction "PD11/LPTIM2_IN2/I2C4_SMBA/USART3_CTS/USART3_NSS/QUADSPI_BK1_IO0/SAI2_SD_A/FMC_A16/EVENTOUT_R15") (pintype "bidirectional+no_connect"))
    )
    (net (code "291") (name "unconnected-(U2B-PD12{slash}LPTIM1_IN1{slash}TIM4_CH1{slash}LPTIM2_IN1{slash}I2C4_SCL{slash}USART3_RTS{slash}USART3_DE{slash}QUADSPI_BK1_IO1{slash}SAI2_FS_A{slash}FMC_A17{slash}EVENTOUT-PadR16)") (class "Default")
      (node (ref "U2") (pin "R16") (pinfunction "PD12/LPTIM1_IN1/TIM4_CH1/LPTIM2_IN1/I2C4_SCL/USART3_RTS/USART3_DE/QUADSPI_BK1_IO1/SAI2_FS_A/FMC_A17/EVENTOUT_R16") (pintype "bidirectional+no_connect"))
    )
    (net (code "292") (name "unconnected-(U2B-PD13{slash}LPTIM1_OUT{slash}TIM4_CH2{slash}I2C4_SDA{slash}QUADSPI_BK1_IO3{slash}SAI2_SCK_A{slash}FMC_A18{slash}EVENTOUT-PadR17)") (class "Default")
      (node (ref "U2") (pin "R17") (pinfunction "PD13/LPTIM1_OUT/TIM4_CH2/I2C4_SDA/QUADSPI_BK1_IO3/SAI2_SCK_A/FMC_A18/EVENTOUT_R17") (pintype "bidirectional+no_connect"))
    )
    (net (code "293") (name "unconnected-(U2C-PE2{slash}TRACECLK{slash}SAI1_CK1{slash}SPI4_SCK{slash}SAI1_MCLK_A{slash}SAI4_MCLK_A{slash}QUADSPI_BK1_IO2{slash}SAI4_CK1{slash}ETH_MII_TXD3{slash}FMC_A23{slash}EVENTOUT-PadC3)") (class "Default")
      (node (ref "U2") (pin "C3") (pinfunction "PE2/TRACECLK/SAI1_CK1/SPI4_SCK/SAI1_MCLK_A/SAI4_MCLK_A/QUADSPI_BK1_IO2/SAI4_CK1/ETH_MII_TXD3/FMC_A23/EVENTOUT_C3") (pintype "bidirectional+no_connect"))
    )
    (net (code "294") (name "unconnected-(U2C-PE3{slash}TRACED0{slash}TIM15_BKIN{slash}SAI1_SD_B{slash}SAI4_SD_B{slash}FMC_A19{slash}EVENTOUT-PadD3)") (class "Default")
      (node (ref "U2") (pin "D3") (pinfunction "PE3/TRACED0/TIM15_BKIN/SAI1_SD_B/SAI4_SD_B/FMC_A19/EVENTOUT_D3") (pintype "bidirectional+no_connect"))
    )
    (net (code "295") (name "unconnected-(U2D-PG12{slash}LPTIM1_IN1{slash}HRTIM_EEV5{slash}SPI6_MISO{slash}USART6_RTS{slash}USART6_DE{slash}SPDIFRX1_IN2{slash}LCD_B4{slash}ETH_MII_TXD1{slash}ETH_RMII_TXD1{slash}FMC_NE4{slash}LCD_B1{slash}EVENTOUT-PadC9)") (class "Default")
      (node (ref "U2") (pin "C9") (pinfunction "PG12/LPTIM1_IN1/HRTIM_EEV5/SPI6_MISO/USART6_RTS/USART6_DE/SPDIFRX1_IN2/LCD_B4/ETH_MII_TXD1/ETH_RMII_TXD1/FMC_NE4/LCD_B1/EVENTOUT_C9") (pintype "bidirectional+no_connect"))
    )
    (net (code "296") (name "unconnected-(U2D-PG13{slash}TRACED0{slash}LPTIM1_OUT{slash}HRTIM_EEV10{slash}SPI6_SCK{slash}USART6_CTS{slash}USART6_NSS{slash}ETH_MII_TXD0{slash}ETH_RMII_TXD0{slash}FMC_A24{slash}LCD_R0{slash}EVENTOUT-PadD9)") (class "Default")
      (node (ref "U2") (pin "D9") (pinfunction "PG13/TRACED0/LPTIM1_OUT/HRTIM_EEV10/SPI6_SCK/USART6_CTS/USART6_NSS/ETH_MII_TXD0/ETH_RMII_TXD0/FMC_A24/LCD_R0/EVENTOUT_D9") (pintype "bidirectional+no_connect"))
    )
    (net (code "297") (name "unconnected-(U2D-PG14{slash}TRACED1{slash}LPTIM1_ETR{slash}SPI6_MOSI{slash}USART6_TX{slash}QUADSPI_BK2_IO3{slash}ETH_MII_TXD1{slash}ETH_RMII_TXD1{slash}FMC_A25{slash}LCD_B0{slash}EVENTOUT-PadD8)") (class "Default")
      (node (ref "U2") (pin "D8") (pinfunction "PG14/TRACED1/LPTIM1_ETR/SPI6_MOSI/USART6_TX/QUADSPI_BK2_IO3/ETH_MII_TXD1/ETH_RMII_TXD1/FMC_A25/LCD_B0/EVENTOUT_D8") (pintype "bidirectional+no_connect"))
    )
    (net (code "298") (name "unconnected-(U2D-PH7{slash}I2C3_SCL{slash}SPI5_MISO{slash}ETH_MII_RXD3{slash}FMC_SDCKE1{slash}DCMI_D9{slash}EVENTOUT-PadU13)") (class "Default")
      (node (ref "U2") (pin "U13") (pinfunction "PH7/I2C3_SCL/SPI5_MISO/ETH_MII_RXD3/FMC_SDCKE1/DCMI_D9/EVENTOUT_U13") (pintype "bidirectional+no_connect"))
    )
    (net (code "299") (name "unconnected-(U2F-NC-PadE1)") (class "Default")
      (node (ref "U2") (pin "E1") (pinfunction "NC_E1") (pintype "passive+no_connect"))
    )
    (net (code "300") (name "unconnected-(U2F-NC-PadK16)") (class "Default")
      (node (ref "U2") (pin "K16") (pinfunction "NC_K16") (pintype "passive+no_connect"))
    )
    (net (code "301") (name "unconnected-(U2F-NC-PadK17)") (class "Default")
      (node (ref "U2") (pin "K17") (pinfunction "NC_K17") (pintype "passive+no_connect"))
    )
    (net (code "302") (name "unconnected-(U2F-NC-PadL16)") (class "Default")
      (node (ref "U2") (pin "L16") (pinfunction "NC_L16") (pintype "passive+no_connect"))
    )
    (net (code "303") (name "unconnected-(U2F-NC-PadL17)") (class "Default")
      (node (ref "U2") (pin "L17") (pinfunction "NC_L17") (pintype "passive+no_connect"))
    )
    (net (code "304") (name "unconnected-(U2F-NC-PadM16)") (class "Default")
      (node (ref "U2") (pin "M16") (pinfunction "NC_M16") (pintype "passive+no_connect"))
    )
    (net (code "305") (name "unconnected-(U2F-NC-PadM17)") (class "Default")
      (node (ref "U2") (pin "M17") (pinfunction "NC_M17") (pintype "passive+no_connect"))
    )
    (net (code "306") (name "unconnected-(U2F-NC-PadN17)") (class "Default")
      (node (ref "U2") (pin "N17") (pinfunction "NC_N17") (pintype "passive+no_connect"))
    )
    (net (code "307") (name "unconnected-(U2F-NC1-PadF1)") (class "Default")
      (node (ref "U2") (pin "F1") (pinfunction "NC1_F1") (pintype "passive+no_connect"))
    )
    (net (code "308") (name "unconnected-(U2F-NC2-PadG2)") (class "Default")
      (node (ref "U2") (pin "G2") (pinfunction "NC2_G2") (pintype "passive+no_connect"))
    )
    (net (code "309") (name "unconnected-(U3-NU-PadK2)") (class "Default")
      (node (ref "U3") (pin "K2") (pinfunction "NU_K2") (pintype "bidirectional+no_connect"))
    )
    (net (code "310") (name "unconnected-(U4-CC1-PadA5)") (class "Default")
      (node (ref "U4") (pin "A5") (pinfunction "CC1_A5") (pintype "passive+no_connect"))
    )
    (net (code "311") (name "unconnected-(U4-CC2-PadB5)") (class "Default")
      (node (ref "U4") (pin "B5") (pinfunction "CC2_B5") (pintype "passive+no_connect"))
    )
    (net (code "312") (name "unconnected-(U4-SBU1-PadA8)") (class "Default")
      (node (ref "U4") (pin "A8") (pinfunction "SBU1_A8") (pintype "passive+no_connect"))
    )
    (net (code "313") (name "unconnected-(U4-SBU2-PadB8)") (class "Default")
      (node (ref "U4") (pin "B8") (pinfunction "SBU2_B8") (pintype "passive+no_connect"))
    )
    (net (code "314") (name "unconnected-(U5-CC1-PadA5)") (class "Default")
      (node (ref "U5") (pin "A5") (pinfunction "CC1_A5") (pintype "passive+no_connect"))
    )
    (net (code "315") (name "unconnected-(U5-CC2-PadB5)") (class "Default")
      (node (ref "U5") (pin "B5") (pinfunction "CC2_B5") (pintype "passive+no_connect"))
    )
    (net (code "316") (name "unconnected-(U5-SBU1-PadA8)") (class "Default")
      (node (ref "U5") (pin "A8") (pinfunction "SBU1_A8") (pintype "passive+no_connect"))
    )
    (net (code "317") (name "unconnected-(U5-SBU2-PadB8)") (class "Default")
      (node (ref "U5") (pin "B8") (pinfunction "SBU2_B8") (pintype "passive+no_connect"))
    )
    (net (code "318") (name "unconnected-(U9-EN1-Pad9)") (class "Default")
      (node (ref "U9") (pin "9") (pinfunction "EN1_9") (pintype "passive+no_connect"))
    )
    (net (code "319") (name "unconnected-(U9-FB1-Pad14)") (class "Default")
      (node (ref "U9") (pin "14") (pinfunction "FB1_14") (pintype "passive+no_connect"))
    )
    (net (code "320") (name "unconnected-(U9-NC-Pad1)") (class "Default")
      (node (ref "U9") (pin "1") (pinfunction "NC_1") (pintype "passive+no_connect"))
    )
    (net (code "321") (name "unconnected-(U9-NC-Pad4)") (class "Default")
      (node (ref "U9") (pin "4") (pinfunction "NC_4") (pintype "passive+no_connect"))
    )
    (net (code "322") (name "unconnected-(U9-NC-Pad5)") (class "Default")
      (node (ref "U9") (pin "5") (pinfunction "NC_5") (pintype "passive+no_connect"))
    )
    (net (code "323") (name "unconnected-(U9-NC-Pad12)") (class "Default")
      (node (ref "U9") (pin "12") (pinfunction "NC_12") (pintype "passive+no_connect"))
    )
    (net (code "324") (name "unconnected-(U9-NC-Pad13)") (class "Default")
      (node (ref "U9") (pin "13") (pinfunction "NC_13") (pintype "passive+no_connect"))
    )
    (net (code "325") (name "unconnected-(U9-NC-Pad15)") (class "Default")
      (node (ref "U9") (pin "15") (pinfunction "NC_15") (pintype "passive+no_connect"))
    )
    (net (code "326") (name "unconnected-(U9-NC-Pad16)") (class "Default")
      (node (ref "U9") (pin "16") (pinfunction "NC_16") (pintype "passive+no_connect"))
    )
    (net (code "327") (name "unconnected-(U9-NC-Pad17)") (class "Default")
      (node (ref "U9") (pin "17") (pinfunction "NC_17") (pintype "passive+no_connect"))
    )
    (net (code "328") (name "unconnected-(U9-SW1-Pad11)") (class "Default")
      (node (ref "U9") (pin "11") (pinfunction "SW1_11") (pintype "passive+no_connect"))
    )
    (net (code "329") (name "unconnected-(U9-VIN1-Pad10)") (class "Default")
      (node (ref "U9") (pin "10") (pinfunction "VIN1_10") (pintype "passive+no_connect"))
    )
  )
)
